# MatriXDeck.net
KiCad netlist of a schematic drawn in Altium Designer
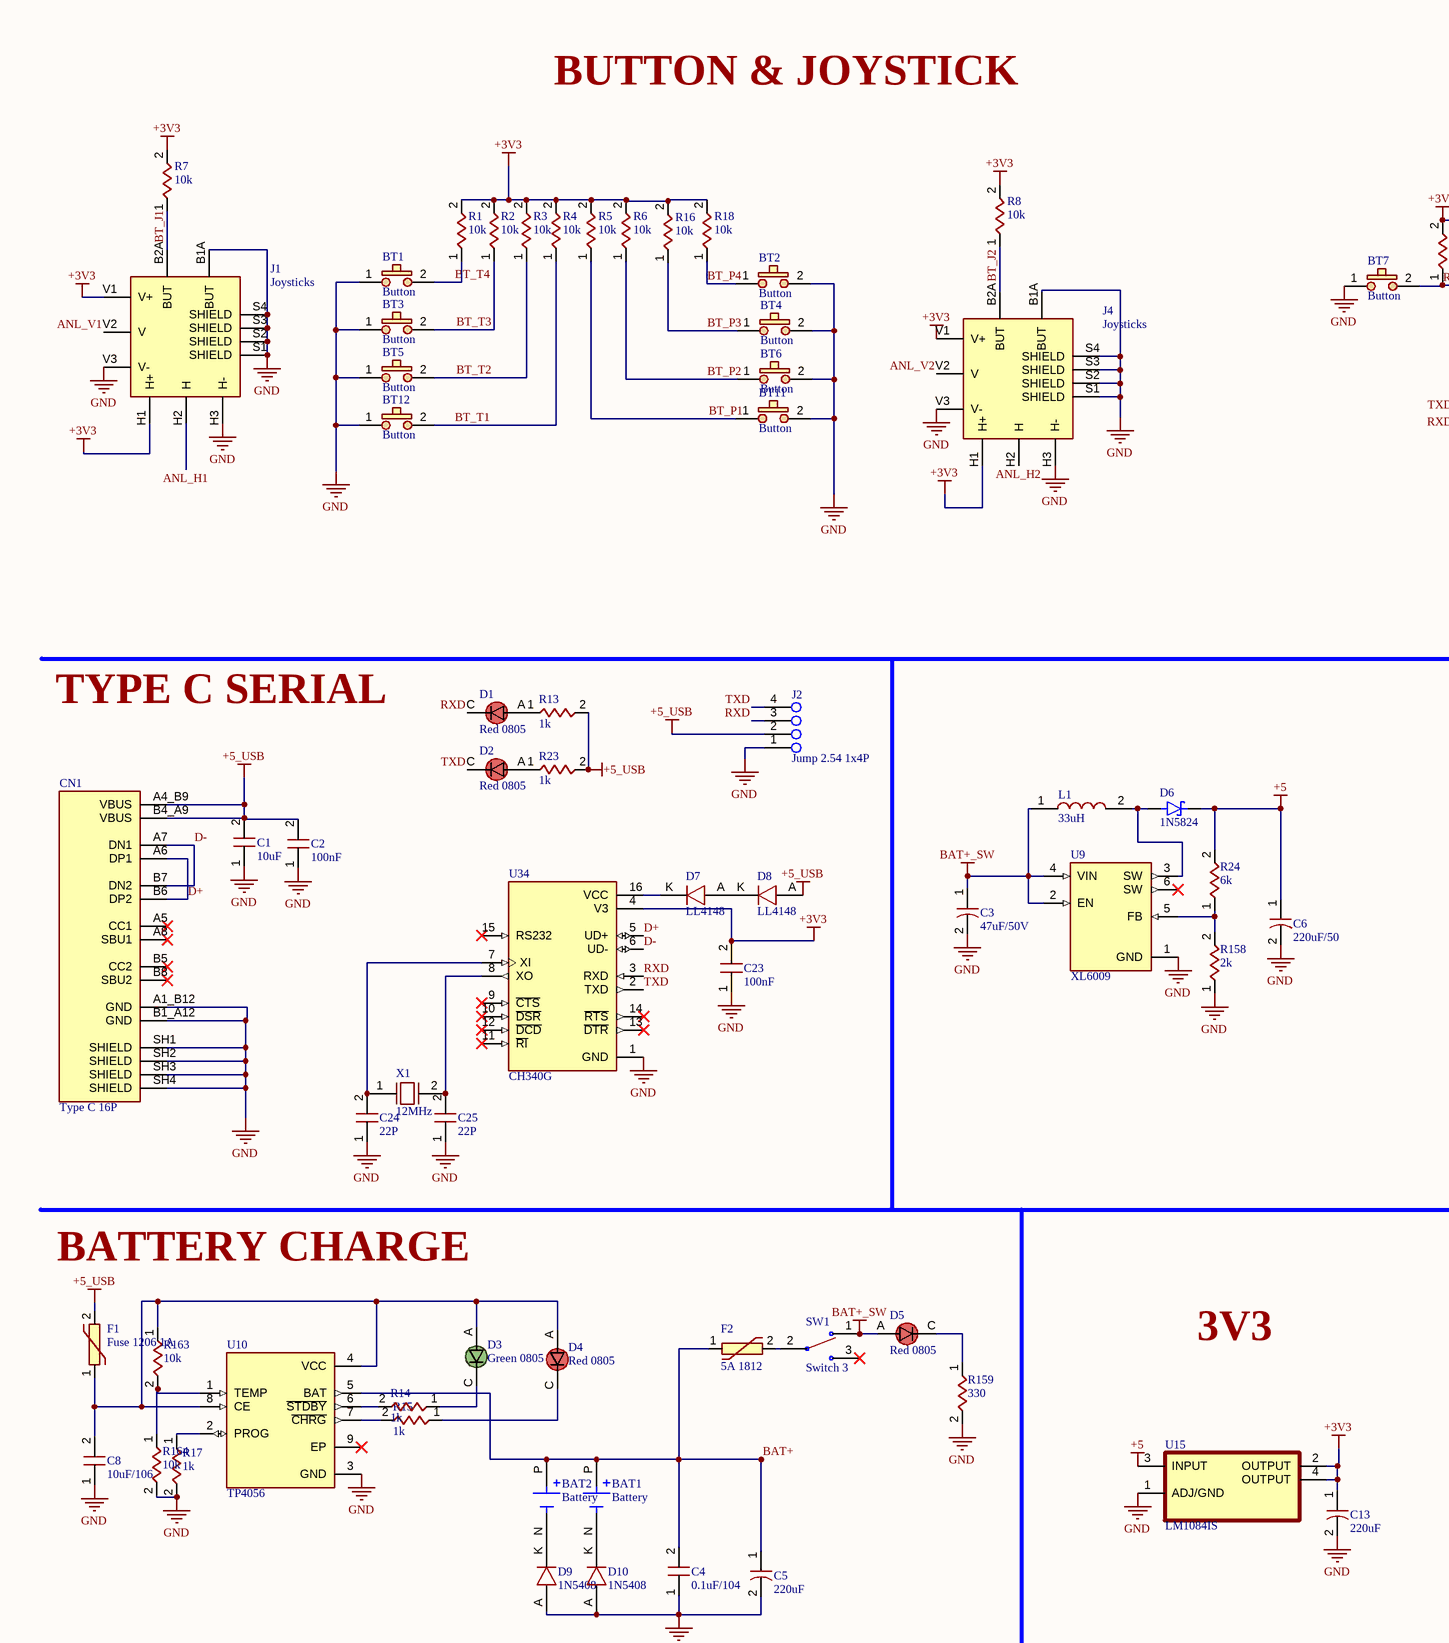
[diagram p0: MatriXDeck.SchDoc, top left]
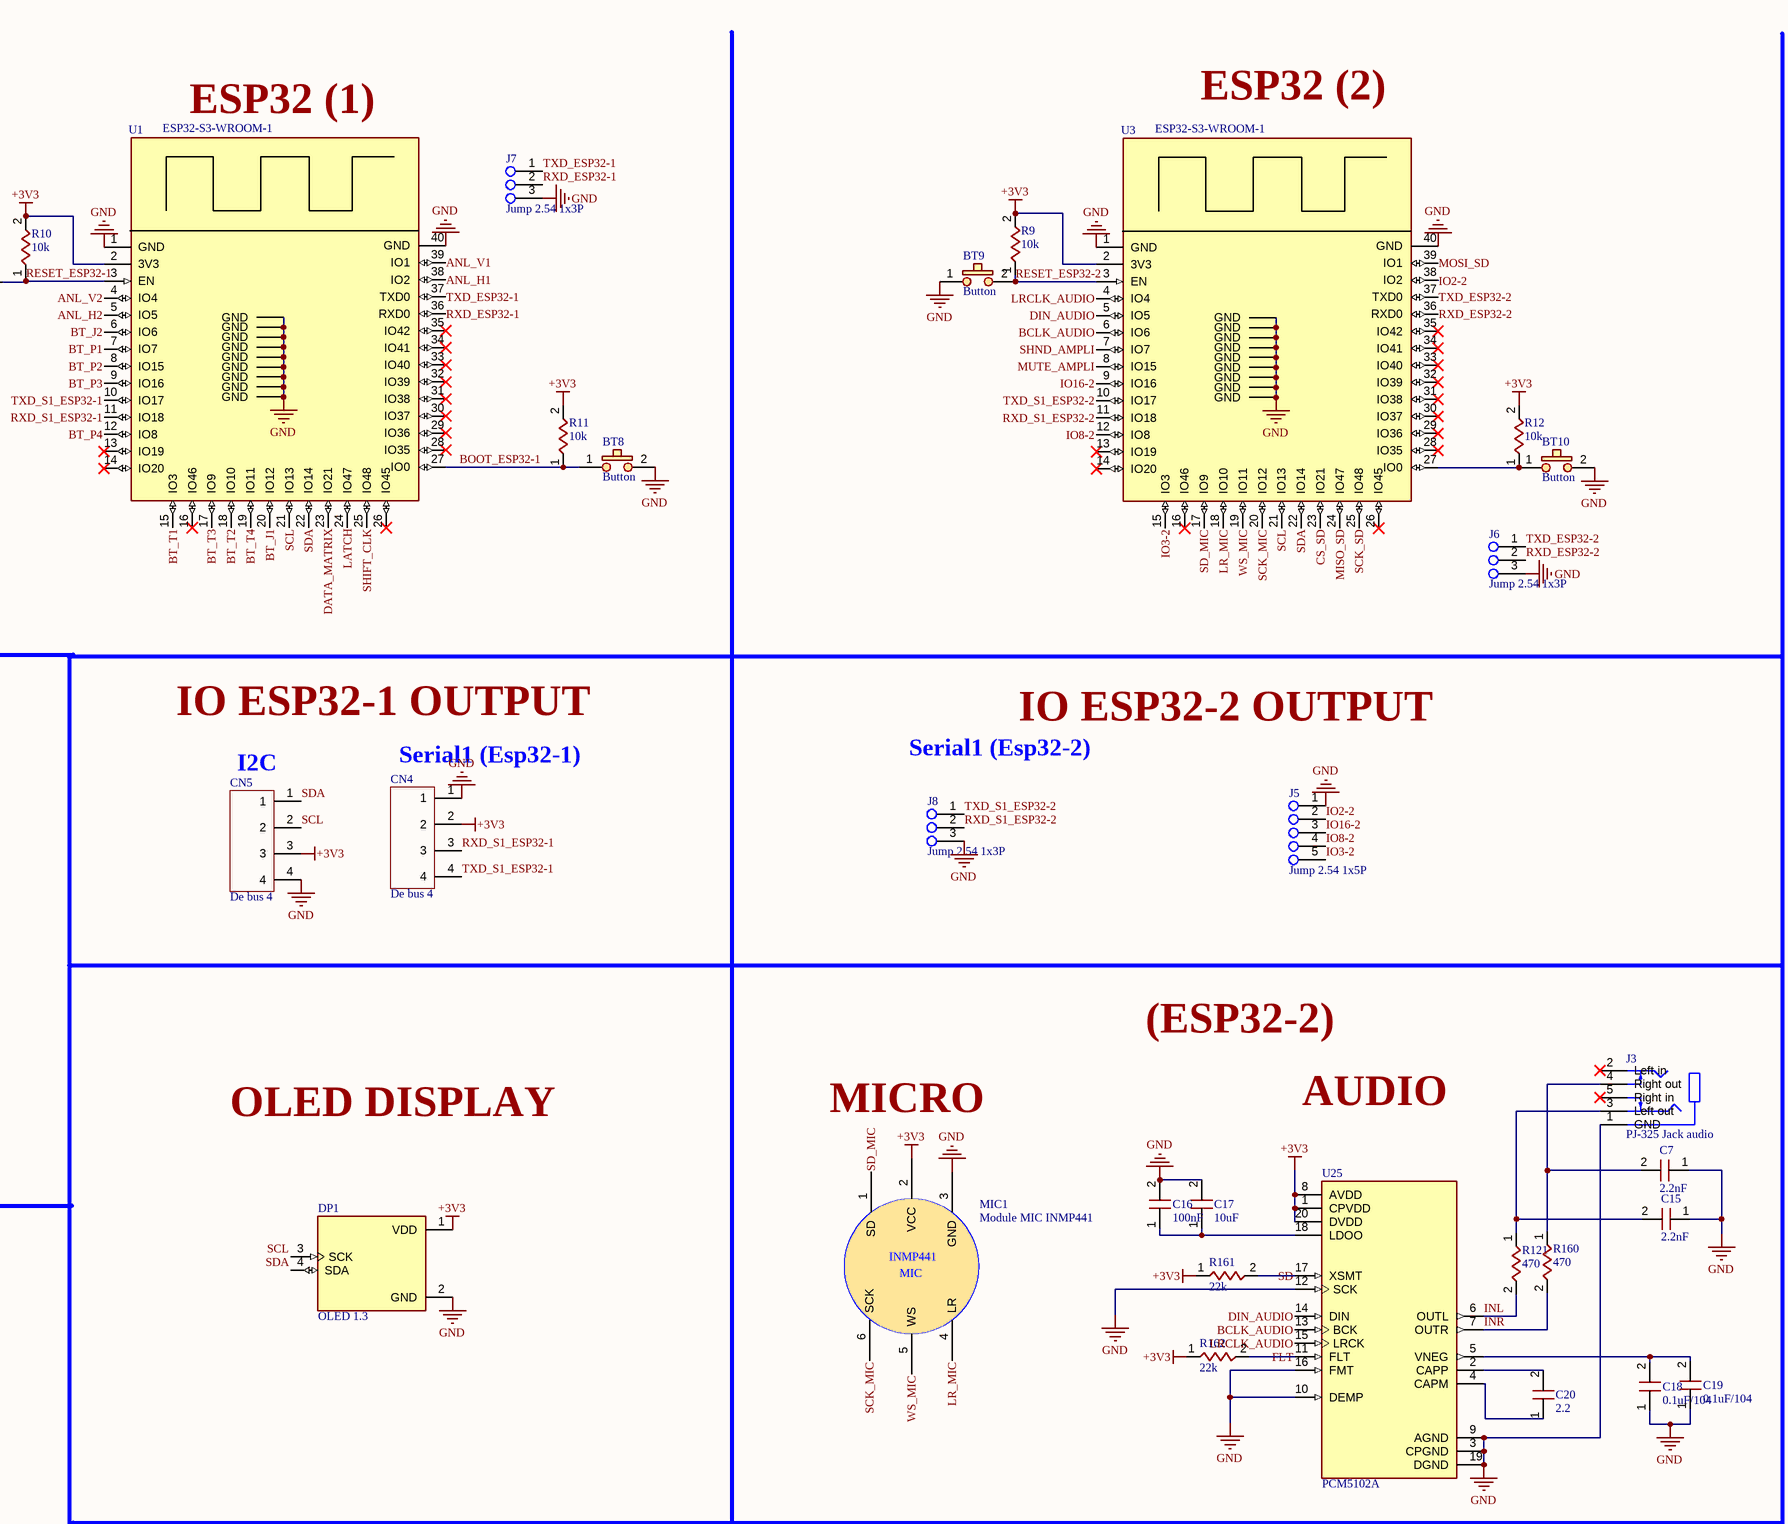
[diagram p1: MatriXDeck.SchDoc, top middle]
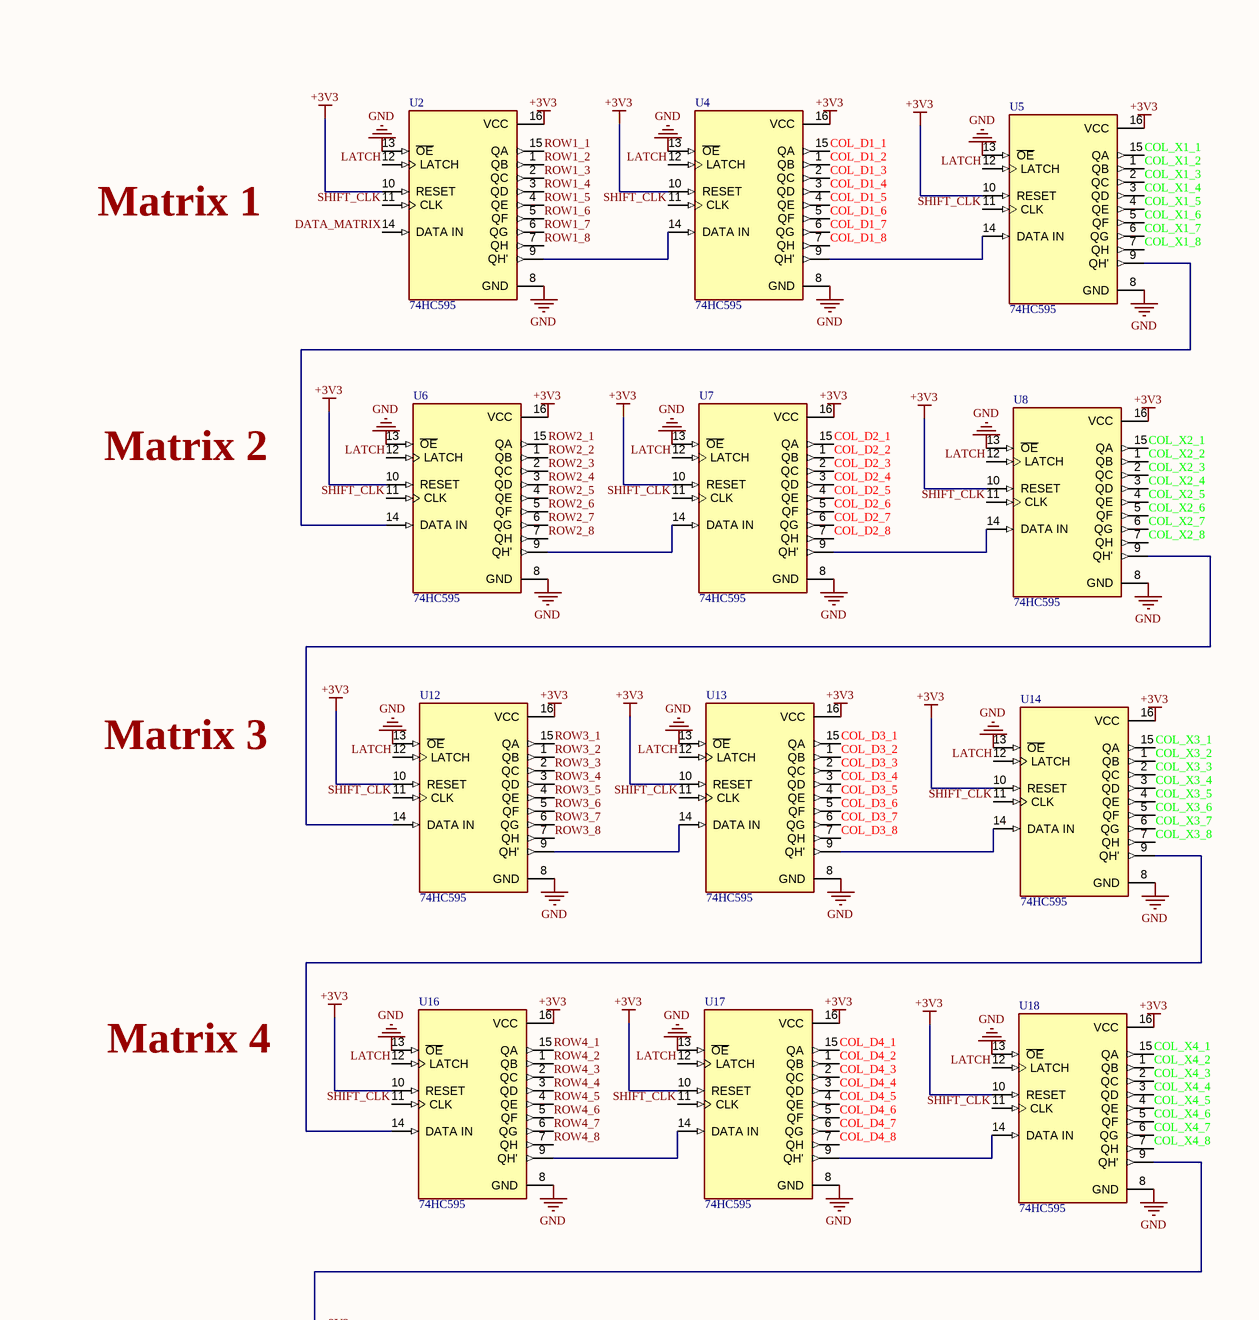
[diagram p2: MatriXDeck.SchDoc, top right]
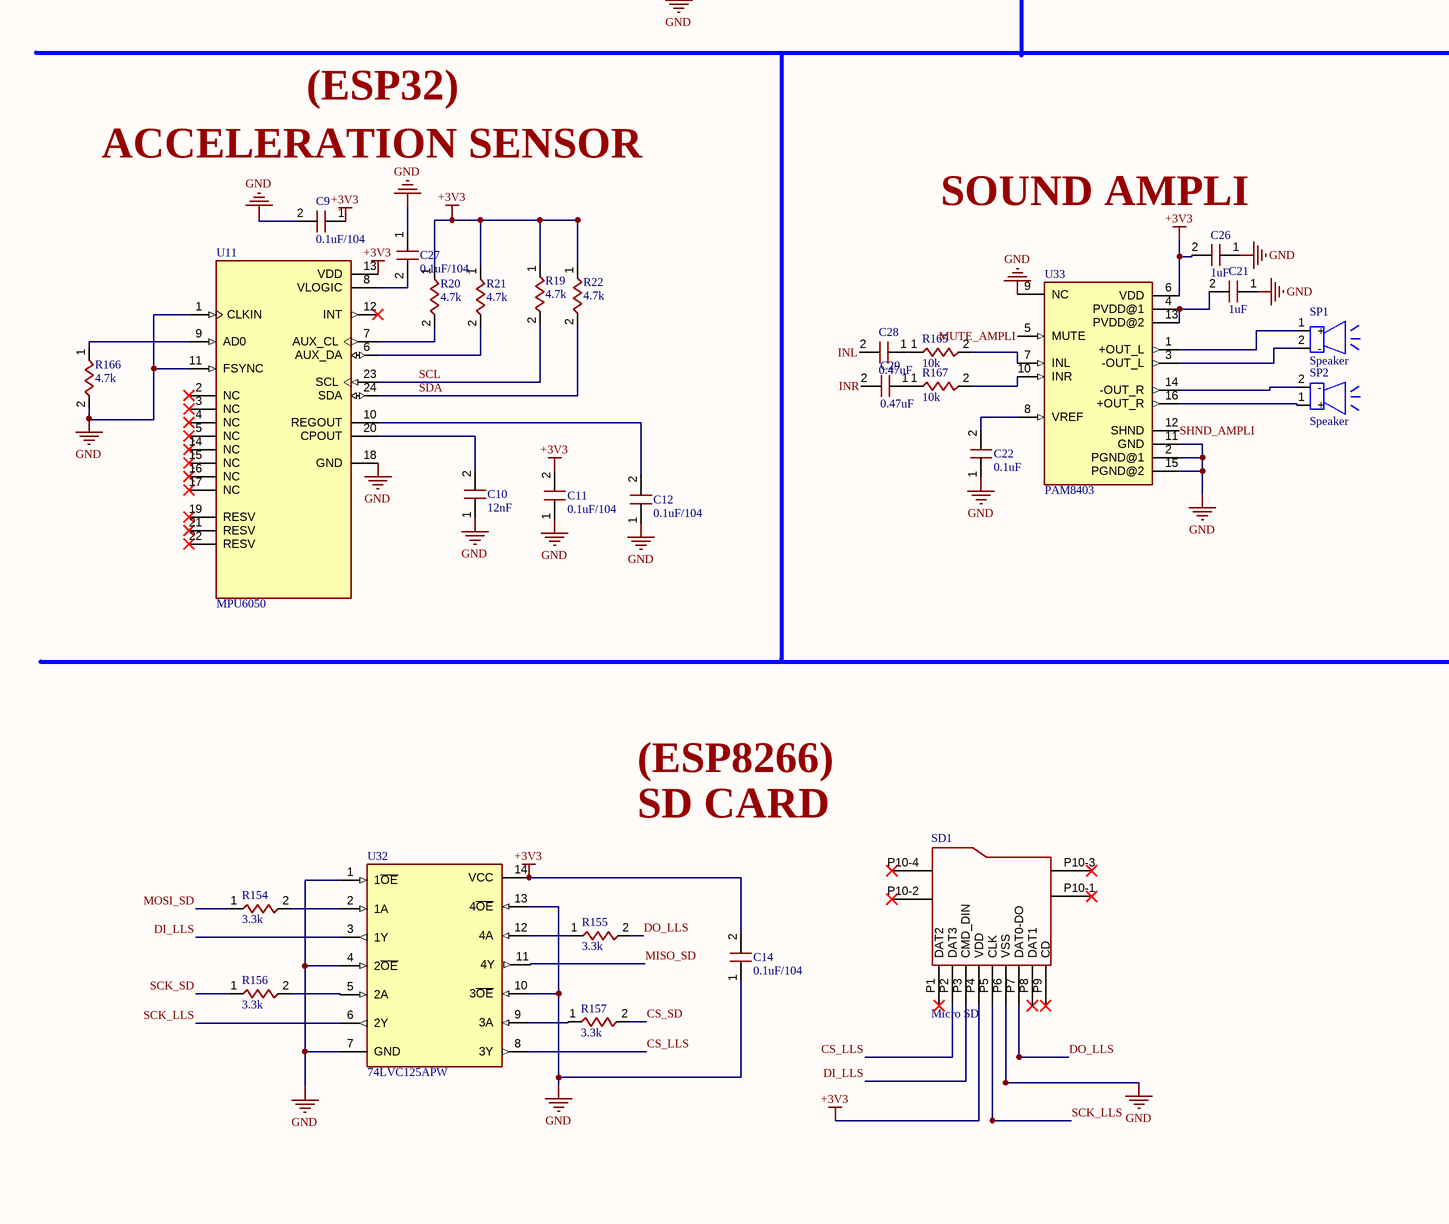
[diagram p3: MatriXDeck.SchDoc, bottom left]
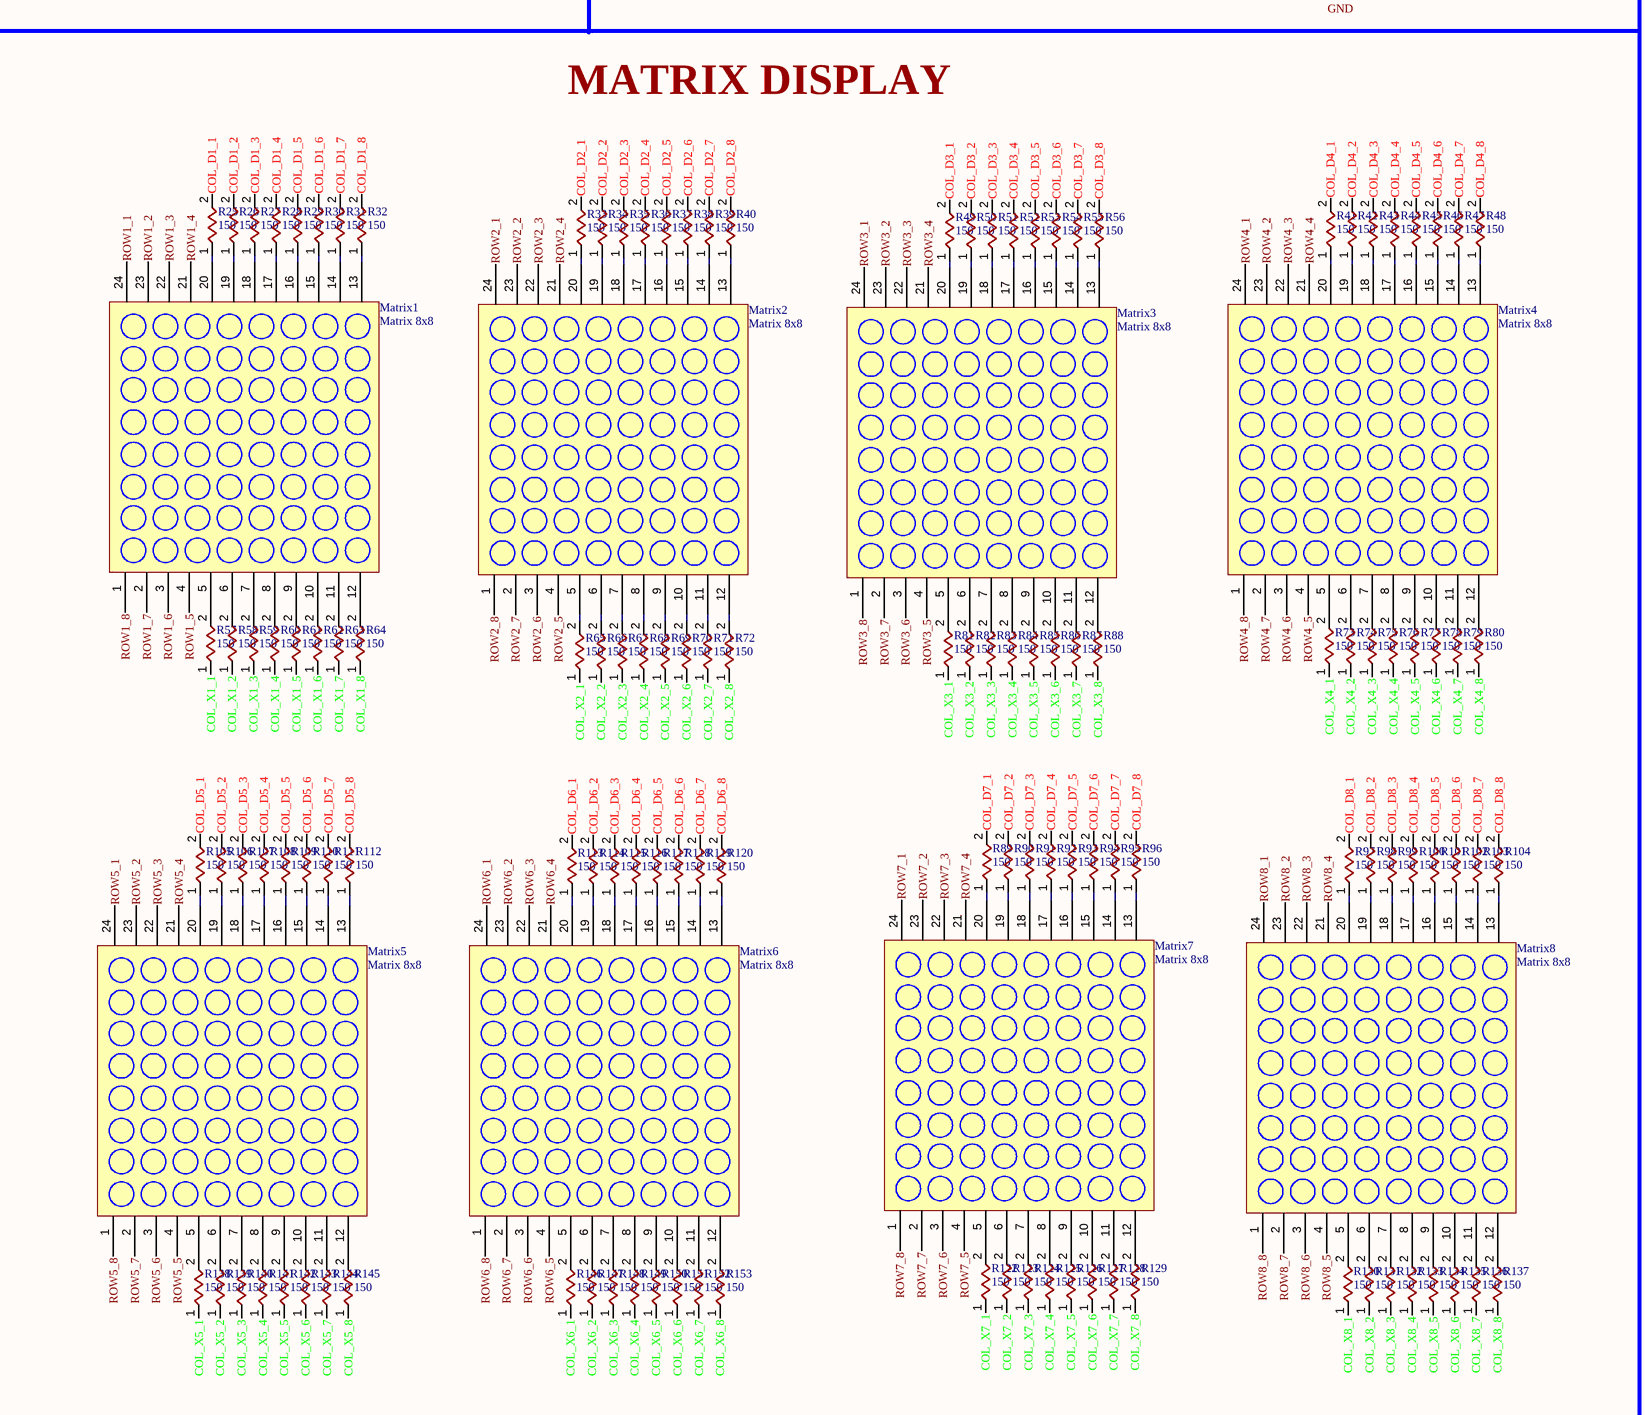
[diagram p4: MatriXDeck.SchDoc, bottom middle]
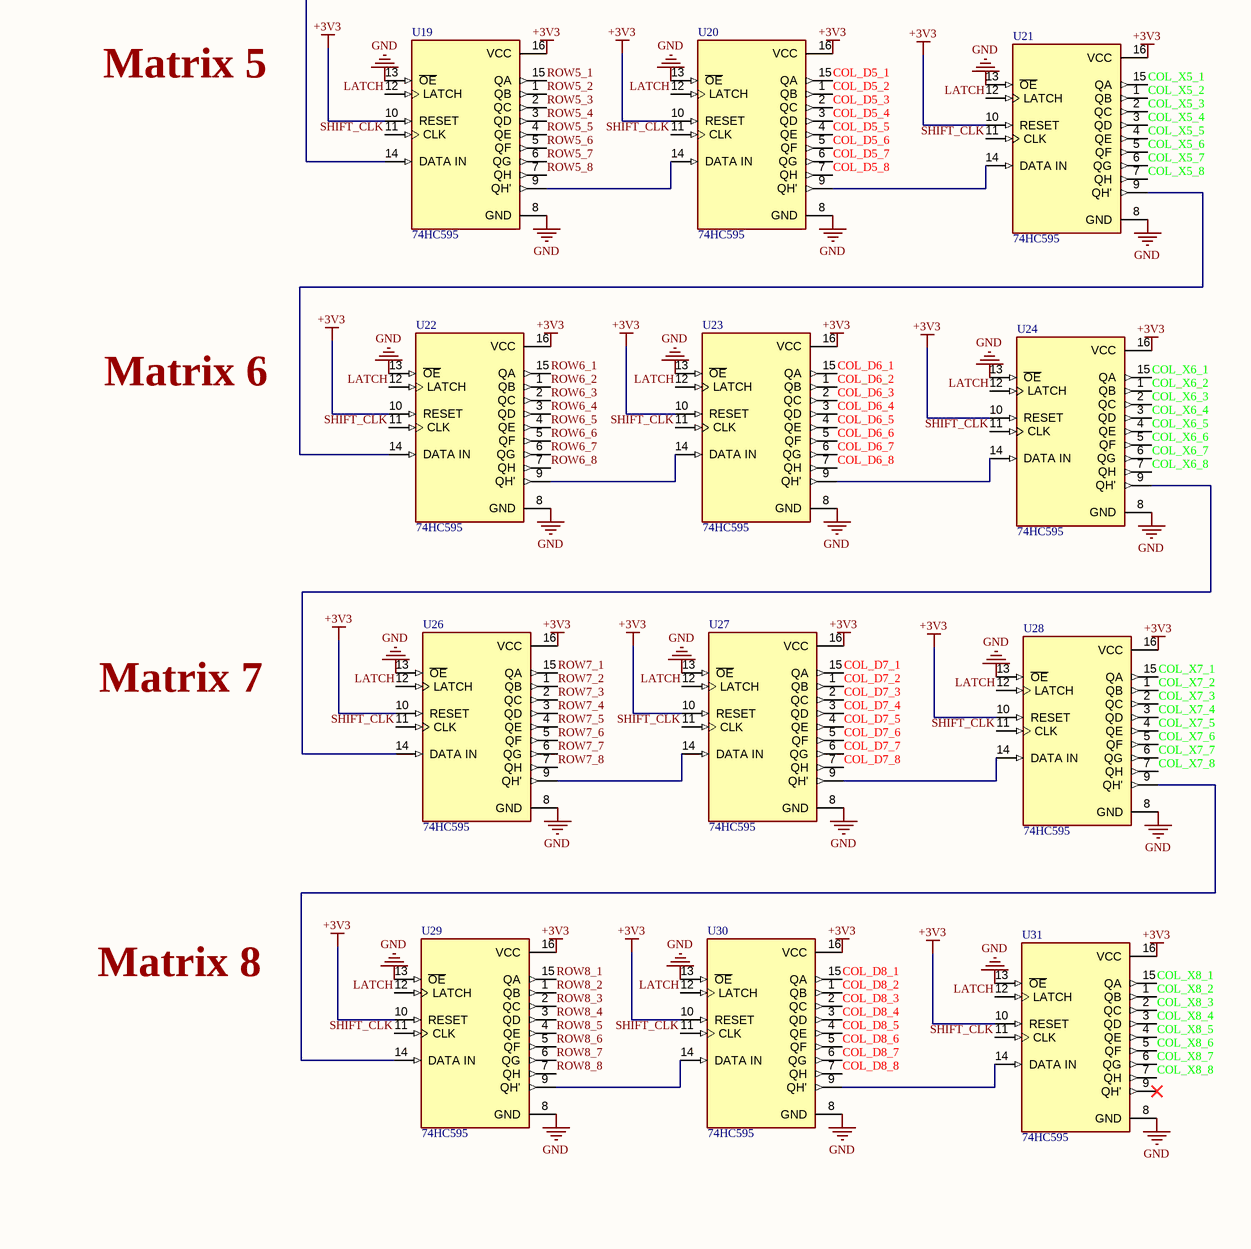
[diagram p5: MatriXDeck.SchDoc, bottom right]

(export (version "E")
  (design (tool "Eeschema 10.0.6"))
  (components
    (comp (ref "BAT1")
      (value "Battery")
      (footprint "16850 SMD")
      (libsource (lib "Libraries R&D by Sang Hoang") (part "Battery"))
    )
    (comp (ref "BAT2")
      (value "Battery")
      (footprint "16850 SMD")
      (libsource (lib "Libraries R&D by Sang Hoang") (part "Battery"))
    )
    (comp (ref "BT1")
      (value "Button")
      (footprint "BT 12x12 SMD")
      (libsource (lib "Libraries R&D by Sang Hoang") (part "Button"))
    )
    (comp (ref "BT2")
      (value "Button")
      (footprint "BT 12x12 SMD")
      (libsource (lib "Libraries R&D by Sang Hoang") (part "Button"))
    )
    (comp (ref "BT3")
      (value "Button")
      (footprint "BT 12x12 SMD")
      (libsource (lib "Libraries R&D by Sang Hoang") (part "Button"))
    )
    (comp (ref "BT4")
      (value "Button")
      (footprint "BT 12x12 SMD")
      (libsource (lib "Libraries R&D by Sang Hoang") (part "Button"))
    )
    (comp (ref "BT5")
      (value "Button")
      (footprint "BT 12x12 SMD")
      (libsource (lib "Libraries R&D by Sang Hoang") (part "Button"))
    )
    (comp (ref "BT6")
      (value "Button")
      (footprint "BT 12x12 SMD")
      (libsource (lib "Libraries R&D by Sang Hoang") (part "Button"))
    )
    (comp (ref "BT7")
      (value "Button")
      (footprint "BT 6x4mm")
      (libsource (lib "Libraries R&D by Sang Hoang") (part "Button"))
    )
    (comp (ref "BT8")
      (value "Button")
      (footprint "BT 6x4mm")
      (libsource (lib "Libraries R&D by Sang Hoang") (part "Button"))
    )
    (comp (ref "BT9")
      (value "Button")
      (footprint "BT 6x4mm")
      (libsource (lib "Libraries R&D by Sang Hoang") (part "Button"))
    )
    (comp (ref "BT10")
      (value "Button")
      (footprint "BT 6x4mm")
      (libsource (lib "Libraries R&D by Sang Hoang") (part "Button"))
    )
    (comp (ref "BT11")
      (value "Button")
      (footprint "BT 12x12 SMD")
      (libsource (lib "Libraries R&D by Sang Hoang") (part "Button"))
    )
    (comp (ref "BT12")
      (value "Button")
      (footprint "BT 12x12 SMD")
      (libsource (lib "Libraries R&D by Sang Hoang") (part "Button"))
    )
    (comp (ref "C1")
      (value "10uF")
      (footprint "CAP 0805")
      (libsource (lib "Libraries R&D by Sang Hoang") (part "Capacitor non-polar"))
    )
    (comp (ref "C2")
      (value "100nF")
      (footprint "CAP 0805")
      (libsource (lib "Libraries R&D by Sang Hoang") (part "Capacitor non-polar"))
    )
    (comp (ref "C3")
      (value "47uF/50V")
      (footprint "Cap Alu 6.3x7.7")
      (libsource (lib "Libraries R&D by Sang Hoang") (part "Capacitor polar"))
    )
    (comp (ref "C4")
      (value "0.1uF/104")
      (footprint "CAP 0805")
      (libsource (lib "Libraries R&D by Sang Hoang") (part "Capacitor non-polar"))
    )
    (comp (ref "C5")
      (value "220uF")
      (footprint "Cap Alu 6.3x7.7")
      (libsource (lib "Libraries R&D by Sang Hoang") (part "Capacitor polar"))
    )
    (comp (ref "C6")
      (value "220uF/50")
      (footprint "Cap Alu 6.3x7.7")
      (libsource (lib "Libraries R&D by Sang Hoang") (part "Capacitor polar"))
    )
    (comp (ref "C7")
      (value "2.2nF")
      (footprint "CAP 0805")
      (libsource (lib "Libraries R&D by Sang Hoang") (part "Capacitor non-polar"))
    )
    (comp (ref "C8")
      (value "10uF/106")
      (footprint "CAP 0805")
      (libsource (lib "Libraries R&D by Sang Hoang") (part "Capacitor non-polar"))
    )
    (comp (ref "C9")
      (value "0.1uF/104")
      (footprint "CAP 0805")
      (libsource (lib "Libraries R&D by Sang Hoang") (part "Capacitor non-polar"))
    )
    (comp (ref "C10")
      (value "12nF")
      (footprint "CAP 0805")
      (libsource (lib "Libraries R&D by Sang Hoang") (part "Capacitor non-polar"))
    )
    (comp (ref "C11")
      (value "0.1uF/104")
      (footprint "CAP 0805")
      (libsource (lib "Libraries R&D by Sang Hoang") (part "Capacitor non-polar"))
    )
    (comp (ref "C12")
      (value "0.1uF/104")
      (footprint "CAP 0805")
      (libsource (lib "Libraries R&D by Sang Hoang") (part "Capacitor non-polar"))
    )
    (comp (ref "C13")
      (value "220uF")
      (footprint "Cap Alu 6.3x7.7")
      (libsource (lib "Libraries R&D by Sang Hoang") (part "Capacitor polar"))
    )
    (comp (ref "C14")
      (value "0.1uF/104")
      (footprint "CAP 0805")
      (libsource (lib "Libraries R&D by Sang Hoang") (part "Capacitor non-polar"))
    )
    (comp (ref "C15")
      (value "2.2nF")
      (footprint "CAP 0805")
      (libsource (lib "Libraries R&D by Sang Hoang") (part "Capacitor non-polar"))
    )
    (comp (ref "C16")
      (value "100nF")
      (footprint "CAP 0805")
      (libsource (lib "Libraries R&D by Sang Hoang") (part "Capacitor non-polar"))
    )
    (comp (ref "C17")
      (value "10uF")
      (footprint "CAP 0805")
      (libsource (lib "Libraries R&D by Sang Hoang") (part "Capacitor non-polar"))
    )
    (comp (ref "C18")
      (value "0.1uF/104")
      (footprint "CAP 0805")
      (libsource (lib "Libraries R&D by Sang Hoang") (part "Capacitor non-polar"))
    )
    (comp (ref "C19")
      (value "0.1uF/104")
      (footprint "CAP 0805")
      (libsource (lib "Libraries R&D by Sang Hoang") (part "Capacitor non-polar"))
    )
    (comp (ref "C20")
      (value "2.2")
      (footprint "CAP 0805")
      (libsource (lib "Libraries R&D by Sang Hoang") (part "Capacitor non-polar"))
    )
    (comp (ref "C21")
      (value "1uF")
      (footprint "CAP 0805")
      (libsource (lib "Libraries R&D by Sang Hoang") (part "Capacitor non-polar"))
    )
    (comp (ref "C22")
      (value "0.1uF")
      (footprint "CAP 0805")
      (libsource (lib "Libraries R&D by Sang Hoang") (part "Capacitor non-polar"))
    )
    (comp (ref "C23")
      (value "100nF")
      (footprint "CAP 0805")
      (libsource (lib "Libraries R&D by Sang Hoang") (part "Capacitor non-polar"))
    )
    (comp (ref "C24")
      (value "22P")
      (footprint "CAP 0805")
      (libsource (lib "Libraries R&D by Sang Hoang") (part "Capacitor non-polar"))
    )
    (comp (ref "C25")
      (value "22P")
      (footprint "CAP 0805")
      (libsource (lib "Libraries R&D by Sang Hoang") (part "Capacitor non-polar"))
    )
    (comp (ref "C26")
      (value "1uF")
      (footprint "CAP 0805")
      (libsource (lib "Libraries R&D by Sang Hoang") (part "Capacitor non-polar"))
    )
    (comp (ref "C27")
      (value "0.1uF/104")
      (footprint "CAP 0805")
      (libsource (lib "Libraries R&D by Sang Hoang") (part "Capacitor non-polar"))
    )
    (comp (ref "C28")
      (value "0.47uF")
      (footprint "CAP 0805")
      (libsource (lib "Libraries R&D by Sang Hoang") (part "Capacitor non-polar"))
    )
    (comp (ref "C29")
      (value "0.47uF")
      (footprint "CAP 0805")
      (libsource (lib "Libraries R&D by Sang Hoang") (part "Capacitor non-polar"))
    )
    (comp (ref "CN1")
      (value "Type C 16P")
      (footprint "Type C 16P")
      (libsource (lib "Libraries R&D by Sang Hoang") (part "Type C 16P"))
    )
    (comp (ref "CN4")
      (value "De bus 4")
      (footprint "De bus 4")
      (libsource (lib "Libraries R&D by Sang Hoang") (part "De bus 4"))
    )
    (comp (ref "CN5") (value "De bus 4") (footprint "De bus 4") (libsource (lib "") (part "De bus 4_1")))
    (comp (ref "D1")
      (value "Red 0805")
      (footprint "LED RED 0805")
      (libsource (lib "Libraries R&D by Sang Hoang") (part "Led Red"))
    )
    (comp (ref "D2")
      (value "Red 0805")
      (footprint "LED RED 0805")
      (libsource (lib "Libraries R&D by Sang Hoang") (part "Led Red"))
    )
    (comp (ref "D3")
      (value "Green 0805")
      (footprint "LED GREEN 0805")
      (libsource (lib "Libraries R&D by Sang Hoang") (part "Led Green"))
    )
    (comp (ref "D4")
      (value "Red 0805")
      (footprint "LED RED 0805")
      (libsource (lib "Libraries R&D by Sang Hoang") (part "Led Red"))
    )
    (comp (ref "D5")
      (value "Red 0805")
      (footprint "LED RED 0805")
      (libsource (lib "Libraries R&D by Sang Hoang") (part "Led Red"))
    )
    (comp (ref "D6")
      (value "1N5824")
      (footprint "DO-214AC (SMA)")
      (libsource (lib "Libraries R&D by Sang Hoang") (part "Diode Schottky"))
    )
    (comp (ref "D7")
      (value "LL4148")
      (footprint "DIO_LL4148")
      (libsource (lib "Libraries R&D by Sang Hoang") (part "Diode"))
    )
    (comp (ref "D8")
      (value "LL4148")
      (footprint "DIO_LL4148")
      (libsource (lib "Libraries R&D by Sang Hoang") (part "Diode"))
    )
    (comp (ref "D9")
      (value "1N5408")
      (footprint "S3M")
      (libsource (lib "Libraries R&D by Sang Hoang") (part "Diode"))
    )
    (comp (ref "D10")
      (value "1N5408")
      (footprint "S3M")
      (libsource (lib "Libraries R&D by Sang Hoang") (part "Diode"))
    )
    (comp (ref "DP1")
      (value "OLED 1.3")
      (footprint "Display OLED 1.3")
      (libsource (lib "Libraries R&D by Sang Hoang") (part "OLED 1.3"))
    )
    (comp (ref "F1")
      (value "Fuse 1206 1A")
      (footprint "Fuse 1206")
      (libsource (lib "Libraries R&D by Sang Hoang") (part "Fuse"))
    )
    (comp (ref "F2") (value "5A 1812") (footprint "FUSE1812") (libsource (lib "") (part "Fuse_1")))
    (comp (ref "J1")
      (value "Joysticks")
      (footprint "Joysticks")
      (libsource (lib "Libraries R&D by Sang Hoang") (part "Joysticks"))
    )
    (comp (ref "J2")
      (value "Jump 2.54 1x4P")
      (footprint "Jump 2.54 1x4P duc thang")
      (libsource (lib "Libraries R&D by Sang Hoang") (part "Jump 2.54 1x4P"))
    )
    (comp (ref "J3")
      (value "PJ-325 Jack audio")
      (footprint "Jack audio PJ-325")
      (libsource (lib "Libraries R&D by Sang Hoang") (part "PJ-325 Jack audio"))
    )
    (comp (ref "J4")
      (value "Joysticks")
      (footprint "Joysticks")
      (libsource (lib "Libraries R&D by Sang Hoang") (part "Joysticks"))
    )
    (comp (ref "J5")
      (value "Jump 2.54 1x5P")
      (footprint "Jump 2.54 1x5P duc thang")
      (libsource (lib "Libraries R&D by Sang Hoang") (part "Jump 2.54 1x5P"))
    )
    (comp (ref "J6")
      (value "Jump 2.54 1x3P")
      (footprint "Jump 2.54 1x3P duc thang")
      (libsource (lib "Libraries R&D by Sang Hoang") (part "Jump 2.54 1x3P"))
    )
    (comp (ref "J7")
      (value "Jump 2.54 1x3P")
      (footprint "Jump 2.54 1x3P duc thang")
      (libsource (lib "Libraries R&D by Sang Hoang") (part "Jump 2.54 1x3P"))
    )
    (comp (ref "J8")
      (value "Jump 2.54 1x3P")
      (footprint "Jump 2.54 1x3P duc thang")
      (libsource (lib "Libraries R&D by Sang Hoang") (part "Jump 2.54 1x3P"))
    )
    (comp (ref "L1")
      (value "33uH")
      (footprint "Inductor 12x12 smd")
      (libsource (lib "Libraries R&D by Sang Hoang") (part "Inductor"))
    )
    (comp (ref "Matrix1")
      (value "Matrix 8x8")
      (footprint "Matrix 8x8 2 color")
      (libsource (lib "Libraries R&D by Sang Hoang") (part "Matrix 8x8"))
    )
    (comp (ref "Matrix2")
      (value "Matrix 8x8")
      (footprint "Matrix 8x8 2 color")
      (libsource (lib "") (part "Matrix 8x8_3"))
    )
    (comp (ref "Matrix3")
      (value "Matrix 8x8")
      (footprint "Matrix 8x8 2 color")
      (libsource (lib "") (part "Matrix 8x8_3"))
    )
    (comp (ref "Matrix4")
      (value "Matrix 8x8")
      (footprint "Matrix 8x8 2 color")
      (libsource (lib "") (part "Matrix 8x8_2"))
    )
    (comp (ref "Matrix5")
      (value "Matrix 8x8")
      (footprint "Matrix 8x8 2 color")
      (libsource (lib "") (part "Matrix 8x8_1"))
    )
    (comp (ref "Matrix6")
      (value "Matrix 8x8")
      (footprint "Matrix 8x8 2 color")
      (libsource (lib "") (part "Matrix 8x8_2"))
    )
    (comp (ref "Matrix7")
      (value "Matrix 8x8")
      (footprint "Matrix 8x8 2 color")
      (libsource (lib "") (part "Matrix 8x8_5"))
    )
    (comp (ref "Matrix8")
      (value "Matrix 8x8")
      (footprint "Matrix 8x8 2 color")
      (libsource (lib "") (part "Matrix 8x8_4"))
    )
    (comp (ref "MIC1")
      (value "Module MIC INMP441")
      (footprint "Module Mic INMP441")
      (libsource (lib "Libraries R&D by Sang Hoang") (part "Module MIC INMP441"))
    )
    (comp (ref "R1")
      (value "10k")
      (footprint "RES 0805")
      (libsource (lib "Libraries R&D by Sang Hoang") (part "Resistor"))
    )
    (comp (ref "R2")
      (value "10k")
      (footprint "RES 0805")
      (libsource (lib "Libraries R&D by Sang Hoang") (part "Resistor"))
    )
    (comp (ref "R3")
      (value "10k")
      (footprint "RES 0805")
      (libsource (lib "Libraries R&D by Sang Hoang") (part "Resistor"))
    )
    (comp (ref "R4")
      (value "10k")
      (footprint "RES 0805")
      (libsource (lib "Libraries R&D by Sang Hoang") (part "Resistor"))
    )
    (comp (ref "R5")
      (value "10k")
      (footprint "RES 0805")
      (libsource (lib "Libraries R&D by Sang Hoang") (part "Resistor"))
    )
    (comp (ref "R6")
      (value "10k")
      (footprint "RES 0805")
      (libsource (lib "Libraries R&D by Sang Hoang") (part "Resistor"))
    )
    (comp (ref "R7")
      (value "10k")
      (footprint "RES 0805")
      (libsource (lib "Libraries R&D by Sang Hoang") (part "Resistor"))
    )
    (comp (ref "R8")
      (value "10k")
      (footprint "RES 0805")
      (libsource (lib "Libraries R&D by Sang Hoang") (part "Resistor"))
    )
    (comp (ref "R9")
      (value "10k")
      (footprint "RES 0805")
      (libsource (lib "Libraries R&D by Sang Hoang") (part "Resistor"))
    )
    (comp (ref "R10")
      (value "10k")
      (footprint "RES 0805")
      (libsource (lib "Libraries R&D by Sang Hoang") (part "Resistor"))
    )
    (comp (ref "R11")
      (value "10k")
      (footprint "RES 0805")
      (libsource (lib "Libraries R&D by Sang Hoang") (part "Resistor"))
    )
    (comp (ref "R12")
      (value "10k")
      (footprint "RES 0805")
      (libsource (lib "Libraries R&D by Sang Hoang") (part "Resistor"))
    )
    (comp (ref "R13")
      (value "1k")
      (footprint "RES 0805")
      (libsource (lib "Libraries R&D by Sang Hoang") (part "Resistor"))
    )
    (comp (ref "R14")
      (value "1k")
      (footprint "RES 0805")
      (libsource (lib "Libraries R&D by Sang Hoang") (part "Resistor"))
    )
    (comp (ref "R15")
      (value "1k")
      (footprint "RES 0805")
      (libsource (lib "Libraries R&D by Sang Hoang") (part "Resistor"))
    )
    (comp (ref "R16")
      (value "10k")
      (footprint "RES 0805")
      (libsource (lib "Libraries R&D by Sang Hoang") (part "Resistor"))
    )
    (comp (ref "R17")
      (value "1k")
      (footprint "RES 0805")
      (libsource (lib "Libraries R&D by Sang Hoang") (part "Resistor"))
    )
    (comp (ref "R18")
      (value "10k")
      (footprint "RES 0805")
      (libsource (lib "Libraries R&D by Sang Hoang") (part "Resistor"))
    )
    (comp (ref "R19")
      (value "4.7k")
      (footprint "RES 0805")
      (libsource (lib "Libraries R&D by Sang Hoang") (part "Resistor"))
    )
    (comp (ref "R20")
      (value "4.7k")
      (footprint "RES 0805")
      (libsource (lib "Libraries R&D by Sang Hoang") (part "Resistor"))
    )
    (comp (ref "R21")
      (value "4.7k")
      (footprint "RES 0805")
      (libsource (lib "Libraries R&D by Sang Hoang") (part "Resistor"))
    )
    (comp (ref "R22")
      (value "4.7k")
      (footprint "RES 0805")
      (libsource (lib "Libraries R&D by Sang Hoang") (part "Resistor"))
    )
    (comp (ref "R23")
      (value "1k")
      (footprint "RES 0805")
      (libsource (lib "Libraries R&D by Sang Hoang") (part "Resistor"))
    )
    (comp (ref "R24")
      (value "6k")
      (footprint "RES 0805")
      (libsource (lib "Libraries R&D by Sang Hoang") (part "Resistor"))
    )
    (comp (ref "R25")
      (value "150")
      (footprint "RES 0805")
      (libsource (lib "Libraries R&D by Sang Hoang") (part "Resistor"))
    )
    (comp (ref "R26")
      (value "150")
      (footprint "RES 0805")
      (libsource (lib "Libraries R&D by Sang Hoang") (part "Resistor"))
    )
    (comp (ref "R27")
      (value "150")
      (footprint "RES 0805")
      (libsource (lib "Libraries R&D by Sang Hoang") (part "Resistor"))
    )
    (comp (ref "R28")
      (value "150")
      (footprint "RES 0805")
      (libsource (lib "Libraries R&D by Sang Hoang") (part "Resistor"))
    )
    (comp (ref "R29")
      (value "150")
      (footprint "RES 0805")
      (libsource (lib "Libraries R&D by Sang Hoang") (part "Resistor"))
    )
    (comp (ref "R30")
      (value "150")
      (footprint "RES 0805")
      (libsource (lib "Libraries R&D by Sang Hoang") (part "Resistor"))
    )
    (comp (ref "R31")
      (value "150")
      (footprint "RES 0805")
      (libsource (lib "Libraries R&D by Sang Hoang") (part "Resistor"))
    )
    (comp (ref "R32")
      (value "150")
      (footprint "RES 0805")
      (libsource (lib "Libraries R&D by Sang Hoang") (part "Resistor"))
    )
    (comp (ref "R33")
      (value "150")
      (footprint "RES 0805")
      (libsource (lib "Libraries R&D by Sang Hoang") (part "Resistor"))
    )
    (comp (ref "R34")
      (value "150")
      (footprint "RES 0805")
      (libsource (lib "Libraries R&D by Sang Hoang") (part "Resistor"))
    )
    (comp (ref "R35")
      (value "150")
      (footprint "RES 0805")
      (libsource (lib "Libraries R&D by Sang Hoang") (part "Resistor"))
    )
    (comp (ref "R36")
      (value "150")
      (footprint "RES 0805")
      (libsource (lib "Libraries R&D by Sang Hoang") (part "Resistor"))
    )
    (comp (ref "R37")
      (value "150")
      (footprint "RES 0805")
      (libsource (lib "Libraries R&D by Sang Hoang") (part "Resistor"))
    )
    (comp (ref "R38")
      (value "150")
      (footprint "RES 0805")
      (libsource (lib "Libraries R&D by Sang Hoang") (part "Resistor"))
    )
    (comp (ref "R39")
      (value "150")
      (footprint "RES 0805")
      (libsource (lib "Libraries R&D by Sang Hoang") (part "Resistor"))
    )
    (comp (ref "R40")
      (value "150")
      (footprint "RES 0805")
      (libsource (lib "Libraries R&D by Sang Hoang") (part "Resistor"))
    )
    (comp (ref "R41")
      (value "150")
      (footprint "RES 0805")
      (libsource (lib "Libraries R&D by Sang Hoang") (part "Resistor"))
    )
    (comp (ref "R42")
      (value "150")
      (footprint "RES 0805")
      (libsource (lib "Libraries R&D by Sang Hoang") (part "Resistor"))
    )
    (comp (ref "R43")
      (value "150")
      (footprint "RES 0805")
      (libsource (lib "Libraries R&D by Sang Hoang") (part "Resistor"))
    )
    (comp (ref "R44")
      (value "150")
      (footprint "RES 0805")
      (libsource (lib "Libraries R&D by Sang Hoang") (part "Resistor"))
    )
    (comp (ref "R45")
      (value "150")
      (footprint "RES 0805")
      (libsource (lib "Libraries R&D by Sang Hoang") (part "Resistor"))
    )
    (comp (ref "R46")
      (value "150")
      (footprint "RES 0805")
      (libsource (lib "Libraries R&D by Sang Hoang") (part "Resistor"))
    )
    (comp (ref "R47")
      (value "150")
      (footprint "RES 0805")
      (libsource (lib "Libraries R&D by Sang Hoang") (part "Resistor"))
    )
    (comp (ref "R48")
      (value "150")
      (footprint "RES 0805")
      (libsource (lib "Libraries R&D by Sang Hoang") (part "Resistor"))
    )
    (comp (ref "R49")
      (value "150")
      (footprint "RES 0805")
      (libsource (lib "Libraries R&D by Sang Hoang") (part "Resistor"))
    )
    (comp (ref "R50")
      (value "150")
      (footprint "RES 0805")
      (libsource (lib "Libraries R&D by Sang Hoang") (part "Resistor"))
    )
    (comp (ref "R51")
      (value "150")
      (footprint "RES 0805")
      (libsource (lib "Libraries R&D by Sang Hoang") (part "Resistor"))
    )
    (comp (ref "R52")
      (value "150")
      (footprint "RES 0805")
      (libsource (lib "Libraries R&D by Sang Hoang") (part "Resistor"))
    )
    (comp (ref "R53")
      (value "150")
      (footprint "RES 0805")
      (libsource (lib "Libraries R&D by Sang Hoang") (part "Resistor"))
    )
    (comp (ref "R54")
      (value "150")
      (footprint "RES 0805")
      (libsource (lib "Libraries R&D by Sang Hoang") (part "Resistor"))
    )
    (comp (ref "R55")
      (value "150")
      (footprint "RES 0805")
      (libsource (lib "Libraries R&D by Sang Hoang") (part "Resistor"))
    )
    (comp (ref "R56")
      (value "150")
      (footprint "RES 0805")
      (libsource (lib "Libraries R&D by Sang Hoang") (part "Resistor"))
    )
    (comp (ref "R57")
      (value "150")
      (footprint "RES 0805")
      (libsource (lib "Libraries R&D by Sang Hoang") (part "Resistor"))
    )
    (comp (ref "R58")
      (value "150")
      (footprint "RES 0805")
      (libsource (lib "Libraries R&D by Sang Hoang") (part "Resistor"))
    )
    (comp (ref "R59")
      (value "150")
      (footprint "RES 0805")
      (libsource (lib "Libraries R&D by Sang Hoang") (part "Resistor"))
    )
    (comp (ref "R60")
      (value "150")
      (footprint "RES 0805")
      (libsource (lib "Libraries R&D by Sang Hoang") (part "Resistor"))
    )
    (comp (ref "R61")
      (value "150")
      (footprint "RES 0805")
      (libsource (lib "Libraries R&D by Sang Hoang") (part "Resistor"))
    )
    (comp (ref "R62")
      (value "150")
      (footprint "RES 0805")
      (libsource (lib "Libraries R&D by Sang Hoang") (part "Resistor"))
    )
    (comp (ref "R63")
      (value "150")
      (footprint "RES 0805")
      (libsource (lib "Libraries R&D by Sang Hoang") (part "Resistor"))
    )
    (comp (ref "R64")
      (value "150")
      (footprint "RES 0805")
      (libsource (lib "Libraries R&D by Sang Hoang") (part "Resistor"))
    )
    (comp (ref "R65")
      (value "150")
      (footprint "RES 0805")
      (libsource (lib "Libraries R&D by Sang Hoang") (part "Resistor"))
    )
    (comp (ref "R66")
      (value "150")
      (footprint "RES 0805")
      (libsource (lib "Libraries R&D by Sang Hoang") (part "Resistor"))
    )
    (comp (ref "R67")
      (value "150")
      (footprint "RES 0805")
      (libsource (lib "Libraries R&D by Sang Hoang") (part "Resistor"))
    )
    (comp (ref "R68")
      (value "150")
      (footprint "RES 0805")
      (libsource (lib "Libraries R&D by Sang Hoang") (part "Resistor"))
    )
    (comp (ref "R69")
      (value "150")
      (footprint "RES 0805")
      (libsource (lib "Libraries R&D by Sang Hoang") (part "Resistor"))
    )
    (comp (ref "R70")
      (value "150")
      (footprint "RES 0805")
      (libsource (lib "Libraries R&D by Sang Hoang") (part "Resistor"))
    )
    (comp (ref "R71")
      (value "150")
      (footprint "RES 0805")
      (libsource (lib "Libraries R&D by Sang Hoang") (part "Resistor"))
    )
    (comp (ref "R72")
      (value "150")
      (footprint "RES 0805")
      (libsource (lib "Libraries R&D by Sang Hoang") (part "Resistor"))
    )
    (comp (ref "R73")
      (value "150")
      (footprint "RES 0805")
      (libsource (lib "Libraries R&D by Sang Hoang") (part "Resistor"))
    )
    (comp (ref "R74")
      (value "150")
      (footprint "RES 0805")
      (libsource (lib "Libraries R&D by Sang Hoang") (part "Resistor"))
    )
    (comp (ref "R75")
      (value "150")
      (footprint "RES 0805")
      (libsource (lib "Libraries R&D by Sang Hoang") (part "Resistor"))
    )
    (comp (ref "R76")
      (value "150")
      (footprint "RES 0805")
      (libsource (lib "Libraries R&D by Sang Hoang") (part "Resistor"))
    )
    (comp (ref "R77")
      (value "150")
      (footprint "RES 0805")
      (libsource (lib "Libraries R&D by Sang Hoang") (part "Resistor"))
    )
    (comp (ref "R78")
      (value "150")
      (footprint "RES 0805")
      (libsource (lib "Libraries R&D by Sang Hoang") (part "Resistor"))
    )
    (comp (ref "R79")
      (value "150")
      (footprint "RES 0805")
      (libsource (lib "Libraries R&D by Sang Hoang") (part "Resistor"))
    )
    (comp (ref "R80")
      (value "150")
      (footprint "RES 0805")
      (libsource (lib "Libraries R&D by Sang Hoang") (part "Resistor"))
    )
    (comp (ref "R81")
      (value "150")
      (footprint "RES 0805")
      (libsource (lib "Libraries R&D by Sang Hoang") (part "Resistor"))
    )
    (comp (ref "R82")
      (value "150")
      (footprint "RES 0805")
      (libsource (lib "Libraries R&D by Sang Hoang") (part "Resistor"))
    )
    (comp (ref "R83")
      (value "150")
      (footprint "RES 0805")
      (libsource (lib "Libraries R&D by Sang Hoang") (part "Resistor"))
    )
    (comp (ref "R84")
      (value "150")
      (footprint "RES 0805")
      (libsource (lib "Libraries R&D by Sang Hoang") (part "Resistor"))
    )
    (comp (ref "R85")
      (value "150")
      (footprint "RES 0805")
      (libsource (lib "Libraries R&D by Sang Hoang") (part "Resistor"))
    )
    (comp (ref "R86")
      (value "150")
      (footprint "RES 0805")
      (libsource (lib "Libraries R&D by Sang Hoang") (part "Resistor"))
    )
    (comp (ref "R87")
      (value "150")
      (footprint "RES 0805")
      (libsource (lib "Libraries R&D by Sang Hoang") (part "Resistor"))
    )
    (comp (ref "R88")
      (value "150")
      (footprint "RES 0805")
      (libsource (lib "Libraries R&D by Sang Hoang") (part "Resistor"))
    )
    (comp (ref "R89")
      (value "150")
      (footprint "RES 0805")
      (libsource (lib "Libraries R&D by Sang Hoang") (part "Resistor"))
    )
    (comp (ref "R90")
      (value "150")
      (footprint "RES 0805")
      (libsource (lib "Libraries R&D by Sang Hoang") (part "Resistor"))
    )
    (comp (ref "R91")
      (value "150")
      (footprint "RES 0805")
      (libsource (lib "Libraries R&D by Sang Hoang") (part "Resistor"))
    )
    (comp (ref "R92")
      (value "150")
      (footprint "RES 0805")
      (libsource (lib "Libraries R&D by Sang Hoang") (part "Resistor"))
    )
    (comp (ref "R93")
      (value "150")
      (footprint "RES 0805")
      (libsource (lib "Libraries R&D by Sang Hoang") (part "Resistor"))
    )
    (comp (ref "R94")
      (value "150")
      (footprint "RES 0805")
      (libsource (lib "Libraries R&D by Sang Hoang") (part "Resistor"))
    )
    (comp (ref "R95")
      (value "150")
      (footprint "RES 0805")
      (libsource (lib "Libraries R&D by Sang Hoang") (part "Resistor"))
    )
    (comp (ref "R96")
      (value "150")
      (footprint "RES 0805")
      (libsource (lib "Libraries R&D by Sang Hoang") (part "Resistor"))
    )
    (comp (ref "R97")
      (value "150")
      (footprint "RES 0805")
      (libsource (lib "Libraries R&D by Sang Hoang") (part "Resistor"))
    )
    (comp (ref "R98")
      (value "150")
      (footprint "RES 0805")
      (libsource (lib "Libraries R&D by Sang Hoang") (part "Resistor"))
    )
    (comp (ref "R99")
      (value "150")
      (footprint "RES 0805")
      (libsource (lib "Libraries R&D by Sang Hoang") (part "Resistor"))
    )
    (comp (ref "R100")
      (value "150")
      (footprint "RES 0805")
      (libsource (lib "Libraries R&D by Sang Hoang") (part "Resistor"))
    )
    (comp (ref "R101")
      (value "150")
      (footprint "RES 0805")
      (libsource (lib "Libraries R&D by Sang Hoang") (part "Resistor"))
    )
    (comp (ref "R102")
      (value "150")
      (footprint "RES 0805")
      (libsource (lib "Libraries R&D by Sang Hoang") (part "Resistor"))
    )
    (comp (ref "R103")
      (value "150")
      (footprint "RES 0805")
      (libsource (lib "Libraries R&D by Sang Hoang") (part "Resistor"))
    )
    (comp (ref "R104")
      (value "150")
      (footprint "RES 0805")
      (libsource (lib "Libraries R&D by Sang Hoang") (part "Resistor"))
    )
    (comp (ref "R105")
      (value "150")
      (footprint "RES 0805")
      (libsource (lib "Libraries R&D by Sang Hoang") (part "Resistor"))
    )
    (comp (ref "R106")
      (value "150")
      (footprint "RES 0805")
      (libsource (lib "Libraries R&D by Sang Hoang") (part "Resistor"))
    )
    (comp (ref "R107")
      (value "150")
      (footprint "RES 0805")
      (libsource (lib "Libraries R&D by Sang Hoang") (part "Resistor"))
    )
    (comp (ref "R108")
      (value "150")
      (footprint "RES 0805")
      (libsource (lib "Libraries R&D by Sang Hoang") (part "Resistor"))
    )
    (comp (ref "R109")
      (value "150")
      (footprint "RES 0805")
      (libsource (lib "Libraries R&D by Sang Hoang") (part "Resistor"))
    )
    (comp (ref "R110")
      (value "150")
      (footprint "RES 0805")
      (libsource (lib "Libraries R&D by Sang Hoang") (part "Resistor"))
    )
    (comp (ref "R111")
      (value "150")
      (footprint "RES 0805")
      (libsource (lib "Libraries R&D by Sang Hoang") (part "Resistor"))
    )
    (comp (ref "R112")
      (value "150")
      (footprint "RES 0805")
      (libsource (lib "Libraries R&D by Sang Hoang") (part "Resistor"))
    )
    (comp (ref "R113")
      (value "150")
      (footprint "RES 0805")
      (libsource (lib "Libraries R&D by Sang Hoang") (part "Resistor"))
    )
    (comp (ref "R114")
      (value "150")
      (footprint "RES 0805")
      (libsource (lib "Libraries R&D by Sang Hoang") (part "Resistor"))
    )
    (comp (ref "R115")
      (value "150")
      (footprint "RES 0805")
      (libsource (lib "Libraries R&D by Sang Hoang") (part "Resistor"))
    )
    (comp (ref "R116")
      (value "150")
      (footprint "RES 0805")
      (libsource (lib "Libraries R&D by Sang Hoang") (part "Resistor"))
    )
    (comp (ref "R117")
      (value "150")
      (footprint "RES 0805")
      (libsource (lib "Libraries R&D by Sang Hoang") (part "Resistor"))
    )
    (comp (ref "R118")
      (value "150")
      (footprint "RES 0805")
      (libsource (lib "Libraries R&D by Sang Hoang") (part "Resistor"))
    )
    (comp (ref "R119")
      (value "150")
      (footprint "RES 0805")
      (libsource (lib "Libraries R&D by Sang Hoang") (part "Resistor"))
    )
    (comp (ref "R120")
      (value "150")
      (footprint "RES 0805")
      (libsource (lib "Libraries R&D by Sang Hoang") (part "Resistor"))
    )
    (comp (ref "R121")
      (value "470")
      (footprint "RES 0805")
      (libsource (lib "Libraries R&D by Sang Hoang") (part "Resistor"))
    )
    (comp (ref "R122")
      (value "150")
      (footprint "RES 0805")
      (libsource (lib "Libraries R&D by Sang Hoang") (part "Resistor"))
    )
    (comp (ref "R123")
      (value "150")
      (footprint "RES 0805")
      (libsource (lib "Libraries R&D by Sang Hoang") (part "Resistor"))
    )
    (comp (ref "R124")
      (value "150")
      (footprint "RES 0805")
      (libsource (lib "Libraries R&D by Sang Hoang") (part "Resistor"))
    )
    (comp (ref "R125")
      (value "150")
      (footprint "RES 0805")
      (libsource (lib "Libraries R&D by Sang Hoang") (part "Resistor"))
    )
    (comp (ref "R126")
      (value "150")
      (footprint "RES 0805")
      (libsource (lib "Libraries R&D by Sang Hoang") (part "Resistor"))
    )
    (comp (ref "R127")
      (value "150")
      (footprint "RES 0805")
      (libsource (lib "Libraries R&D by Sang Hoang") (part "Resistor"))
    )
    (comp (ref "R128")
      (value "150")
      (footprint "RES 0805")
      (libsource (lib "Libraries R&D by Sang Hoang") (part "Resistor"))
    )
    (comp (ref "R129")
      (value "150")
      (footprint "RES 0805")
      (libsource (lib "Libraries R&D by Sang Hoang") (part "Resistor"))
    )
    (comp (ref "R130")
      (value "150")
      (footprint "RES 0805")
      (libsource (lib "Libraries R&D by Sang Hoang") (part "Resistor"))
    )
    (comp (ref "R131")
      (value "150")
      (footprint "RES 0805")
      (libsource (lib "Libraries R&D by Sang Hoang") (part "Resistor"))
    )
    (comp (ref "R132")
      (value "150")
      (footprint "RES 0805")
      (libsource (lib "Libraries R&D by Sang Hoang") (part "Resistor"))
    )
    (comp (ref "R133")
      (value "150")
      (footprint "RES 0805")
      (libsource (lib "Libraries R&D by Sang Hoang") (part "Resistor"))
    )
    (comp (ref "R134")
      (value "150")
      (footprint "RES 0805")
      (libsource (lib "Libraries R&D by Sang Hoang") (part "Resistor"))
    )
    (comp (ref "R135")
      (value "150")
      (footprint "RES 0805")
      (libsource (lib "Libraries R&D by Sang Hoang") (part "Resistor"))
    )
    (comp (ref "R136")
      (value "150")
      (footprint "RES 0805")
      (libsource (lib "Libraries R&D by Sang Hoang") (part "Resistor"))
    )
    (comp (ref "R137")
      (value "150")
      (footprint "RES 0805")
      (libsource (lib "Libraries R&D by Sang Hoang") (part "Resistor"))
    )
    (comp (ref "R138")
      (value "150")
      (footprint "RES 0805")
      (libsource (lib "Libraries R&D by Sang Hoang") (part "Resistor"))
    )
    (comp (ref "R139")
      (value "150")
      (footprint "RES 0805")
      (libsource (lib "Libraries R&D by Sang Hoang") (part "Resistor"))
    )
    (comp (ref "R140")
      (value "150")
      (footprint "RES 0805")
      (libsource (lib "Libraries R&D by Sang Hoang") (part "Resistor"))
    )
    (comp (ref "R141")
      (value "150")
      (footprint "RES 0805")
      (libsource (lib "Libraries R&D by Sang Hoang") (part "Resistor"))
    )
    (comp (ref "R142")
      (value "150")
      (footprint "RES 0805")
      (libsource (lib "Libraries R&D by Sang Hoang") (part "Resistor"))
    )
    (comp (ref "R143")
      (value "150")
      (footprint "RES 0805")
      (libsource (lib "Libraries R&D by Sang Hoang") (part "Resistor"))
    )
    (comp (ref "R144")
      (value "150")
      (footprint "RES 0805")
      (libsource (lib "Libraries R&D by Sang Hoang") (part "Resistor"))
    )
    (comp (ref "R145")
      (value "150")
      (footprint "RES 0805")
      (libsource (lib "Libraries R&D by Sang Hoang") (part "Resistor"))
    )
    (comp (ref "R146")
      (value "150")
      (footprint "RES 0805")
      (libsource (lib "Libraries R&D by Sang Hoang") (part "Resistor"))
    )
    (comp (ref "R147")
      (value "150")
      (footprint "RES 0805")
      (libsource (lib "Libraries R&D by Sang Hoang") (part "Resistor"))
    )
    (comp (ref "R148")
      (value "150")
      (footprint "RES 0805")
      (libsource (lib "Libraries R&D by Sang Hoang") (part "Resistor"))
    )
    (comp (ref "R149")
      (value "150")
      (footprint "RES 0805")
      (libsource (lib "Libraries R&D by Sang Hoang") (part "Resistor"))
    )
    (comp (ref "R150")
      (value "150")
      (footprint "RES 0805")
      (libsource (lib "Libraries R&D by Sang Hoang") (part "Resistor"))
    )
    (comp (ref "R151")
      (value "150")
      (footprint "RES 0805")
      (libsource (lib "Libraries R&D by Sang Hoang") (part "Resistor"))
    )
    (comp (ref "R152")
      (value "150")
      (footprint "RES 0805")
      (libsource (lib "Libraries R&D by Sang Hoang") (part "Resistor"))
    )
    (comp (ref "R153")
      (value "150")
      (footprint "RES 0805")
      (libsource (lib "Libraries R&D by Sang Hoang") (part "Resistor"))
    )
    (comp (ref "R154")
      (value "3.3k")
      (footprint "RES 0805")
      (libsource (lib "Libraries R&D by Sang Hoang") (part "Resistor"))
    )
    (comp (ref "R155")
      (value "3.3k")
      (footprint "RES 0805")
      (libsource (lib "Libraries R&D by Sang Hoang") (part "Resistor"))
    )
    (comp (ref "R156")
      (value "3.3k")
      (footprint "RES 0805")
      (libsource (lib "Libraries R&D by Sang Hoang") (part "Resistor"))
    )
    (comp (ref "R157")
      (value "3.3k")
      (footprint "RES 0805")
      (libsource (lib "Libraries R&D by Sang Hoang") (part "Resistor"))
    )
    (comp (ref "R158")
      (value "2k")
      (footprint "RES 0805")
      (libsource (lib "Libraries R&D by Sang Hoang") (part "Resistor"))
    )
    (comp (ref "R159")
      (value "330")
      (footprint "RES 0805")
      (libsource (lib "Libraries R&D by Sang Hoang") (part "Resistor"))
    )
    (comp (ref "R160")
      (value "470")
      (footprint "RES 0805")
      (libsource (lib "Libraries R&D by Sang Hoang") (part "Resistor"))
    )
    (comp (ref "R161")
      (value "22k")
      (footprint "RES 0805")
      (libsource (lib "Libraries R&D by Sang Hoang") (part "Resistor"))
    )
    (comp (ref "R162")
      (value "22k")
      (footprint "RES 0805")
      (libsource (lib "Libraries R&D by Sang Hoang") (part "Resistor"))
    )
    (comp (ref "R163")
      (value "10k")
      (footprint "RES 0805")
      (libsource (lib "Libraries R&D by Sang Hoang") (part "Resistor"))
    )
    (comp (ref "R164")
      (value "10k")
      (footprint "RES 0805")
      (libsource (lib "Libraries R&D by Sang Hoang") (part "Resistor"))
    )
    (comp (ref "R165")
      (value "10k")
      (footprint "RES 0805")
      (libsource (lib "Libraries R&D by Sang Hoang") (part "Resistor"))
    )
    (comp (ref "R166")
      (value "4.7k")
      (footprint "RES 0805")
      (libsource (lib "Libraries R&D by Sang Hoang") (part "Resistor"))
    )
    (comp (ref "R167")
      (value "10k")
      (footprint "RES 0805")
      (libsource (lib "Libraries R&D by Sang Hoang") (part "Resistor"))
    )
    (comp (ref "SD1")
      (value "Micro SD")
      (footprint "TF Micro SD")
      (libsource (lib "Libraries R&D by Sang Hoang") (part "Micro SD"))
    )
    (comp (ref "SP1")
      (value "Speaker")
      (footprint "Speaker 2W 35x25")
      (libsource (lib "Libraries R&D by Sang Hoang") (part "Speaker"))
    )
    (comp (ref "SP2")
      (value "Speaker")
      (footprint "Speaker 2W 35x25")
      (libsource (lib "Libraries R&D by Sang Hoang") (part "Speaker"))
    )
    (comp (ref "SW1")
      (value "Switch 3")
      (footprint "Switch 3P SK12D07VG4")
      (libsource (lib "Libraries R&D by Sang Hoang") (part "Switch 3"))
    )
    (comp (ref "U1")
      (value "ESP32-S3-WROOM-1")
      (footprint "ESP32-S3")
      (libsource (lib "") (part "ESP32-S3-WROOM-1_1"))
    )
    (comp (ref "U2")
      (value "74HC595")
      (footprint "SOIC-16")
      (libsource (lib "Libraries R&D by Sang Hoang") (part "74HC595"))
    )
    (comp (ref "U3")
      (value "ESP32-S3-WROOM-1")
      (footprint "ESP32-S3")
      (libsource (lib "Libraries R&D by Sang Hoang") (part "ESP32-S3-WROOM-1"))
    )
    (comp (ref "U4")
      (value "74HC595")
      (footprint "SOIC-16")
      (libsource (lib "Libraries R&D by Sang Hoang") (part "74HC595"))
    )
    (comp (ref "U5")
      (value "74HC595")
      (footprint "SOIC-16")
      (libsource (lib "Libraries R&D by Sang Hoang") (part "74HC595"))
    )
    (comp (ref "U6")
      (value "74HC595")
      (footprint "SOIC-16")
      (libsource (lib "Libraries R&D by Sang Hoang") (part "74HC595"))
    )
    (comp (ref "U7")
      (value "74HC595")
      (footprint "SOIC-16")
      (libsource (lib "Libraries R&D by Sang Hoang") (part "74HC595"))
    )
    (comp (ref "U8")
      (value "74HC595")
      (footprint "SOIC-16")
      (libsource (lib "Libraries R&D by Sang Hoang") (part "74HC595"))
    )
    (comp (ref "U9")
      (value "XL6009")
      (footprint "TO-263-5L")
      (libsource (lib "Libraries R&D by Sang Hoang") (part "XL6009"))
    )
    (comp (ref "U10")
      (value "TP4056")
      (footprint "ESOP8")
      (libsource (lib "Libraries R&D by Sang Hoang") (part "TP4056"))
    )
    (comp (ref "U11")
      (value "MPU6050")
      (footprint "QFN-24")
      (libsource (lib "Libraries R&D by Sang Hoang") (part "MPU6050"))
    )
    (comp (ref "U12")
      (value "74HC595")
      (footprint "SOIC-16")
      (libsource (lib "Libraries R&D by Sang Hoang") (part "74HC595"))
    )
    (comp (ref "U13")
      (value "74HC595")
      (footprint "SOIC-16")
      (libsource (lib "Libraries R&D by Sang Hoang") (part "74HC595"))
    )
    (comp (ref "U14")
      (value "74HC595")
      (footprint "SOIC-16")
      (libsource (lib "Libraries R&D by Sang Hoang") (part "74HC595"))
    )
    (comp (ref "U15")
      (value "LM1084IS")
      (footprint "TO-263")
      (libsource (lib "Libraries R&D by Sang Hoang") (part "LM1084IS"))
    )
    (comp (ref "U16")
      (value "74HC595")
      (footprint "SOIC-16")
      (libsource (lib "Libraries R&D by Sang Hoang") (part "74HC595"))
    )
    (comp (ref "U17")
      (value "74HC595")
      (footprint "SOIC-16")
      (libsource (lib "Libraries R&D by Sang Hoang") (part "74HC595"))
    )
    (comp (ref "U18")
      (value "74HC595")
      (footprint "SOIC-16")
      (libsource (lib "Libraries R&D by Sang Hoang") (part "74HC595"))
    )
    (comp (ref "U19")
      (value "74HC595")
      (footprint "SOIC-16")
      (libsource (lib "Libraries R&D by Sang Hoang") (part "74HC595"))
    )
    (comp (ref "U20")
      (value "74HC595")
      (footprint "SOIC-16")
      (libsource (lib "Libraries R&D by Sang Hoang") (part "74HC595"))
    )
    (comp (ref "U21")
      (value "74HC595")
      (footprint "SOIC-16")
      (libsource (lib "Libraries R&D by Sang Hoang") (part "74HC595"))
    )
    (comp (ref "U22")
      (value "74HC595")
      (footprint "SOIC-16")
      (libsource (lib "Libraries R&D by Sang Hoang") (part "74HC595"))
    )
    (comp (ref "U23")
      (value "74HC595")
      (footprint "SOIC-16")
      (libsource (lib "Libraries R&D by Sang Hoang") (part "74HC595"))
    )
    (comp (ref "U24")
      (value "74HC595")
      (footprint "SOIC-16")
      (libsource (lib "Libraries R&D by Sang Hoang") (part "74HC595"))
    )
    (comp (ref "U25")
      (value "PCM5102A")
      (footprint "TSSOP-20")
      (libsource (lib "Libraries R&D by Sang Hoang") (part "PCM5102A"))
    )
    (comp (ref "U26")
      (value "74HC595")
      (footprint "SOIC-16")
      (libsource (lib "Libraries R&D by Sang Hoang") (part "74HC595"))
    )
    (comp (ref "U27")
      (value "74HC595")
      (footprint "SOIC-16")
      (libsource (lib "Libraries R&D by Sang Hoang") (part "74HC595"))
    )
    (comp (ref "U28")
      (value "74HC595")
      (footprint "SOIC-16")
      (libsource (lib "Libraries R&D by Sang Hoang") (part "74HC595"))
    )
    (comp (ref "U29")
      (value "74HC595")
      (footprint "SOIC-16")
      (libsource (lib "Libraries R&D by Sang Hoang") (part "74HC595"))
    )
    (comp (ref "U30")
      (value "74HC595")
      (footprint "SOIC-16")
      (libsource (lib "Libraries R&D by Sang Hoang") (part "74HC595"))
    )
    (comp (ref "U31")
      (value "74HC595")
      (footprint "SOIC-16")
      (libsource (lib "Libraries R&D by Sang Hoang") (part "74HC595"))
    )
    (comp (ref "U32")
      (value "74LVC125APW")
      (footprint "TSSOP-14")
      (libsource (lib "Libraries R&D by Sang Hoang") (part "74LVC125APW"))
    )
    (comp (ref "U33")
      (value "PAM8403")
      (footprint "SOP-16")
      (libsource (lib "Libraries R&D by Sang Hoang") (part "PAM8403"))
    )
    (comp (ref "U34")
      (value "CH340G")
      (footprint "CH340G")
      (libsource (lib "Libraries R&D by Sang Hoang") (part "CH340G"))
    )
    (comp (ref "X1")
      (value "12MHz")
      (footprint "Crytal SMD")
      (libsource (lib "Libraries R&D by Sang Hoang") (part "Crytal"))
    )
  )
  (nets
    (net (code "1") (name "+3V3") (class "Default")
      (node (ref "C11") (pin "2") (pinfunction "2_2") (pintype "passive"))
      (node (ref "C13") (pin "1") (pinfunction "1_1") (pintype "passive"))
      (node (ref "C14") (pin "2") (pinfunction "2_2") (pintype "passive"))
      (node (ref "C23") (pin "2") (pinfunction "2_2") (pintype "passive"))
      (node (ref "C26") (pin "2") (pinfunction "2_2") (pintype "passive"))
      (node (ref "C9") (pin "1") (pinfunction "1_1") (pintype "passive"))
      (node (ref "CN4") (pin "2") (pinfunction "2_2") (pintype "passive"))
      (node (ref "CN5") (pin "3") (pinfunction "3_3") (pintype "passive"))
      (node (ref "DP1") (pin "1") (pinfunction "VDD_1") (pintype "power_in"))
      (node (ref "J1") (pin "H1") (pinfunction "H+_H1") (pintype "passive"))
      (node (ref "J1") (pin "V1") (pinfunction "V+_V1") (pintype "passive"))
      (node (ref "J4") (pin "H1") (pinfunction "H+_H1") (pintype "passive"))
      (node (ref "J4") (pin "V1") (pinfunction "V+_V1") (pintype "passive"))
      (node (ref "MIC1") (pin "2") (pinfunction "VCC_2") (pintype "passive"))
      (node (ref "R1") (pin "2") (pinfunction "2_2") (pintype "passive"))
      (node (ref "R10") (pin "2") (pinfunction "2_2") (pintype "passive"))
      (node (ref "R11") (pin "2") (pinfunction "2_2") (pintype "passive"))
      (node (ref "R12") (pin "2") (pinfunction "2_2") (pintype "passive"))
      (node (ref "R16") (pin "2") (pinfunction "2_2") (pintype "passive"))
      (node (ref "R161") (pin "1") (pinfunction "1_1") (pintype "passive"))
      (node (ref "R162") (pin "1") (pinfunction "1_1") (pintype "passive"))
      (node (ref "R18") (pin "2") (pinfunction "2_2") (pintype "passive"))
      (node (ref "R19") (pin "1") (pinfunction "1_1") (pintype "passive"))
      (node (ref "R2") (pin "2") (pinfunction "2_2") (pintype "passive"))
      (node (ref "R20") (pin "1") (pinfunction "1_1") (pintype "passive"))
      (node (ref "R21") (pin "1") (pinfunction "1_1") (pintype "passive"))
      (node (ref "R22") (pin "1") (pinfunction "1_1") (pintype "passive"))
      (node (ref "R3") (pin "2") (pinfunction "2_2") (pintype "passive"))
      (node (ref "R4") (pin "2") (pinfunction "2_2") (pintype "passive"))
      (node (ref "R5") (pin "2") (pinfunction "2_2") (pintype "passive"))
      (node (ref "R6") (pin "2") (pinfunction "2_2") (pintype "passive"))
      (node (ref "R7") (pin "2") (pinfunction "2_2") (pintype "passive"))
      (node (ref "R8") (pin "2") (pinfunction "2_2") (pintype "passive"))
      (node (ref "R9") (pin "2") (pinfunction "2_2") (pintype "passive"))
      (node (ref "SD1") (pin "P4") (pinfunction "VDD_P4") (pintype "passive"))
      (node (ref "U1") (pin "2") (pinfunction "3V3_2") (pintype "power_in"))
      (node (ref "U11") (pin "13") (pinfunction "VDD_13") (pintype "power_in"))
      (node (ref "U12") (pin "10") (pinfunction "RESET_10") (pintype "input"))
      (node (ref "U12") (pin "16") (pinfunction "VCC_16") (pintype "power_in"))
      (node (ref "U13") (pin "10") (pinfunction "RESET_10") (pintype "input"))
      (node (ref "U13") (pin "16") (pinfunction "VCC_16") (pintype "power_in"))
      (node (ref "U14") (pin "10") (pinfunction "RESET_10") (pintype "input"))
      (node (ref "U14") (pin "16") (pinfunction "VCC_16") (pintype "power_in"))
      (node (ref "U15") (pin "2") (pinfunction "OUTPUT_2") (pintype "power_in"))
      (node (ref "U15") (pin "4") (pinfunction "OUTPUT_4") (pintype "power_in"))
      (node (ref "U16") (pin "10") (pinfunction "RESET_10") (pintype "input"))
      (node (ref "U16") (pin "16") (pinfunction "VCC_16") (pintype "power_in"))
      (node (ref "U17") (pin "10") (pinfunction "RESET_10") (pintype "input"))
      (node (ref "U17") (pin "16") (pinfunction "VCC_16") (pintype "power_in"))
      (node (ref "U18") (pin "10") (pinfunction "RESET_10") (pintype "input"))
      (node (ref "U18") (pin "16") (pinfunction "VCC_16") (pintype "power_in"))
      (node (ref "U19") (pin "10") (pinfunction "RESET_10") (pintype "input"))
      (node (ref "U19") (pin "16") (pinfunction "VCC_16") (pintype "power_in"))
      (node (ref "U2") (pin "10") (pinfunction "RESET_10") (pintype "input"))
      (node (ref "U2") (pin "16") (pinfunction "VCC_16") (pintype "power_in"))
      (node (ref "U20") (pin "10") (pinfunction "RESET_10") (pintype "input"))
      (node (ref "U20") (pin "16") (pinfunction "VCC_16") (pintype "power_in"))
      (node (ref "U21") (pin "10") (pinfunction "RESET_10") (pintype "input"))
      (node (ref "U21") (pin "16") (pinfunction "VCC_16") (pintype "power_in"))
      (node (ref "U22") (pin "10") (pinfunction "RESET_10") (pintype "input"))
      (node (ref "U22") (pin "16") (pinfunction "VCC_16") (pintype "power_in"))
      (node (ref "U23") (pin "10") (pinfunction "RESET_10") (pintype "input"))
      (node (ref "U23") (pin "16") (pinfunction "VCC_16") (pintype "power_in"))
      (node (ref "U24") (pin "10") (pinfunction "RESET_10") (pintype "input"))
      (node (ref "U24") (pin "16") (pinfunction "VCC_16") (pintype "power_in"))
      (node (ref "U25") (pin "1") (pinfunction "CPVDD_1") (pintype "power_in"))
      (node (ref "U25") (pin "20") (pinfunction "DVDD_20") (pintype "power_in"))
      (node (ref "U25") (pin "8") (pinfunction "AVDD_8") (pintype "power_in"))
      (node (ref "U26") (pin "10") (pinfunction "RESET_10") (pintype "input"))
      (node (ref "U26") (pin "16") (pinfunction "VCC_16") (pintype "power_in"))
      (node (ref "U27") (pin "10") (pinfunction "RESET_10") (pintype "input"))
      (node (ref "U27") (pin "16") (pinfunction "VCC_16") (pintype "power_in"))
      (node (ref "U28") (pin "10") (pinfunction "RESET_10") (pintype "input"))
      (node (ref "U28") (pin "16") (pinfunction "VCC_16") (pintype "power_in"))
      (node (ref "U29") (pin "10") (pinfunction "RESET_10") (pintype "input"))
      (node (ref "U29") (pin "16") (pinfunction "VCC_16") (pintype "power_in"))
      (node (ref "U3") (pin "2") (pinfunction "3V3_2") (pintype "power_in"))
      (node (ref "U30") (pin "10") (pinfunction "RESET_10") (pintype "input"))
      (node (ref "U30") (pin "16") (pinfunction "VCC_16") (pintype "power_in"))
      (node (ref "U31") (pin "10") (pinfunction "RESET_10") (pintype "input"))
      (node (ref "U31") (pin "16") (pinfunction "VCC_16") (pintype "power_in"))
      (node (ref "U32") (pin "14") (pinfunction "VCC_14") (pintype "power_in"))
      (node (ref "U33") (pin "6") (pinfunction "VDD_6") (pintype "power_in"))
      (node (ref "U34") (pin "4") (pinfunction "V3_4") (pintype "power_in"))
      (node (ref "U4") (pin "10") (pinfunction "RESET_10") (pintype "input"))
      (node (ref "U4") (pin "16") (pinfunction "VCC_16") (pintype "power_in"))
      (node (ref "U5") (pin "10") (pinfunction "RESET_10") (pintype "input"))
      (node (ref "U5") (pin "16") (pinfunction "VCC_16") (pintype "power_in"))
      (node (ref "U6") (pin "10") (pinfunction "RESET_10") (pintype "input"))
      (node (ref "U6") (pin "16") (pinfunction "VCC_16") (pintype "power_in"))
      (node (ref "U7") (pin "10") (pinfunction "RESET_10") (pintype "input"))
      (node (ref "U7") (pin "16") (pinfunction "VCC_16") (pintype "power_in"))
      (node (ref "U8") (pin "10") (pinfunction "RESET_10") (pintype "input"))
      (node (ref "U8") (pin "16") (pinfunction "VCC_16") (pintype "power_in"))
    )
    (net (code "2") (name "+5") (class "Default")
      (node (ref "C6") (pin "1") (pinfunction "1_1") (pintype "passive"))
      (node (ref "D6") (pin "K") (pinfunction "K_K") (pintype "passive"))
      (node (ref "R24") (pin "2") (pinfunction "2_2") (pintype "passive"))
      (node (ref "U15") (pin "3") (pinfunction "INPUT_3") (pintype "passive"))
    )
    (net (code "3") (name "+5_USB") (class "Default")
      (node (ref "C1") (pin "2") (pinfunction "2_2") (pintype "passive"))
      (node (ref "C2") (pin "2") (pinfunction "2_2") (pintype "passive"))
      (node (ref "CN1") (pin "A4_B9") (pinfunction "VBUS_A4_B9") (pintype "power_in"))
      (node (ref "CN1") (pin "B4_A9") (pinfunction "VBUS_B4_A9") (pintype "power_in"))
      (node (ref "D8") (pin "A") (pinfunction "A_A") (pintype "passive"))
      (node (ref "F1") (pin "2") (pinfunction "2_2") (pintype "passive"))
      (node (ref "J2") (pin "2") (pinfunction "2_2") (pintype "passive"))
      (node (ref "R13") (pin "2") (pinfunction "2_2") (pintype "passive"))
      (node (ref "R23") (pin "2") (pinfunction "2_2") (pintype "passive"))
    )
    (net (code "4") (name "/ANL_H1") (class "Default")
      (node (ref "J1") (pin "H2") (pinfunction "H_H2") (pintype "passive"))
      (node (ref "U1") (pin "38") (pinfunction "IO2_38") (pintype "bidirectional"))
    )
    (net (code "5") (name "/ANL_H2") (class "Default")
      (node (ref "J4") (pin "H2") (pinfunction "H_H2") (pintype "passive"))
      (node (ref "U1") (pin "5") (pinfunction "IO5_5") (pintype "bidirectional"))
    )
    (net (code "6") (name "/ANL_V1") (class "Default")
      (node (ref "J1") (pin "V2") (pinfunction "V_V2") (pintype "passive"))
      (node (ref "U1") (pin "39") (pinfunction "IO1_39") (pintype "bidirectional"))
    )
    (net (code "7") (name "/ANL_V2") (class "Default")
      (node (ref "J4") (pin "V2") (pinfunction "V_V2") (pintype "passive"))
      (node (ref "U1") (pin "4") (pinfunction "IO4_4") (pintype "bidirectional"))
    )
    (net (code "8") (name "/BAT+") (class "Default")
      (node (ref "BAT1") (pin "P") (pinfunction "POS_P") (pintype "passive"))
      (node (ref "BAT2") (pin "P") (pinfunction "POS_P") (pintype "passive"))
      (node (ref "C4") (pin "2") (pinfunction "2_2") (pintype "passive"))
      (node (ref "C5") (pin "1") (pinfunction "1_1") (pintype "passive"))
      (node (ref "F2") (pin "1") (pinfunction "1_1") (pintype "passive"))
      (node (ref "U10") (pin "5") (pinfunction "BAT_5") (pintype "output"))
    )
    (net (code "9") (name "/BCLK_AUDIO") (class "Default")
      (node (ref "U25") (pin "13") (pinfunction "BCK_13") (pintype "input"))
      (node (ref "U3") (pin "6") (pinfunction "IO6_6") (pintype "bidirectional"))
    )
    (net (code "10") (name "/BOOT_ESP32-1") (class "Default")
      (node (ref "BT8") (pin "1") (pintype "passive"))
      (node (ref "R11") (pin "1") (pinfunction "1_1") (pintype "passive"))
      (node (ref "U1") (pin "27") (pinfunction "IO0_27") (pintype "bidirectional"))
    )
    (net (code "11") (name "/BT_J1") (class "Default")
      (node (ref "J1") (pin "B2A") (pinfunction "BUT_B2A") (pintype "passive"))
      (node (ref "R7") (pin "1") (pinfunction "1_1") (pintype "passive"))
      (node (ref "U1") (pin "20") (pinfunction "IO12_20") (pintype "bidirectional"))
    )
    (net (code "12") (name "/BT_J2") (class "Default")
      (node (ref "J4") (pin "B2A") (pinfunction "BUT_B2A") (pintype "passive"))
      (node (ref "R8") (pin "1") (pinfunction "1_1") (pintype "passive"))
      (node (ref "U1") (pin "6") (pinfunction "IO6_6") (pintype "bidirectional"))
    )
    (net (code "13") (name "/BT_P1") (class "Default")
      (node (ref "BT11") (pin "1") (pintype "passive"))
      (node (ref "R5") (pin "1") (pinfunction "1_1") (pintype "passive"))
      (node (ref "U1") (pin "7") (pinfunction "IO7_7") (pintype "bidirectional"))
    )
    (net (code "14") (name "/BT_P2") (class "Default")
      (node (ref "BT6") (pin "1") (pintype "passive"))
      (node (ref "R6") (pin "1") (pinfunction "1_1") (pintype "passive"))
      (node (ref "U1") (pin "8") (pinfunction "IO15_8") (pintype "bidirectional"))
    )
    (net (code "15") (name "/BT_P3") (class "Default")
      (node (ref "BT4") (pin "1") (pintype "passive"))
      (node (ref "R16") (pin "1") (pinfunction "1_1") (pintype "passive"))
      (node (ref "U1") (pin "9") (pinfunction "IO16_9") (pintype "bidirectional"))
    )
    (net (code "16") (name "/BT_P4") (class "Default")
      (node (ref "BT2") (pin "1") (pintype "passive"))
      (node (ref "R18") (pin "1") (pinfunction "1_1") (pintype "passive"))
      (node (ref "U1") (pin "12") (pinfunction "IO8_12") (pintype "bidirectional"))
    )
    (net (code "17") (name "/BT_T1") (class "Default")
      (node (ref "BT12") (pin "2") (pintype "passive"))
      (node (ref "R4") (pin "1") (pinfunction "1_1") (pintype "passive"))
      (node (ref "U1") (pin "15") (pinfunction "IO3_15") (pintype "bidirectional"))
    )
    (net (code "18") (name "/BT_T2") (class "Default")
      (node (ref "BT5") (pin "2") (pintype "passive"))
      (node (ref "R3") (pin "1") (pinfunction "1_1") (pintype "passive"))
      (node (ref "U1") (pin "18") (pinfunction "IO10_18") (pintype "bidirectional"))
    )
    (net (code "19") (name "/BT_T3") (class "Default")
      (node (ref "BT3") (pin "2") (pintype "passive"))
      (node (ref "R2") (pin "1") (pinfunction "1_1") (pintype "passive"))
      (node (ref "U1") (pin "17") (pinfunction "IO9_17") (pintype "bidirectional"))
    )
    (net (code "20") (name "/BT_T4") (class "Default")
      (node (ref "BT1") (pin "2") (pintype "passive"))
      (node (ref "R1") (pin "1") (pinfunction "1_1") (pintype "passive"))
      (node (ref "U1") (pin "19") (pinfunction "IO11_19") (pintype "bidirectional"))
    )
    (net (code "21") (name "/COL_D1_1") (class "Default")
      (node (ref "R25") (pin "2") (pinfunction "2_2") (pintype "passive"))
      (node (ref "U4") (pin "15") (pinfunction "QA_15") (pintype "output"))
    )
    (net (code "22") (name "/COL_D1_2") (class "Default")
      (node (ref "R26") (pin "2") (pinfunction "2_2") (pintype "passive"))
      (node (ref "U4") (pin "1") (pinfunction "QB_1") (pintype "output"))
    )
    (net (code "23") (name "/COL_D1_3") (class "Default")
      (node (ref "R27") (pin "2") (pinfunction "2_2") (pintype "passive"))
      (node (ref "U4") (pin "2") (pinfunction "QC_2") (pintype "output"))
    )
    (net (code "24") (name "/COL_D1_4") (class "Default")
      (node (ref "R28") (pin "2") (pinfunction "2_2") (pintype "passive"))
      (node (ref "U4") (pin "3") (pinfunction "QD_3") (pintype "output"))
    )
    (net (code "25") (name "/COL_D1_5") (class "Default")
      (node (ref "R29") (pin "2") (pinfunction "2_2") (pintype "passive"))
      (node (ref "U4") (pin "4") (pinfunction "QE_4") (pintype "output"))
    )
    (net (code "26") (name "/COL_D1_6") (class "Default")
      (node (ref "R30") (pin "2") (pinfunction "2_2") (pintype "passive"))
      (node (ref "U4") (pin "5") (pinfunction "QF_5") (pintype "output"))
    )
    (net (code "27") (name "/COL_D1_7") (class "Default")
      (node (ref "R31") (pin "2") (pinfunction "2_2") (pintype "passive"))
      (node (ref "U4") (pin "6") (pinfunction "QG_6") (pintype "output"))
    )
    (net (code "28") (name "/COL_D1_8") (class "Default")
      (node (ref "R32") (pin "2") (pinfunction "2_2") (pintype "passive"))
      (node (ref "U4") (pin "7") (pinfunction "QH_7") (pintype "output"))
    )
    (net (code "29") (name "/COL_D2_1") (class "Default")
      (node (ref "R33") (pin "2") (pinfunction "2_2") (pintype "passive"))
      (node (ref "U7") (pin "15") (pinfunction "QA_15") (pintype "output"))
    )
    (net (code "30") (name "/COL_D2_2") (class "Default")
      (node (ref "R34") (pin "2") (pinfunction "2_2") (pintype "passive"))
      (node (ref "U7") (pin "1") (pinfunction "QB_1") (pintype "output"))
    )
    (net (code "31") (name "/COL_D2_3") (class "Default")
      (node (ref "R35") (pin "2") (pinfunction "2_2") (pintype "passive"))
      (node (ref "U7") (pin "2") (pinfunction "QC_2") (pintype "output"))
    )
    (net (code "32") (name "/COL_D2_4") (class "Default")
      (node (ref "R36") (pin "2") (pinfunction "2_2") (pintype "passive"))
      (node (ref "U7") (pin "3") (pinfunction "QD_3") (pintype "output"))
    )
    (net (code "33") (name "/COL_D2_5") (class "Default")
      (node (ref "R37") (pin "2") (pinfunction "2_2") (pintype "passive"))
      (node (ref "U7") (pin "4") (pinfunction "QE_4") (pintype "output"))
    )
    (net (code "34") (name "/COL_D2_6") (class "Default")
      (node (ref "R38") (pin "2") (pinfunction "2_2") (pintype "passive"))
      (node (ref "U7") (pin "5") (pinfunction "QF_5") (pintype "output"))
    )
    (net (code "35") (name "/COL_D2_7") (class "Default")
      (node (ref "R39") (pin "2") (pinfunction "2_2") (pintype "passive"))
      (node (ref "U7") (pin "6") (pinfunction "QG_6") (pintype "output"))
    )
    (net (code "36") (name "/COL_D2_8") (class "Default")
      (node (ref "R40") (pin "2") (pinfunction "2_2") (pintype "passive"))
      (node (ref "U7") (pin "7") (pinfunction "QH_7") (pintype "output"))
    )
    (net (code "37") (name "/COL_D3_1") (class "Default")
      (node (ref "R49") (pin "2") (pinfunction "2_2") (pintype "passive"))
      (node (ref "U13") (pin "15") (pinfunction "QA_15") (pintype "output"))
    )
    (net (code "38") (name "/COL_D3_2") (class "Default")
      (node (ref "R50") (pin "2") (pinfunction "2_2") (pintype "passive"))
      (node (ref "U13") (pin "1") (pinfunction "QB_1") (pintype "output"))
    )
    (net (code "39") (name "/COL_D3_3") (class "Default")
      (node (ref "R51") (pin "2") (pinfunction "2_2") (pintype "passive"))
      (node (ref "U13") (pin "2") (pinfunction "QC_2") (pintype "output"))
    )
    (net (code "40") (name "/COL_D3_4") (class "Default")
      (node (ref "R52") (pin "2") (pinfunction "2_2") (pintype "passive"))
      (node (ref "U13") (pin "3") (pinfunction "QD_3") (pintype "output"))
    )
    (net (code "41") (name "/COL_D3_5") (class "Default")
      (node (ref "R53") (pin "2") (pinfunction "2_2") (pintype "passive"))
      (node (ref "U13") (pin "4") (pinfunction "QE_4") (pintype "output"))
    )
    (net (code "42") (name "/COL_D3_6") (class "Default")
      (node (ref "R54") (pin "2") (pinfunction "2_2") (pintype "passive"))
      (node (ref "U13") (pin "5") (pinfunction "QF_5") (pintype "output"))
    )
    (net (code "43") (name "/COL_D3_7") (class "Default")
      (node (ref "R55") (pin "2") (pinfunction "2_2") (pintype "passive"))
      (node (ref "U13") (pin "6") (pinfunction "QG_6") (pintype "output"))
    )
    (net (code "44") (name "/COL_D3_8") (class "Default")
      (node (ref "R56") (pin "2") (pinfunction "2_2") (pintype "passive"))
      (node (ref "U13") (pin "7") (pinfunction "QH_7") (pintype "output"))
    )
    (net (code "45") (name "/COL_D4_1") (class "Default")
      (node (ref "R41") (pin "2") (pinfunction "2_2") (pintype "passive"))
      (node (ref "U17") (pin "15") (pinfunction "QA_15") (pintype "output"))
    )
    (net (code "46") (name "/COL_D4_2") (class "Default")
      (node (ref "R42") (pin "2") (pinfunction "2_2") (pintype "passive"))
      (node (ref "U17") (pin "1") (pinfunction "QB_1") (pintype "output"))
    )
    (net (code "47") (name "/COL_D4_3") (class "Default")
      (node (ref "R43") (pin "2") (pinfunction "2_2") (pintype "passive"))
      (node (ref "U17") (pin "2") (pinfunction "QC_2") (pintype "output"))
    )
    (net (code "48") (name "/COL_D4_4") (class "Default")
      (node (ref "R44") (pin "2") (pinfunction "2_2") (pintype "passive"))
      (node (ref "U17") (pin "3") (pinfunction "QD_3") (pintype "output"))
    )
    (net (code "49") (name "/COL_D4_5") (class "Default")
      (node (ref "R45") (pin "2") (pinfunction "2_2") (pintype "passive"))
      (node (ref "U17") (pin "4") (pinfunction "QE_4") (pintype "output"))
    )
    (net (code "50") (name "/COL_D4_6") (class "Default")
      (node (ref "R46") (pin "2") (pinfunction "2_2") (pintype "passive"))
      (node (ref "U17") (pin "5") (pinfunction "QF_5") (pintype "output"))
    )
    (net (code "51") (name "/COL_D4_7") (class "Default")
      (node (ref "R47") (pin "2") (pinfunction "2_2") (pintype "passive"))
      (node (ref "U17") (pin "6") (pinfunction "QG_6") (pintype "output"))
    )
    (net (code "52") (name "/COL_D4_8") (class "Default")
      (node (ref "R48") (pin "2") (pinfunction "2_2") (pintype "passive"))
      (node (ref "U17") (pin "7") (pinfunction "QH_7") (pintype "output"))
    )
    (net (code "53") (name "/COL_D5_1") (class "Default")
      (node (ref "R105") (pin "2") (pinfunction "2_2") (pintype "passive"))
      (node (ref "U20") (pin "15") (pinfunction "QA_15") (pintype "output"))
    )
    (net (code "54") (name "/COL_D5_2") (class "Default")
      (node (ref "R106") (pin "2") (pinfunction "2_2") (pintype "passive"))
      (node (ref "U20") (pin "1") (pinfunction "QB_1") (pintype "output"))
    )
    (net (code "55") (name "/COL_D5_3") (class "Default")
      (node (ref "R107") (pin "2") (pinfunction "2_2") (pintype "passive"))
      (node (ref "U20") (pin "2") (pinfunction "QC_2") (pintype "output"))
    )
    (net (code "56") (name "/COL_D5_4") (class "Default")
      (node (ref "R108") (pin "2") (pinfunction "2_2") (pintype "passive"))
      (node (ref "U20") (pin "3") (pinfunction "QD_3") (pintype "output"))
    )
    (net (code "57") (name "/COL_D5_5") (class "Default")
      (node (ref "R109") (pin "2") (pinfunction "2_2") (pintype "passive"))
      (node (ref "U20") (pin "4") (pinfunction "QE_4") (pintype "output"))
    )
    (net (code "58") (name "/COL_D5_6") (class "Default")
      (node (ref "R110") (pin "2") (pinfunction "2_2") (pintype "passive"))
      (node (ref "U20") (pin "5") (pinfunction "QF_5") (pintype "output"))
    )
    (net (code "59") (name "/COL_D5_7") (class "Default")
      (node (ref "R111") (pin "2") (pinfunction "2_2") (pintype "passive"))
      (node (ref "U20") (pin "6") (pinfunction "QG_6") (pintype "output"))
    )
    (net (code "60") (name "/COL_D5_8") (class "Default")
      (node (ref "R112") (pin "2") (pinfunction "2_2") (pintype "passive"))
      (node (ref "U20") (pin "7") (pinfunction "QH_7") (pintype "output"))
    )
    (net (code "61") (name "/COL_D6_1") (class "Default")
      (node (ref "R113") (pin "2") (pinfunction "2_2") (pintype "passive"))
      (node (ref "U23") (pin "15") (pinfunction "QA_15") (pintype "output"))
    )
    (net (code "62") (name "/COL_D6_2") (class "Default")
      (node (ref "R114") (pin "2") (pinfunction "2_2") (pintype "passive"))
      (node (ref "U23") (pin "1") (pinfunction "QB_1") (pintype "output"))
    )
    (net (code "63") (name "/COL_D6_3") (class "Default")
      (node (ref "R115") (pin "2") (pinfunction "2_2") (pintype "passive"))
      (node (ref "U23") (pin "2") (pinfunction "QC_2") (pintype "output"))
    )
    (net (code "64") (name "/COL_D6_4") (class "Default")
      (node (ref "R116") (pin "2") (pinfunction "2_2") (pintype "passive"))
      (node (ref "U23") (pin "3") (pinfunction "QD_3") (pintype "output"))
    )
    (net (code "65") (name "/COL_D6_5") (class "Default")
      (node (ref "R117") (pin "2") (pinfunction "2_2") (pintype "passive"))
      (node (ref "U23") (pin "4") (pinfunction "QE_4") (pintype "output"))
    )
    (net (code "66") (name "/COL_D6_6") (class "Default")
      (node (ref "R118") (pin "2") (pinfunction "2_2") (pintype "passive"))
      (node (ref "U23") (pin "5") (pinfunction "QF_5") (pintype "output"))
    )
    (net (code "67") (name "/COL_D6_7") (class "Default")
      (node (ref "R119") (pin "2") (pinfunction "2_2") (pintype "passive"))
      (node (ref "U23") (pin "6") (pinfunction "QG_6") (pintype "output"))
    )
    (net (code "68") (name "/COL_D6_8") (class "Default")
      (node (ref "R120") (pin "2") (pinfunction "2_2") (pintype "passive"))
      (node (ref "U23") (pin "7") (pinfunction "QH_7") (pintype "output"))
    )
    (net (code "69") (name "/COL_D7_1") (class "Default")
      (node (ref "R89") (pin "2") (pinfunction "2_2") (pintype "passive"))
      (node (ref "U27") (pin "15") (pinfunction "QA_15") (pintype "output"))
    )
    (net (code "70") (name "/COL_D7_2") (class "Default")
      (node (ref "R90") (pin "2") (pinfunction "2_2") (pintype "passive"))
      (node (ref "U27") (pin "1") (pinfunction "QB_1") (pintype "output"))
    )
    (net (code "71") (name "/COL_D7_3") (class "Default")
      (node (ref "R91") (pin "2") (pinfunction "2_2") (pintype "passive"))
      (node (ref "U27") (pin "2") (pinfunction "QC_2") (pintype "output"))
    )
    (net (code "72") (name "/COL_D7_4") (class "Default")
      (node (ref "R92") (pin "2") (pinfunction "2_2") (pintype "passive"))
      (node (ref "U27") (pin "3") (pinfunction "QD_3") (pintype "output"))
    )
    (net (code "73") (name "/COL_D7_5") (class "Default")
      (node (ref "R93") (pin "2") (pinfunction "2_2") (pintype "passive"))
      (node (ref "U27") (pin "4") (pinfunction "QE_4") (pintype "output"))
    )
    (net (code "74") (name "/COL_D7_6") (class "Default")
      (node (ref "R94") (pin "2") (pinfunction "2_2") (pintype "passive"))
      (node (ref "U27") (pin "5") (pinfunction "QF_5") (pintype "output"))
    )
    (net (code "75") (name "/COL_D7_7") (class "Default")
      (node (ref "R95") (pin "2") (pinfunction "2_2") (pintype "passive"))
      (node (ref "U27") (pin "6") (pinfunction "QG_6") (pintype "output"))
    )
    (net (code "76") (name "/COL_D7_8") (class "Default")
      (node (ref "R96") (pin "2") (pinfunction "2_2") (pintype "passive"))
      (node (ref "U27") (pin "7") (pinfunction "QH_7") (pintype "output"))
    )
    (net (code "77") (name "/COL_D8_1") (class "Default")
      (node (ref "R97") (pin "2") (pinfunction "2_2") (pintype "passive"))
      (node (ref "U30") (pin "15") (pinfunction "QA_15") (pintype "output"))
    )
    (net (code "78") (name "/COL_D8_2") (class "Default")
      (node (ref "R98") (pin "2") (pinfunction "2_2") (pintype "passive"))
      (node (ref "U30") (pin "1") (pinfunction "QB_1") (pintype "output"))
    )
    (net (code "79") (name "/COL_D8_3") (class "Default")
      (node (ref "R99") (pin "2") (pinfunction "2_2") (pintype "passive"))
      (node (ref "U30") (pin "2") (pinfunction "QC_2") (pintype "output"))
    )
    (net (code "80") (name "/COL_D8_4") (class "Default")
      (node (ref "R100") (pin "2") (pinfunction "2_2") (pintype "passive"))
      (node (ref "U30") (pin "3") (pinfunction "QD_3") (pintype "output"))
    )
    (net (code "81") (name "/COL_D8_5") (class "Default")
      (node (ref "R101") (pin "2") (pinfunction "2_2") (pintype "passive"))
      (node (ref "U30") (pin "4") (pinfunction "QE_4") (pintype "output"))
    )
    (net (code "82") (name "/COL_D8_6") (class "Default")
      (node (ref "R102") (pin "2") (pinfunction "2_2") (pintype "passive"))
      (node (ref "U30") (pin "5") (pinfunction "QF_5") (pintype "output"))
    )
    (net (code "83") (name "/COL_D8_7") (class "Default")
      (node (ref "R103") (pin "2") (pinfunction "2_2") (pintype "passive"))
      (node (ref "U30") (pin "6") (pinfunction "QG_6") (pintype "output"))
    )
    (net (code "84") (name "/COL_D8_8") (class "Default")
      (node (ref "R104") (pin "2") (pinfunction "2_2") (pintype "passive"))
      (node (ref "U30") (pin "7") (pinfunction "QH_7") (pintype "output"))
    )
    (net (code "85") (name "/COL_X1_1") (class "Default")
      (node (ref "R57") (pin "1") (pinfunction "1_1") (pintype "passive"))
      (node (ref "U5") (pin "15") (pinfunction "QA_15") (pintype "output"))
    )
    (net (code "86") (name "/COL_X1_2") (class "Default")
      (node (ref "R58") (pin "1") (pinfunction "1_1") (pintype "passive"))
      (node (ref "U5") (pin "1") (pinfunction "QB_1") (pintype "output"))
    )
    (net (code "87") (name "/COL_X1_3") (class "Default")
      (node (ref "R59") (pin "1") (pinfunction "1_1") (pintype "passive"))
      (node (ref "U5") (pin "2") (pinfunction "QC_2") (pintype "output"))
    )
    (net (code "88") (name "/COL_X1_4") (class "Default")
      (node (ref "R60") (pin "1") (pinfunction "1_1") (pintype "passive"))
      (node (ref "U5") (pin "3") (pinfunction "QD_3") (pintype "output"))
    )
    (net (code "89") (name "/COL_X1_5") (class "Default")
      (node (ref "R61") (pin "1") (pinfunction "1_1") (pintype "passive"))
      (node (ref "U5") (pin "4") (pinfunction "QE_4") (pintype "output"))
    )
    (net (code "90") (name "/COL_X1_6") (class "Default")
      (node (ref "R62") (pin "1") (pinfunction "1_1") (pintype "passive"))
      (node (ref "U5") (pin "5") (pinfunction "QF_5") (pintype "output"))
    )
    (net (code "91") (name "/COL_X1_7") (class "Default")
      (node (ref "R63") (pin "1") (pinfunction "1_1") (pintype "passive"))
      (node (ref "U5") (pin "6") (pinfunction "QG_6") (pintype "output"))
    )
    (net (code "92") (name "/COL_X1_8") (class "Default")
      (node (ref "R64") (pin "1") (pinfunction "1_1") (pintype "passive"))
      (node (ref "U5") (pin "7") (pinfunction "QH_7") (pintype "output"))
    )
    (net (code "93") (name "/COL_X2_1") (class "Default")
      (node (ref "R65") (pin "1") (pinfunction "1_1") (pintype "passive"))
      (node (ref "U8") (pin "15") (pinfunction "QA_15") (pintype "output"))
    )
    (net (code "94") (name "/COL_X2_2") (class "Default")
      (node (ref "R66") (pin "1") (pinfunction "1_1") (pintype "passive"))
      (node (ref "U8") (pin "1") (pinfunction "QB_1") (pintype "output"))
    )
    (net (code "95") (name "/COL_X2_3") (class "Default")
      (node (ref "R67") (pin "1") (pinfunction "1_1") (pintype "passive"))
      (node (ref "U8") (pin "2") (pinfunction "QC_2") (pintype "output"))
    )
    (net (code "96") (name "/COL_X2_4") (class "Default")
      (node (ref "R68") (pin "1") (pinfunction "1_1") (pintype "passive"))
      (node (ref "U8") (pin "3") (pinfunction "QD_3") (pintype "output"))
    )
    (net (code "97") (name "/COL_X2_5") (class "Default")
      (node (ref "R69") (pin "1") (pinfunction "1_1") (pintype "passive"))
      (node (ref "U8") (pin "4") (pinfunction "QE_4") (pintype "output"))
    )
    (net (code "98") (name "/COL_X2_6") (class "Default")
      (node (ref "R70") (pin "1") (pinfunction "1_1") (pintype "passive"))
      (node (ref "U8") (pin "5") (pinfunction "QF_5") (pintype "output"))
    )
    (net (code "99") (name "/COL_X2_7") (class "Default")
      (node (ref "R71") (pin "1") (pinfunction "1_1") (pintype "passive"))
      (node (ref "U8") (pin "6") (pinfunction "QG_6") (pintype "output"))
    )
    (net (code "100") (name "/COL_X2_8") (class "Default")
      (node (ref "R72") (pin "1") (pinfunction "1_1") (pintype "passive"))
      (node (ref "U8") (pin "7") (pinfunction "QH_7") (pintype "output"))
    )
    (net (code "101") (name "/COL_X3_1") (class "Default")
      (node (ref "R81") (pin "1") (pinfunction "1_1") (pintype "passive"))
      (node (ref "U14") (pin "15") (pinfunction "QA_15") (pintype "output"))
    )
    (net (code "102") (name "/COL_X3_2") (class "Default")
      (node (ref "R82") (pin "1") (pinfunction "1_1") (pintype "passive"))
      (node (ref "U14") (pin "1") (pinfunction "QB_1") (pintype "output"))
    )
    (net (code "103") (name "/COL_X3_3") (class "Default")
      (node (ref "R83") (pin "1") (pinfunction "1_1") (pintype "passive"))
      (node (ref "U14") (pin "2") (pinfunction "QC_2") (pintype "output"))
    )
    (net (code "104") (name "/COL_X3_4") (class "Default")
      (node (ref "R84") (pin "1") (pinfunction "1_1") (pintype "passive"))
      (node (ref "U14") (pin "3") (pinfunction "QD_3") (pintype "output"))
    )
    (net (code "105") (name "/COL_X3_5") (class "Default")
      (node (ref "R85") (pin "1") (pinfunction "1_1") (pintype "passive"))
      (node (ref "U14") (pin "4") (pinfunction "QE_4") (pintype "output"))
    )
    (net (code "106") (name "/COL_X3_6") (class "Default")
      (node (ref "R86") (pin "1") (pinfunction "1_1") (pintype "passive"))
      (node (ref "U14") (pin "5") (pinfunction "QF_5") (pintype "output"))
    )
    (net (code "107") (name "/COL_X3_7") (class "Default")
      (node (ref "R87") (pin "1") (pinfunction "1_1") (pintype "passive"))
      (node (ref "U14") (pin "6") (pinfunction "QG_6") (pintype "output"))
    )
    (net (code "108") (name "/COL_X3_8") (class "Default")
      (node (ref "R88") (pin "1") (pinfunction "1_1") (pintype "passive"))
      (node (ref "U14") (pin "7") (pinfunction "QH_7") (pintype "output"))
    )
    (net (code "109") (name "/COL_X4_1") (class "Default")
      (node (ref "R73") (pin "1") (pinfunction "1_1") (pintype "passive"))
      (node (ref "U18") (pin "15") (pinfunction "QA_15") (pintype "output"))
    )
    (net (code "110") (name "/COL_X4_2") (class "Default")
      (node (ref "R74") (pin "1") (pinfunction "1_1") (pintype "passive"))
      (node (ref "U18") (pin "1") (pinfunction "QB_1") (pintype "output"))
    )
    (net (code "111") (name "/COL_X4_3") (class "Default")
      (node (ref "R75") (pin "1") (pinfunction "1_1") (pintype "passive"))
      (node (ref "U18") (pin "2") (pinfunction "QC_2") (pintype "output"))
    )
    (net (code "112") (name "/COL_X4_4") (class "Default")
      (node (ref "R76") (pin "1") (pinfunction "1_1") (pintype "passive"))
      (node (ref "U18") (pin "3") (pinfunction "QD_3") (pintype "output"))
    )
    (net (code "113") (name "/COL_X4_5") (class "Default")
      (node (ref "R77") (pin "1") (pinfunction "1_1") (pintype "passive"))
      (node (ref "U18") (pin "4") (pinfunction "QE_4") (pintype "output"))
    )
    (net (code "114") (name "/COL_X4_6") (class "Default")
      (node (ref "R78") (pin "1") (pinfunction "1_1") (pintype "passive"))
      (node (ref "U18") (pin "5") (pinfunction "QF_5") (pintype "output"))
    )
    (net (code "115") (name "/COL_X4_7") (class "Default")
      (node (ref "R79") (pin "1") (pinfunction "1_1") (pintype "passive"))
      (node (ref "U18") (pin "6") (pinfunction "QG_6") (pintype "output"))
    )
    (net (code "116") (name "/COL_X4_8") (class "Default")
      (node (ref "R80") (pin "1") (pinfunction "1_1") (pintype "passive"))
      (node (ref "U18") (pin "7") (pinfunction "QH_7") (pintype "output"))
    )
    (net (code "117") (name "/COL_X5_1") (class "Default")
      (node (ref "R138") (pin "1") (pinfunction "1_1") (pintype "passive"))
      (node (ref "U21") (pin "15") (pinfunction "QA_15") (pintype "output"))
    )
    (net (code "118") (name "/COL_X5_2") (class "Default")
      (node (ref "R139") (pin "1") (pinfunction "1_1") (pintype "passive"))
      (node (ref "U21") (pin "1") (pinfunction "QB_1") (pintype "output"))
    )
    (net (code "119") (name "/COL_X5_3") (class "Default")
      (node (ref "R140") (pin "1") (pinfunction "1_1") (pintype "passive"))
      (node (ref "U21") (pin "2") (pinfunction "QC_2") (pintype "output"))
    )
    (net (code "120") (name "/COL_X5_4") (class "Default")
      (node (ref "R141") (pin "1") (pinfunction "1_1") (pintype "passive"))
      (node (ref "U21") (pin "3") (pinfunction "QD_3") (pintype "output"))
    )
    (net (code "121") (name "/COL_X5_5") (class "Default")
      (node (ref "R142") (pin "1") (pinfunction "1_1") (pintype "passive"))
      (node (ref "U21") (pin "4") (pinfunction "QE_4") (pintype "output"))
    )
    (net (code "122") (name "/COL_X5_6") (class "Default")
      (node (ref "R143") (pin "1") (pinfunction "1_1") (pintype "passive"))
      (node (ref "U21") (pin "5") (pinfunction "QF_5") (pintype "output"))
    )
    (net (code "123") (name "/COL_X5_7") (class "Default")
      (node (ref "R144") (pin "1") (pinfunction "1_1") (pintype "passive"))
      (node (ref "U21") (pin "6") (pinfunction "QG_6") (pintype "output"))
    )
    (net (code "124") (name "/COL_X5_8") (class "Default")
      (node (ref "R145") (pin "1") (pinfunction "1_1") (pintype "passive"))
      (node (ref "U21") (pin "7") (pinfunction "QH_7") (pintype "output"))
    )
    (net (code "125") (name "/COL_X6_1") (class "Default")
      (node (ref "R146") (pin "1") (pinfunction "1_1") (pintype "passive"))
      (node (ref "U24") (pin "15") (pinfunction "QA_15") (pintype "output"))
    )
    (net (code "126") (name "/COL_X6_2") (class "Default")
      (node (ref "R147") (pin "1") (pinfunction "1_1") (pintype "passive"))
      (node (ref "U24") (pin "1") (pinfunction "QB_1") (pintype "output"))
    )
    (net (code "127") (name "/COL_X6_3") (class "Default")
      (node (ref "R148") (pin "1") (pinfunction "1_1") (pintype "passive"))
      (node (ref "U24") (pin "2") (pinfunction "QC_2") (pintype "output"))
    )
    (net (code "128") (name "/COL_X6_4") (class "Default")
      (node (ref "R149") (pin "1") (pinfunction "1_1") (pintype "passive"))
      (node (ref "U24") (pin "3") (pinfunction "QD_3") (pintype "output"))
    )
    (net (code "129") (name "/COL_X6_5") (class "Default")
      (node (ref "R150") (pin "1") (pinfunction "1_1") (pintype "passive"))
      (node (ref "U24") (pin "4") (pinfunction "QE_4") (pintype "output"))
    )
    (net (code "130") (name "/COL_X6_6") (class "Default")
      (node (ref "R151") (pin "1") (pinfunction "1_1") (pintype "passive"))
      (node (ref "U24") (pin "5") (pinfunction "QF_5") (pintype "output"))
    )
    (net (code "131") (name "/COL_X6_7") (class "Default")
      (node (ref "R152") (pin "1") (pinfunction "1_1") (pintype "passive"))
      (node (ref "U24") (pin "6") (pinfunction "QG_6") (pintype "output"))
    )
    (net (code "132") (name "/COL_X6_8") (class "Default")
      (node (ref "R153") (pin "1") (pinfunction "1_1") (pintype "passive"))
      (node (ref "U24") (pin "7") (pinfunction "QH_7") (pintype "output"))
    )
    (net (code "133") (name "/COL_X7_1") (class "Default")
      (node (ref "R122") (pin "1") (pinfunction "1_1") (pintype "passive"))
      (node (ref "U28") (pin "15") (pinfunction "QA_15") (pintype "output"))
    )
    (net (code "134") (name "/COL_X7_2") (class "Default")
      (node (ref "R123") (pin "1") (pinfunction "1_1") (pintype "passive"))
      (node (ref "U28") (pin "1") (pinfunction "QB_1") (pintype "output"))
    )
    (net (code "135") (name "/COL_X7_3") (class "Default")
      (node (ref "R124") (pin "1") (pinfunction "1_1") (pintype "passive"))
      (node (ref "U28") (pin "2") (pinfunction "QC_2") (pintype "output"))
    )
    (net (code "136") (name "/COL_X7_4") (class "Default")
      (node (ref "R125") (pin "1") (pinfunction "1_1") (pintype "passive"))
      (node (ref "U28") (pin "3") (pinfunction "QD_3") (pintype "output"))
    )
    (net (code "137") (name "/COL_X7_5") (class "Default")
      (node (ref "R126") (pin "1") (pinfunction "1_1") (pintype "passive"))
      (node (ref "U28") (pin "4") (pinfunction "QE_4") (pintype "output"))
    )
    (net (code "138") (name "/COL_X7_6") (class "Default")
      (node (ref "R127") (pin "1") (pinfunction "1_1") (pintype "passive"))
      (node (ref "U28") (pin "5") (pinfunction "QF_5") (pintype "output"))
    )
    (net (code "139") (name "/COL_X7_7") (class "Default")
      (node (ref "R128") (pin "1") (pinfunction "1_1") (pintype "passive"))
      (node (ref "U28") (pin "6") (pinfunction "QG_6") (pintype "output"))
    )
    (net (code "140") (name "/COL_X7_8") (class "Default")
      (node (ref "R129") (pin "1") (pinfunction "1_1") (pintype "passive"))
      (node (ref "U28") (pin "7") (pinfunction "QH_7") (pintype "output"))
    )
    (net (code "141") (name "/COL_X8_1") (class "Default")
      (node (ref "R130") (pin "1") (pinfunction "1_1") (pintype "passive"))
      (node (ref "U31") (pin "15") (pinfunction "QA_15") (pintype "output"))
    )
    (net (code "142") (name "/COL_X8_2") (class "Default")
      (node (ref "R131") (pin "1") (pinfunction "1_1") (pintype "passive"))
      (node (ref "U31") (pin "1") (pinfunction "QB_1") (pintype "output"))
    )
    (net (code "143") (name "/COL_X8_3") (class "Default")
      (node (ref "R132") (pin "1") (pinfunction "1_1") (pintype "passive"))
      (node (ref "U31") (pin "2") (pinfunction "QC_2") (pintype "output"))
    )
    (net (code "144") (name "/COL_X8_4") (class "Default")
      (node (ref "R133") (pin "1") (pinfunction "1_1") (pintype "passive"))
      (node (ref "U31") (pin "3") (pinfunction "QD_3") (pintype "output"))
    )
    (net (code "145") (name "/COL_X8_5") (class "Default")
      (node (ref "R134") (pin "1") (pinfunction "1_1") (pintype "passive"))
      (node (ref "U31") (pin "4") (pinfunction "QE_4") (pintype "output"))
    )
    (net (code "146") (name "/COL_X8_6") (class "Default")
      (node (ref "R135") (pin "1") (pinfunction "1_1") (pintype "passive"))
      (node (ref "U31") (pin "5") (pinfunction "QF_5") (pintype "output"))
    )
    (net (code "147") (name "/COL_X8_7") (class "Default")
      (node (ref "R136") (pin "1") (pinfunction "1_1") (pintype "passive"))
      (node (ref "U31") (pin "6") (pinfunction "QG_6") (pintype "output"))
    )
    (net (code "148") (name "/COL_X8_8") (class "Default")
      (node (ref "R137") (pin "1") (pinfunction "1_1") (pintype "passive"))
      (node (ref "U31") (pin "7") (pinfunction "QH_7") (pintype "output"))
    )
    (net (code "149") (name "/CS_LLS") (class "Default")
      (node (ref "SD1") (pin "P2") (pinfunction "DAT3_P2") (pintype "passive"))
      (node (ref "U32") (pin "8") (pinfunction "3Y_8") (pintype "output"))
    )
    (net (code "150") (name "/CS_SD") (class "Default")
      (node (ref "R157") (pin "2") (pinfunction "2_2") (pintype "passive"))
      (node (ref "U3") (pin "23") (pinfunction "IO21_23") (pintype "bidirectional"))
    )
    (net (code "151") (name "/D+") (class "Default")
      (node (ref "CN1") (pin "A6") (pinfunction "DP1_A6") (pintype "passive"))
      (node (ref "CN1") (pin "B6") (pinfunction "DP2_B6") (pintype "passive"))
      (node (ref "U34") (pin "5") (pinfunction "UD+_5") (pintype "bidirectional"))
    )
    (net (code "152") (name "/D-") (class "Default")
      (node (ref "CN1") (pin "A7") (pinfunction "DN1_A7") (pintype "passive"))
      (node (ref "CN1") (pin "B7") (pinfunction "DN2_B7") (pintype "passive"))
      (node (ref "U34") (pin "6") (pinfunction "UD-_6") (pintype "bidirectional"))
    )
    (net (code "153") (name "/DATA_MATRIX") (class "Default")
      (node (ref "U1") (pin "23") (pinfunction "IO21_23") (pintype "bidirectional"))
      (node (ref "U2") (pin "14") (pinfunction "DATA_IN_14") (pintype "input"))
    )
    (net (code "154") (name "/DIN_AUDIO") (class "Default")
      (node (ref "U25") (pin "14") (pinfunction "DIN_14") (pintype "input"))
      (node (ref "U3") (pin "5") (pinfunction "IO5_5") (pintype "bidirectional"))
    )
    (net (code "155") (name "/DI_LLS") (class "Default")
      (node (ref "SD1") (pin "P3") (pinfunction "CMD_DIN_P3") (pintype "passive"))
      (node (ref "U32") (pin "3") (pinfunction "1Y_3") (pintype "output"))
    )
    (net (code "156") (name "/DO_LLS") (class "Default")
      (node (ref "R155") (pin "2") (pinfunction "2_2") (pintype "passive"))
      (node (ref "SD1") (pin "P7") (pinfunction "DAT0-DO_P7") (pintype "passive"))
    )
    (net (code "157") (name "/FLT") (class "Default")
      (node (ref "R162") (pin "2") (pinfunction "2_2") (pintype "passive"))
      (node (ref "U25") (pin "11") (pinfunction "FLT_11") (pintype "input"))
    )
    (net (code "158") (name "/INL") (class "Default")
      (node (ref "C28") (pin "2") (pinfunction "2_2") (pintype "passive"))
      (node (ref "R121") (pin "2") (pinfunction "2_2") (pintype "passive"))
      (node (ref "U25") (pin "6") (pinfunction "OUTL_6") (pintype "output"))
    )
    (net (code "159") (name "/INR") (class "Default")
      (node (ref "C29") (pin "2") (pinfunction "2_2") (pintype "passive"))
      (node (ref "R160") (pin "2") (pinfunction "2_2") (pintype "passive"))
      (node (ref "U25") (pin "7") (pinfunction "OUTR_7") (pintype "output"))
    )
    (net (code "160") (name "/IO2-2") (class "Default")
      (node (ref "J5") (pin "2") (pinfunction "2_2") (pintype "passive"))
      (node (ref "U3") (pin "38") (pinfunction "IO2_38") (pintype "bidirectional"))
    )
    (net (code "161") (name "/IO3-2") (class "Default")
      (node (ref "J5") (pin "5") (pinfunction "5_5") (pintype "passive"))
      (node (ref "U3") (pin "15") (pinfunction "IO3_15") (pintype "bidirectional"))
    )
    (net (code "162") (name "/IO8-2") (class "Default")
      (node (ref "J5") (pin "4") (pinfunction "4_4") (pintype "passive"))
      (node (ref "U3") (pin "12") (pinfunction "IO8_12") (pintype "bidirectional"))
    )
    (net (code "163") (name "/IO16-2") (class "Default")
      (node (ref "J5") (pin "3") (pinfunction "3_3") (pintype "passive"))
      (node (ref "U3") (pin "9") (pinfunction "IO16_9") (pintype "bidirectional"))
    )
    (net (code "164") (name "/LATCH") (class "Default")
      (node (ref "U1") (pin "24") (pinfunction "IO47_24") (pintype "bidirectional"))
      (node (ref "U12") (pin "12") (pinfunction "LATCH_12") (pintype "input"))
      (node (ref "U13") (pin "12") (pinfunction "LATCH_12") (pintype "input"))
      (node (ref "U14") (pin "12") (pinfunction "LATCH_12") (pintype "input"))
      (node (ref "U16") (pin "12") (pinfunction "LATCH_12") (pintype "input"))
      (node (ref "U17") (pin "12") (pinfunction "LATCH_12") (pintype "input"))
      (node (ref "U18") (pin "12") (pinfunction "LATCH_12") (pintype "input"))
      (node (ref "U19") (pin "12") (pinfunction "LATCH_12") (pintype "input"))
      (node (ref "U2") (pin "12") (pinfunction "LATCH_12") (pintype "input"))
      (node (ref "U20") (pin "12") (pinfunction "LATCH_12") (pintype "input"))
      (node (ref "U21") (pin "12") (pinfunction "LATCH_12") (pintype "input"))
      (node (ref "U22") (pin "12") (pinfunction "LATCH_12") (pintype "input"))
      (node (ref "U23") (pin "12") (pinfunction "LATCH_12") (pintype "input"))
      (node (ref "U24") (pin "12") (pinfunction "LATCH_12") (pintype "input"))
      (node (ref "U26") (pin "12") (pinfunction "LATCH_12") (pintype "input"))
      (node (ref "U27") (pin "12") (pinfunction "LATCH_12") (pintype "input"))
      (node (ref "U28") (pin "12") (pinfunction "LATCH_12") (pintype "input"))
      (node (ref "U29") (pin "12") (pinfunction "LATCH_12") (pintype "input"))
      (node (ref "U30") (pin "12") (pinfunction "LATCH_12") (pintype "input"))
      (node (ref "U31") (pin "12") (pinfunction "LATCH_12") (pintype "input"))
      (node (ref "U4") (pin "12") (pinfunction "LATCH_12") (pintype "input"))
      (node (ref "U5") (pin "12") (pinfunction "LATCH_12") (pintype "input"))
      (node (ref "U6") (pin "12") (pinfunction "LATCH_12") (pintype "input"))
      (node (ref "U7") (pin "12") (pinfunction "LATCH_12") (pintype "input"))
      (node (ref "U8") (pin "12") (pinfunction "LATCH_12") (pintype "input"))
    )
    (net (code "165") (name "/LRCLK_AUDIO") (class "Default")
      (node (ref "U25") (pin "15") (pinfunction "LRCK_15") (pintype "input"))
      (node (ref "U3") (pin "4") (pinfunction "IO4_4") (pintype "bidirectional"))
    )
    (net (code "166") (name "/LR_MIC") (class "Default")
      (node (ref "MIC1") (pin "4") (pinfunction "LR_4") (pintype "passive"))
      (node (ref "U3") (pin "18") (pinfunction "IO10_18") (pintype "bidirectional"))
    )
    (net (code "167") (name "/MISO_SD") (class "Default")
      (node (ref "U3") (pin "24") (pinfunction "IO47_24") (pintype "bidirectional"))
      (node (ref "U32") (pin "11") (pinfunction "4Y_11") (pintype "output"))
    )
    (net (code "168") (name "/MOSI_SD") (class "Default")
      (node (ref "R154") (pin "1") (pinfunction "1_1") (pintype "passive"))
      (node (ref "U3") (pin "39") (pinfunction "IO1_39") (pintype "bidirectional"))
    )
    (net (code "169") (name "/MUTE_AMPLI") (class "Default")
      (node (ref "U3") (pin "8") (pinfunction "IO15_8") (pintype "bidirectional"))
      (node (ref "U33") (pin "5") (pinfunction "MUTE_5") (pintype "input"))
    )
    (net (code "170") (name "/RESET_ESP32-1") (class "Default")
      (node (ref "BT7") (pin "2") (pintype "passive"))
      (node (ref "R10") (pin "1") (pinfunction "1_1") (pintype "passive"))
      (node (ref "U1") (pin "3") (pinfunction "EN_3") (pintype "input"))
    )
    (net (code "171") (name "/RESET_ESP32-2") (class "Default")
      (node (ref "BT9") (pin "2") (pintype "passive"))
      (node (ref "R9") (pin "1") (pinfunction "1_1") (pintype "passive"))
      (node (ref "U3") (pin "3") (pinfunction "EN_3") (pintype "input"))
    )
    (net (code "172") (name "/ROW1_1") (class "Default")
      (node (ref "Matrix1") (pin "24") (pinfunction "28_24") (pintype "passive"))
      (node (ref "U2") (pin "15") (pinfunction "QA_15") (pintype "output"))
    )
    (net (code "173") (name "/ROW1_2") (class "Default")
      (node (ref "Matrix1") (pin "23") (pinfunction "27_23") (pintype "passive"))
      (node (ref "U2") (pin "1") (pinfunction "QB_1") (pintype "output"))
    )
    (net (code "174") (name "/ROW1_3") (class "Default")
      (node (ref "Matrix1") (pin "22") (pinfunction "26_22") (pintype "passive"))
      (node (ref "U2") (pin "2") (pinfunction "QC_2") (pintype "output"))
    )
    (net (code "175") (name "/ROW1_4") (class "Default")
      (node (ref "Matrix1") (pin "21") (pinfunction "25_21") (pintype "passive"))
      (node (ref "U2") (pin "3") (pinfunction "QD_3") (pintype "output"))
    )
    (net (code "176") (name "/ROW1_5") (class "Default")
      (node (ref "Matrix1") (pin "4") (pinfunction "4_4") (pintype "passive"))
      (node (ref "U2") (pin "4") (pinfunction "QE_4") (pintype "output"))
    )
    (net (code "177") (name "/ROW1_6") (class "Default")
      (node (ref "Matrix1") (pin "3") (pinfunction "3_3") (pintype "passive"))
      (node (ref "U2") (pin "5") (pinfunction "QF_5") (pintype "output"))
    )
    (net (code "178") (name "/ROW1_7") (class "Default")
      (node (ref "Matrix1") (pin "2") (pinfunction "2_2") (pintype "passive"))
      (node (ref "U2") (pin "6") (pinfunction "QG_6") (pintype "output"))
    )
    (net (code "179") (name "/ROW1_8") (class "Default")
      (node (ref "Matrix1") (pin "1") (pinfunction "1_1") (pintype "passive"))
      (node (ref "U2") (pin "7") (pinfunction "QH_7") (pintype "output"))
    )
    (net (code "180") (name "/ROW2_1") (class "Default")
      (node (ref "Matrix2") (pin "24") (pinfunction "28_24") (pintype "passive"))
      (node (ref "U6") (pin "15") (pinfunction "QA_15") (pintype "output"))
    )
    (net (code "181") (name "/ROW2_2") (class "Default")
      (node (ref "Matrix2") (pin "23") (pinfunction "27_23") (pintype "passive"))
      (node (ref "U6") (pin "1") (pinfunction "QB_1") (pintype "output"))
    )
    (net (code "182") (name "/ROW2_3") (class "Default")
      (node (ref "Matrix2") (pin "22") (pinfunction "26_22") (pintype "passive"))
      (node (ref "U6") (pin "2") (pinfunction "QC_2") (pintype "output"))
    )
    (net (code "183") (name "/ROW2_4") (class "Default")
      (node (ref "Matrix2") (pin "21") (pinfunction "25_21") (pintype "passive"))
      (node (ref "U6") (pin "3") (pinfunction "QD_3") (pintype "output"))
    )
    (net (code "184") (name "/ROW2_5") (class "Default")
      (node (ref "Matrix2") (pin "4") (pinfunction "4_4") (pintype "passive"))
      (node (ref "U6") (pin "4") (pinfunction "QE_4") (pintype "output"))
    )
    (net (code "185") (name "/ROW2_6") (class "Default")
      (node (ref "Matrix2") (pin "3") (pinfunction "3_3") (pintype "passive"))
      (node (ref "U6") (pin "5") (pinfunction "QF_5") (pintype "output"))
    )
    (net (code "186") (name "/ROW2_7") (class "Default")
      (node (ref "Matrix2") (pin "2") (pinfunction "2_2") (pintype "passive"))
      (node (ref "U6") (pin "6") (pinfunction "QG_6") (pintype "output"))
    )
    (net (code "187") (name "/ROW2_8") (class "Default")
      (node (ref "Matrix2") (pin "1") (pinfunction "1_1") (pintype "passive"))
      (node (ref "U6") (pin "7") (pinfunction "QH_7") (pintype "output"))
    )
    (net (code "188") (name "/ROW3_1") (class "Default")
      (node (ref "Matrix3") (pin "24") (pinfunction "28_24") (pintype "passive"))
      (node (ref "U12") (pin "15") (pinfunction "QA_15") (pintype "output"))
    )
    (net (code "189") (name "/ROW3_2") (class "Default")
      (node (ref "Matrix3") (pin "23") (pinfunction "27_23") (pintype "passive"))
      (node (ref "U12") (pin "1") (pinfunction "QB_1") (pintype "output"))
    )
    (net (code "190") (name "/ROW3_3") (class "Default")
      (node (ref "Matrix3") (pin "22") (pinfunction "26_22") (pintype "passive"))
      (node (ref "U12") (pin "2") (pinfunction "QC_2") (pintype "output"))
    )
    (net (code "191") (name "/ROW3_4") (class "Default")
      (node (ref "Matrix3") (pin "21") (pinfunction "25_21") (pintype "passive"))
      (node (ref "U12") (pin "3") (pinfunction "QD_3") (pintype "output"))
    )
    (net (code "192") (name "/ROW3_5") (class "Default")
      (node (ref "Matrix3") (pin "4") (pinfunction "4_4") (pintype "passive"))
      (node (ref "U12") (pin "4") (pinfunction "QE_4") (pintype "output"))
    )
    (net (code "193") (name "/ROW3_6") (class "Default")
      (node (ref "Matrix3") (pin "3") (pinfunction "3_3") (pintype "passive"))
      (node (ref "U12") (pin "5") (pinfunction "QF_5") (pintype "output"))
    )
    (net (code "194") (name "/ROW3_7") (class "Default")
      (node (ref "Matrix3") (pin "2") (pinfunction "2_2") (pintype "passive"))
      (node (ref "U12") (pin "6") (pinfunction "QG_6") (pintype "output"))
    )
    (net (code "195") (name "/ROW3_8") (class "Default")
      (node (ref "Matrix3") (pin "1") (pinfunction "1_1") (pintype "passive"))
      (node (ref "U12") (pin "7") (pinfunction "QH_7") (pintype "output"))
    )
    (net (code "196") (name "/ROW4_1") (class "Default")
      (node (ref "Matrix4") (pin "24") (pinfunction "28_24") (pintype "passive"))
      (node (ref "U16") (pin "15") (pinfunction "QA_15") (pintype "output"))
    )
    (net (code "197") (name "/ROW4_2") (class "Default")
      (node (ref "Matrix4") (pin "23") (pinfunction "27_23") (pintype "passive"))
      (node (ref "U16") (pin "1") (pinfunction "QB_1") (pintype "output"))
    )
    (net (code "198") (name "/ROW4_3") (class "Default")
      (node (ref "Matrix4") (pin "22") (pinfunction "26_22") (pintype "passive"))
      (node (ref "U16") (pin "2") (pinfunction "QC_2") (pintype "output"))
    )
    (net (code "199") (name "/ROW4_4") (class "Default")
      (node (ref "Matrix4") (pin "21") (pinfunction "25_21") (pintype "passive"))
      (node (ref "U16") (pin "3") (pinfunction "QD_3") (pintype "output"))
    )
    (net (code "200") (name "/ROW4_5") (class "Default")
      (node (ref "Matrix4") (pin "4") (pinfunction "4_4") (pintype "passive"))
      (node (ref "U16") (pin "4") (pinfunction "QE_4") (pintype "output"))
    )
    (net (code "201") (name "/ROW4_6") (class "Default")
      (node (ref "Matrix4") (pin "3") (pinfunction "3_3") (pintype "passive"))
      (node (ref "U16") (pin "5") (pinfunction "QF_5") (pintype "output"))
    )
    (net (code "202") (name "/ROW4_7") (class "Default")
      (node (ref "Matrix4") (pin "2") (pinfunction "2_2") (pintype "passive"))
      (node (ref "U16") (pin "6") (pinfunction "QG_6") (pintype "output"))
    )
    (net (code "203") (name "/ROW4_8") (class "Default")
      (node (ref "Matrix4") (pin "1") (pinfunction "1_1") (pintype "passive"))
      (node (ref "U16") (pin "7") (pinfunction "QH_7") (pintype "output"))
    )
    (net (code "204") (name "/ROW5_1") (class "Default")
      (node (ref "Matrix5") (pin "24") (pinfunction "28_24") (pintype "passive"))
      (node (ref "U19") (pin "15") (pinfunction "QA_15") (pintype "output"))
    )
    (net (code "205") (name "/ROW5_2") (class "Default")
      (node (ref "Matrix5") (pin "23") (pinfunction "27_23") (pintype "passive"))
      (node (ref "U19") (pin "1") (pinfunction "QB_1") (pintype "output"))
    )
    (net (code "206") (name "/ROW5_3") (class "Default")
      (node (ref "Matrix5") (pin "22") (pinfunction "26_22") (pintype "passive"))
      (node (ref "U19") (pin "2") (pinfunction "QC_2") (pintype "output"))
    )
    (net (code "207") (name "/ROW5_4") (class "Default")
      (node (ref "Matrix5") (pin "21") (pinfunction "25_21") (pintype "passive"))
      (node (ref "U19") (pin "3") (pinfunction "QD_3") (pintype "output"))
    )
    (net (code "208") (name "/ROW5_5") (class "Default")
      (node (ref "Matrix5") (pin "4") (pinfunction "4_4") (pintype "passive"))
      (node (ref "U19") (pin "4") (pinfunction "QE_4") (pintype "output"))
    )
    (net (code "209") (name "/ROW5_6") (class "Default")
      (node (ref "Matrix5") (pin "3") (pinfunction "3_3") (pintype "passive"))
      (node (ref "U19") (pin "5") (pinfunction "QF_5") (pintype "output"))
    )
    (net (code "210") (name "/ROW5_7") (class "Default")
      (node (ref "Matrix5") (pin "2") (pinfunction "2_2") (pintype "passive"))
      (node (ref "U19") (pin "6") (pinfunction "QG_6") (pintype "output"))
    )
    (net (code "211") (name "/ROW5_8") (class "Default")
      (node (ref "Matrix5") (pin "1") (pinfunction "1_1") (pintype "passive"))
      (node (ref "U19") (pin "7") (pinfunction "QH_7") (pintype "output"))
    )
    (net (code "212") (name "/ROW6_1") (class "Default")
      (node (ref "Matrix6") (pin "24") (pinfunction "28_24") (pintype "passive"))
      (node (ref "U22") (pin "15") (pinfunction "QA_15") (pintype "output"))
    )
    (net (code "213") (name "/ROW6_2") (class "Default")
      (node (ref "Matrix6") (pin "23") (pinfunction "27_23") (pintype "passive"))
      (node (ref "U22") (pin "1") (pinfunction "QB_1") (pintype "output"))
    )
    (net (code "214") (name "/ROW6_3") (class "Default")
      (node (ref "Matrix6") (pin "22") (pinfunction "26_22") (pintype "passive"))
      (node (ref "U22") (pin "2") (pinfunction "QC_2") (pintype "output"))
    )
    (net (code "215") (name "/ROW6_4") (class "Default")
      (node (ref "Matrix6") (pin "21") (pinfunction "25_21") (pintype "passive"))
      (node (ref "U22") (pin "3") (pinfunction "QD_3") (pintype "output"))
    )
    (net (code "216") (name "/ROW6_5") (class "Default")
      (node (ref "Matrix6") (pin "4") (pinfunction "4_4") (pintype "passive"))
      (node (ref "U22") (pin "4") (pinfunction "QE_4") (pintype "output"))
    )
    (net (code "217") (name "/ROW6_6") (class "Default")
      (node (ref "Matrix6") (pin "3") (pinfunction "3_3") (pintype "passive"))
      (node (ref "U22") (pin "5") (pinfunction "QF_5") (pintype "output"))
    )
    (net (code "218") (name "/ROW6_7") (class "Default")
      (node (ref "Matrix6") (pin "2") (pinfunction "2_2") (pintype "passive"))
      (node (ref "U22") (pin "6") (pinfunction "QG_6") (pintype "output"))
    )
    (net (code "219") (name "/ROW6_8") (class "Default")
      (node (ref "Matrix6") (pin "1") (pinfunction "1_1") (pintype "passive"))
      (node (ref "U22") (pin "7") (pinfunction "QH_7") (pintype "output"))
    )
    (net (code "220") (name "/ROW7_1") (class "Default")
      (node (ref "Matrix7") (pin "24") (pinfunction "28_24") (pintype "passive"))
      (node (ref "U26") (pin "15") (pinfunction "QA_15") (pintype "output"))
    )
    (net (code "221") (name "/ROW7_2") (class "Default")
      (node (ref "Matrix7") (pin "23") (pinfunction "27_23") (pintype "passive"))
      (node (ref "U26") (pin "1") (pinfunction "QB_1") (pintype "output"))
    )
    (net (code "222") (name "/ROW7_3") (class "Default")
      (node (ref "Matrix7") (pin "22") (pinfunction "26_22") (pintype "passive"))
      (node (ref "U26") (pin "2") (pinfunction "QC_2") (pintype "output"))
    )
    (net (code "223") (name "/ROW7_4") (class "Default")
      (node (ref "Matrix7") (pin "21") (pinfunction "25_21") (pintype "passive"))
      (node (ref "U26") (pin "3") (pinfunction "QD_3") (pintype "output"))
    )
    (net (code "224") (name "/ROW7_5") (class "Default")
      (node (ref "Matrix7") (pin "4") (pinfunction "4_4") (pintype "passive"))
      (node (ref "U26") (pin "4") (pinfunction "QE_4") (pintype "output"))
    )
    (net (code "225") (name "/ROW7_6") (class "Default")
      (node (ref "Matrix7") (pin "3") (pinfunction "3_3") (pintype "passive"))
      (node (ref "U26") (pin "5") (pinfunction "QF_5") (pintype "output"))
    )
    (net (code "226") (name "/ROW7_7") (class "Default")
      (node (ref "Matrix7") (pin "2") (pinfunction "2_2") (pintype "passive"))
      (node (ref "U26") (pin "6") (pinfunction "QG_6") (pintype "output"))
    )
    (net (code "227") (name "/ROW7_8") (class "Default")
      (node (ref "Matrix7") (pin "1") (pinfunction "1_1") (pintype "passive"))
      (node (ref "U26") (pin "7") (pinfunction "QH_7") (pintype "output"))
    )
    (net (code "228") (name "/ROW8_1") (class "Default")
      (node (ref "Matrix8") (pin "24") (pinfunction "28_24") (pintype "passive"))
      (node (ref "U29") (pin "15") (pinfunction "QA_15") (pintype "output"))
    )
    (net (code "229") (name "/ROW8_2") (class "Default")
      (node (ref "Matrix8") (pin "23") (pinfunction "27_23") (pintype "passive"))
      (node (ref "U29") (pin "1") (pinfunction "QB_1") (pintype "output"))
    )
    (net (code "230") (name "/ROW8_3") (class "Default")
      (node (ref "Matrix8") (pin "22") (pinfunction "26_22") (pintype "passive"))
      (node (ref "U29") (pin "2") (pinfunction "QC_2") (pintype "output"))
    )
    (net (code "231") (name "/ROW8_4") (class "Default")
      (node (ref "Matrix8") (pin "21") (pinfunction "25_21") (pintype "passive"))
      (node (ref "U29") (pin "3") (pinfunction "QD_3") (pintype "output"))
    )
    (net (code "232") (name "/ROW8_5") (class "Default")
      (node (ref "Matrix8") (pin "4") (pinfunction "4_4") (pintype "passive"))
      (node (ref "U29") (pin "4") (pinfunction "QE_4") (pintype "output"))
    )
    (net (code "233") (name "/ROW8_6") (class "Default")
      (node (ref "Matrix8") (pin "3") (pinfunction "3_3") (pintype "passive"))
      (node (ref "U29") (pin "5") (pinfunction "QF_5") (pintype "output"))
    )
    (net (code "234") (name "/ROW8_7") (class "Default")
      (node (ref "Matrix8") (pin "2") (pinfunction "2_2") (pintype "passive"))
      (node (ref "U29") (pin "6") (pinfunction "QG_6") (pintype "output"))
    )
    (net (code "235") (name "/ROW8_8") (class "Default")
      (node (ref "Matrix8") (pin "1") (pinfunction "1_1") (pintype "passive"))
      (node (ref "U29") (pin "7") (pinfunction "QH_7") (pintype "output"))
    )
    (net (code "236") (name "/RXD") (class "Default")
      (node (ref "D1") (pin "C") (pinfunction "C_C") (pintype "passive"))
      (node (ref "J2") (pin "3") (pinfunction "3_3") (pintype "passive"))
      (node (ref "U34") (pin "3") (pinfunction "RXD_3") (pintype "input"))
    )
    (net (code "237") (name "/RXD_ESP32-1") (class "Default")
      (node (ref "J7") (pin "2") (pinfunction "2_2") (pintype "passive"))
      (node (ref "U1") (pin "36") (pinfunction "RXD0_36") (pintype "bidirectional"))
    )
    (net (code "238") (name "/RXD_ESP32-2") (class "Default")
      (node (ref "J6") (pin "2") (pinfunction "2_2") (pintype "passive"))
      (node (ref "U3") (pin "36") (pinfunction "RXD0_36") (pintype "bidirectional"))
    )
    (net (code "239") (name "/RXD_S1_ESP32-1") (class "Default")
      (node (ref "CN4") (pin "3") (pinfunction "3_3") (pintype "passive"))
      (node (ref "U1") (pin "11") (pinfunction "IO18_11") (pintype "bidirectional"))
    )
    (net (code "240") (name "/RXD_S1_ESP32-2") (class "Default")
      (node (ref "J8") (pin "2") (pinfunction "2_2") (pintype "passive"))
      (node (ref "U3") (pin "11") (pinfunction "IO18_11") (pintype "bidirectional"))
    )
    (net (code "241") (name "/SCK_LLS") (class "Default")
      (node (ref "SD1") (pin "P5") (pinfunction "CLK_P5") (pintype "passive"))
      (node (ref "U32") (pin "6") (pinfunction "2Y_6") (pintype "output"))
    )
    (net (code "242") (name "/SCK_MIC") (class "Default")
      (node (ref "MIC1") (pin "6") (pinfunction "SCK_6") (pintype "passive"))
      (node (ref "U3") (pin "20") (pinfunction "IO12_20") (pintype "bidirectional"))
    )
    (net (code "243") (name "/SCK_SD") (class "Default")
      (node (ref "R156") (pin "1") (pinfunction "1_1") (pintype "passive"))
      (node (ref "U3") (pin "25") (pinfunction "IO48_25") (pintype "bidirectional"))
    )
    (net (code "244") (name "/SCL") (class "Default")
      (node (ref "CN5") (pin "2") (pinfunction "2_2") (pintype "passive"))
      (node (ref "DP1") (pin "3") (pinfunction "SCK_3") (pintype "input"))
      (node (ref "R19") (pin "2") (pinfunction "2_2") (pintype "passive"))
      (node (ref "U1") (pin "21") (pinfunction "IO13_21") (pintype "bidirectional"))
      (node (ref "U11") (pin "23") (pinfunction "SCL_23") (pintype "input"))
      (node (ref "U3") (pin "21") (pinfunction "IO13_21") (pintype "bidirectional"))
    )
    (net (code "245") (name "/SD") (class "Default")
      (node (ref "R161") (pin "2") (pinfunction "2_2") (pintype "passive"))
      (node (ref "U25") (pin "17") (pinfunction "XSMT_17") (pintype "input"))
    )
    (net (code "246") (name "/SDA") (class "Default")
      (node (ref "CN5") (pin "1") (pinfunction "1_1") (pintype "passive"))
      (node (ref "DP1") (pin "4") (pinfunction "SDA_4") (pintype "bidirectional"))
      (node (ref "R22") (pin "2") (pinfunction "2_2") (pintype "passive"))
      (node (ref "U1") (pin "22") (pinfunction "IO14_22") (pintype "bidirectional"))
      (node (ref "U11") (pin "24") (pinfunction "SDA_24") (pintype "bidirectional"))
      (node (ref "U3") (pin "22") (pinfunction "IO14_22") (pintype "bidirectional"))
    )
    (net (code "247") (name "/SD_MIC") (class "Default")
      (node (ref "MIC1") (pin "1") (pinfunction "SD_1") (pintype "passive"))
      (node (ref "U3") (pin "17") (pinfunction "IO9_17") (pintype "bidirectional"))
    )
    (net (code "248") (name "/SHIFT_CLK") (class "Default")
      (node (ref "U1") (pin "25") (pinfunction "IO48_25") (pintype "bidirectional"))
      (node (ref "U12") (pin "11") (pinfunction "CLK_11") (pintype "input"))
      (node (ref "U13") (pin "11") (pinfunction "CLK_11") (pintype "input"))
      (node (ref "U14") (pin "11") (pinfunction "CLK_11") (pintype "input"))
      (node (ref "U16") (pin "11") (pinfunction "CLK_11") (pintype "input"))
      (node (ref "U17") (pin "11") (pinfunction "CLK_11") (pintype "input"))
      (node (ref "U18") (pin "11") (pinfunction "CLK_11") (pintype "input"))
      (node (ref "U19") (pin "11") (pinfunction "CLK_11") (pintype "input"))
      (node (ref "U2") (pin "11") (pinfunction "CLK_11") (pintype "input"))
      (node (ref "U20") (pin "11") (pinfunction "CLK_11") (pintype "input"))
      (node (ref "U21") (pin "11") (pinfunction "CLK_11") (pintype "input"))
      (node (ref "U22") (pin "11") (pinfunction "CLK_11") (pintype "input"))
      (node (ref "U23") (pin "11") (pinfunction "CLK_11") (pintype "input"))
      (node (ref "U24") (pin "11") (pinfunction "CLK_11") (pintype "input"))
      (node (ref "U26") (pin "11") (pinfunction "CLK_11") (pintype "input"))
      (node (ref "U27") (pin "11") (pinfunction "CLK_11") (pintype "input"))
      (node (ref "U28") (pin "11") (pinfunction "CLK_11") (pintype "input"))
      (node (ref "U29") (pin "11") (pinfunction "CLK_11") (pintype "input"))
      (node (ref "U30") (pin "11") (pinfunction "CLK_11") (pintype "input"))
      (node (ref "U31") (pin "11") (pinfunction "CLK_11") (pintype "input"))
      (node (ref "U4") (pin "11") (pinfunction "CLK_11") (pintype "input"))
      (node (ref "U5") (pin "11") (pinfunction "CLK_11") (pintype "input"))
      (node (ref "U6") (pin "11") (pinfunction "CLK_11") (pintype "input"))
      (node (ref "U7") (pin "11") (pinfunction "CLK_11") (pintype "input"))
      (node (ref "U8") (pin "11") (pinfunction "CLK_11") (pintype "input"))
    )
    (net (code "249") (name "/SHND_AMPLI") (class "Default")
      (node (ref "U3") (pin "7") (pinfunction "IO7_7") (pintype "bidirectional"))
      (node (ref "U33") (pin "12") (pinfunction "SHND_12") (pintype "power_in"))
    )
    (net (code "250") (name "/TXD") (class "Default")
      (node (ref "D2") (pin "C") (pinfunction "C_C") (pintype "passive"))
      (node (ref "J2") (pin "4") (pinfunction "4_4") (pintype "passive"))
      (node (ref "U34") (pin "2") (pinfunction "TXD_2") (pintype "output"))
    )
    (net (code "251") (name "/TXD_ESP32-1") (class "Default")
      (node (ref "J7") (pin "1") (pinfunction "1_1") (pintype "passive"))
      (node (ref "U1") (pin "37") (pinfunction "TXD0_37") (pintype "bidirectional"))
    )
    (net (code "252") (name "/TXD_ESP32-2") (class "Default")
      (node (ref "J6") (pin "1") (pinfunction "1_1") (pintype "passive"))
      (node (ref "U3") (pin "37") (pinfunction "TXD0_37") (pintype "bidirectional"))
    )
    (net (code "253") (name "/TXD_S1_ESP32-1") (class "Default")
      (node (ref "CN4") (pin "4") (pinfunction "4_4") (pintype "passive"))
      (node (ref "U1") (pin "10") (pinfunction "IO17_10") (pintype "bidirectional"))
    )
    (net (code "254") (name "/TXD_S1_ESP32-2") (class "Default")
      (node (ref "J8") (pin "1") (pinfunction "1_1") (pintype "passive"))
      (node (ref "U3") (pin "10") (pinfunction "IO17_10") (pintype "bidirectional"))
    )
    (net (code "255") (name "/WS_MIC") (class "Default")
      (node (ref "MIC1") (pin "5") (pinfunction "WS_5") (pintype "passive"))
      (node (ref "U3") (pin "19") (pinfunction "IO11_19") (pintype "bidirectional"))
    )
    (net (code "256") (name "BAT+_SW") (class "Default")
      (node (ref "C3") (pin "1") (pinfunction "1_1") (pintype "passive"))
      (node (ref "D5") (pin "A") (pinfunction "A_A") (pintype "passive"))
      (node (ref "L1") (pin "1") (pinfunction "1_1") (pintype "passive"))
      (node (ref "SW1") (pin "1") (pinfunction "1_1") (pintype "passive"))
      (node (ref "U9") (pin "2") (pinfunction "EN_2") (pintype "input"))
      (node (ref "U9") (pin "4") (pinfunction "VIN_4") (pintype "input"))
    )
    (net (code "257") (name "GND") (class "Default")
      (node (ref "BT1") (pin "1") (pintype "passive"))
      (node (ref "BT10") (pin "2") (pintype "passive"))
      (node (ref "BT11") (pin "2") (pintype "passive"))
      (node (ref "BT12") (pin "1") (pintype "passive"))
      (node (ref "BT2") (pin "2") (pintype "passive"))
      (node (ref "BT3") (pin "1") (pintype "passive"))
      (node (ref "BT4") (pin "2") (pintype "passive"))
      (node (ref "BT5") (pin "1") (pintype "passive"))
      (node (ref "BT6") (pin "2") (pintype "passive"))
      (node (ref "BT7") (pin "1") (pintype "passive"))
      (node (ref "BT8") (pin "2") (pintype "passive"))
      (node (ref "BT9") (pin "1") (pintype "passive"))
      (node (ref "C1") (pin "1") (pinfunction "1_1") (pintype "passive"))
      (node (ref "C10") (pin "1") (pinfunction "1_1") (pintype "passive"))
      (node (ref "C11") (pin "1") (pinfunction "1_1") (pintype "passive"))
      (node (ref "C12") (pin "1") (pinfunction "1_1") (pintype "passive"))
      (node (ref "C13") (pin "2") (pinfunction "2_2") (pintype "passive"))
      (node (ref "C14") (pin "1") (pinfunction "1_1") (pintype "passive"))
      (node (ref "C15") (pin "1") (pinfunction "1_1") (pintype "passive"))
      (node (ref "C16") (pin "2") (pinfunction "2_2") (pintype "passive"))
      (node (ref "C17") (pin "2") (pinfunction "2_2") (pintype "passive"))
      (node (ref "C18") (pin "1") (pinfunction "1_1") (pintype "passive"))
      (node (ref "C19") (pin "1") (pinfunction "1_1") (pintype "passive"))
      (node (ref "C2") (pin "1") (pinfunction "1_1") (pintype "passive"))
      (node (ref "C21") (pin "1") (pinfunction "1_1") (pintype "passive"))
      (node (ref "C22") (pin "1") (pinfunction "1_1") (pintype "passive"))
      (node (ref "C23") (pin "1") (pinfunction "1_1") (pintype "passive"))
      (node (ref "C24") (pin "1") (pinfunction "1_1") (pintype "passive"))
      (node (ref "C25") (pin "1") (pinfunction "1_1") (pintype "passive"))
      (node (ref "C26") (pin "1") (pinfunction "1_1") (pintype "passive"))
      (node (ref "C27") (pin "1") (pinfunction "1_1") (pintype "passive"))
      (node (ref "C3") (pin "2") (pinfunction "2_2") (pintype "passive"))
      (node (ref "C4") (pin "1") (pinfunction "1_1") (pintype "passive"))
      (node (ref "C5") (pin "2") (pinfunction "2_2") (pintype "passive"))
      (node (ref "C6") (pin "2") (pinfunction "2_2") (pintype "passive"))
      (node (ref "C7") (pin "1") (pinfunction "1_1") (pintype "passive"))
      (node (ref "C8") (pin "1") (pinfunction "1_1") (pintype "passive"))
      (node (ref "C9") (pin "2") (pinfunction "2_2") (pintype "passive"))
      (node (ref "CN1") (pin "A1_B12") (pinfunction "GND_A1_B12") (pintype "power_in"))
      (node (ref "CN1") (pin "B1_A12") (pinfunction "GND_B1_A12") (pintype "power_in"))
      (node (ref "CN1") (pin "SH1") (pinfunction "SHIELD_SH1") (pintype "passive"))
      (node (ref "CN1") (pin "SH2") (pinfunction "SHIELD_SH2") (pintype "passive"))
      (node (ref "CN1") (pin "SH3") (pinfunction "SHIELD_SH3") (pintype "passive"))
      (node (ref "CN1") (pin "SH4") (pinfunction "SHIELD_SH4") (pintype "passive"))
      (node (ref "CN4") (pin "1") (pinfunction "1_1") (pintype "passive"))
      (node (ref "CN5") (pin "4") (pinfunction "4_4") (pintype "passive"))
      (node (ref "D10") (pin "A") (pinfunction "A_A") (pintype "passive"))
      (node (ref "D9") (pin "A") (pinfunction "A_A") (pintype "passive"))
      (node (ref "DP1") (pin "2") (pinfunction "GND_2") (pintype "power_in"))
      (node (ref "J1") (pin "B1A") (pinfunction "BUT_B1A") (pintype "passive"))
      (node (ref "J1") (pin "H3") (pinfunction "H-_H3") (pintype "passive"))
      (node (ref "J1") (pin "S1") (pinfunction "SHIELD_S1") (pintype "passive"))
      (node (ref "J1") (pin "S2") (pinfunction "SHIELD_S2") (pintype "passive"))
      (node (ref "J1") (pin "S3") (pinfunction "SHIELD_S3") (pintype "passive"))
      (node (ref "J1") (pin "S4") (pinfunction "SHIELD_S4") (pintype "passive"))
      (node (ref "J1") (pin "V3") (pinfunction "V-_V3") (pintype "passive"))
      (node (ref "J2") (pin "1") (pinfunction "1_1") (pintype "passive"))
      (node (ref "J3") (pin "1") (pinfunction "GND_1") (pintype "passive"))
      (node (ref "J4") (pin "B1A") (pinfunction "BUT_B1A") (pintype "passive"))
      (node (ref "J4") (pin "H3") (pinfunction "H-_H3") (pintype "passive"))
      (node (ref "J4") (pin "S1") (pinfunction "SHIELD_S1") (pintype "passive"))
      (node (ref "J4") (pin "S2") (pinfunction "SHIELD_S2") (pintype "passive"))
      (node (ref "J4") (pin "S3") (pinfunction "SHIELD_S3") (pintype "passive"))
      (node (ref "J4") (pin "S4") (pinfunction "SHIELD_S4") (pintype "passive"))
      (node (ref "J4") (pin "V3") (pinfunction "V-_V3") (pintype "passive"))
      (node (ref "J5") (pin "1") (pinfunction "1_1") (pintype "passive"))
      (node (ref "J6") (pin "3") (pinfunction "3_3") (pintype "passive"))
      (node (ref "J7") (pin "3") (pinfunction "3_3") (pintype "passive"))
      (node (ref "J8") (pin "3") (pinfunction "3_3") (pintype "passive"))
      (node (ref "MIC1") (pin "3") (pinfunction "GND_3") (pintype "passive"))
      (node (ref "R158") (pin "1") (pinfunction "1_1") (pintype "passive"))
      (node (ref "R159") (pin "2") (pinfunction "2_2") (pintype "passive"))
      (node (ref "R164") (pin "2") (pinfunction "2_2") (pintype "passive"))
      (node (ref "R166") (pin "2") (pinfunction "2_2") (pintype "passive"))
      (node (ref "R17") (pin "2") (pinfunction "2_2") (pintype "passive"))
      (node (ref "SD1") (pin "P6") (pinfunction "VSS_P6") (pintype "passive"))
      (node (ref "U1") (pin "1") (pinfunction "GND_1") (pintype "power_in"))
      (node (ref "U1") (pin "40") (pinfunction "GND_40") (pintype "power_in"))
      (node (ref "U1") (pin "41_1") (pinfunction "GND_41_1") (pintype "power_in"))
      (node (ref "U1") (pin "41_2") (pinfunction "GND_41_2") (pintype "power_in"))
      (node (ref "U1") (pin "41_3") (pinfunction "GND_41_3") (pintype "power_in"))
      (node (ref "U1") (pin "41_4") (pinfunction "GND_41_4") (pintype "power_in"))
      (node (ref "U1") (pin "41_5") (pinfunction "GND_41_5") (pintype "power_in"))
      (node (ref "U1") (pin "41_6") (pinfunction "GND_41_6") (pintype "power_in"))
      (node (ref "U1") (pin "41_7") (pinfunction "GND_41_7") (pintype "power_in"))
      (node (ref "U1") (pin "41_8") (pinfunction "GND_41_8") (pintype "power_in"))
      (node (ref "U1") (pin "41_9") (pinfunction "GND_41_9") (pintype "power_in"))
      (node (ref "U10") (pin "3") (pinfunction "GND_3") (pintype "power_in"))
      (node (ref "U11") (pin "1") (pinfunction "CLKIN_1") (pintype "input"))
      (node (ref "U11") (pin "11") (pinfunction "FSYNC_11") (pintype "input"))
      (node (ref "U11") (pin "18") (pinfunction "GND_18") (pintype "power_in"))
      (node (ref "U12") (pin "13") (pinfunction "~{OE}_13") (pintype "input"))
      (node (ref "U12") (pin "8") (pinfunction "GND_8") (pintype "power_in"))
      (node (ref "U13") (pin "13") (pinfunction "~{OE}_13") (pintype "input"))
      (node (ref "U13") (pin "8") (pinfunction "GND_8") (pintype "power_in"))
      (node (ref "U14") (pin "13") (pinfunction "~{OE}_13") (pintype "input"))
      (node (ref "U14") (pin "8") (pinfunction "GND_8") (pintype "power_in"))
      (node (ref "U15") (pin "1") (pinfunction "ADJ/GND_1") (pintype "passive"))
      (node (ref "U16") (pin "13") (pinfunction "~{OE}_13") (pintype "input"))
      (node (ref "U16") (pin "8") (pinfunction "GND_8") (pintype "power_in"))
      (node (ref "U17") (pin "13") (pinfunction "~{OE}_13") (pintype "input"))
      (node (ref "U17") (pin "8") (pinfunction "GND_8") (pintype "power_in"))
      (node (ref "U18") (pin "13") (pinfunction "~{OE}_13") (pintype "input"))
      (node (ref "U18") (pin "8") (pinfunction "GND_8") (pintype "power_in"))
      (node (ref "U19") (pin "13") (pinfunction "~{OE}_13") (pintype "input"))
      (node (ref "U19") (pin "8") (pinfunction "GND_8") (pintype "power_in"))
      (node (ref "U2") (pin "13") (pinfunction "~{OE}_13") (pintype "input"))
      (node (ref "U2") (pin "8") (pinfunction "GND_8") (pintype "power_in"))
      (node (ref "U20") (pin "13") (pinfunction "~{OE}_13") (pintype "input"))
      (node (ref "U20") (pin "8") (pinfunction "GND_8") (pintype "power_in"))
      (node (ref "U21") (pin "13") (pinfunction "~{OE}_13") (pintype "input"))
      (node (ref "U21") (pin "8") (pinfunction "GND_8") (pintype "power_in"))
      (node (ref "U22") (pin "13") (pinfunction "~{OE}_13") (pintype "input"))
      (node (ref "U22") (pin "8") (pinfunction "GND_8") (pintype "power_in"))
      (node (ref "U23") (pin "13") (pinfunction "~{OE}_13") (pintype "input"))
      (node (ref "U23") (pin "8") (pinfunction "GND_8") (pintype "power_in"))
      (node (ref "U24") (pin "13") (pinfunction "~{OE}_13") (pintype "input"))
      (node (ref "U24") (pin "8") (pinfunction "GND_8") (pintype "power_in"))
      (node (ref "U25") (pin "10") (pinfunction "DEMP_10") (pintype "input"))
      (node (ref "U25") (pin "12") (pinfunction "SCK_12") (pintype "input"))
      (node (ref "U25") (pin "16") (pinfunction "FMT_16") (pintype "input"))
      (node (ref "U25") (pin "19") (pinfunction "DGND_19") (pintype "power_in"))
      (node (ref "U25") (pin "3") (pinfunction "CPGND_3") (pintype "power_in"))
      (node (ref "U25") (pin "9") (pinfunction "AGND_9") (pintype "power_in"))
      (node (ref "U26") (pin "13") (pinfunction "~{OE}_13") (pintype "input"))
      (node (ref "U26") (pin "8") (pinfunction "GND_8") (pintype "power_in"))
      (node (ref "U27") (pin "13") (pinfunction "~{OE}_13") (pintype "input"))
      (node (ref "U27") (pin "8") (pinfunction "GND_8") (pintype "power_in"))
      (node (ref "U28") (pin "13") (pinfunction "~{OE}_13") (pintype "input"))
      (node (ref "U28") (pin "8") (pinfunction "GND_8") (pintype "power_in"))
      (node (ref "U29") (pin "13") (pinfunction "~{OE}_13") (pintype "input"))
      (node (ref "U29") (pin "8") (pinfunction "GND_8") (pintype "power_in"))
      (node (ref "U3") (pin "1") (pinfunction "GND_1") (pintype "power_in"))
      (node (ref "U3") (pin "40") (pinfunction "GND_40") (pintype "power_in"))
      (node (ref "U3") (pin "41_1") (pinfunction "GND_41_1") (pintype "power_in"))
      (node (ref "U3") (pin "41_2") (pinfunction "GND_41_2") (pintype "power_in"))
      (node (ref "U3") (pin "41_3") (pinfunction "GND_41_3") (pintype "power_in"))
      (node (ref "U3") (pin "41_4") (pinfunction "GND_41_4") (pintype "power_in"))
      (node (ref "U3") (pin "41_5") (pinfunction "GND_41_5") (pintype "power_in"))
      (node (ref "U3") (pin "41_6") (pinfunction "GND_41_6") (pintype "power_in"))
      (node (ref "U3") (pin "41_7") (pinfunction "GND_41_7") (pintype "power_in"))
      (node (ref "U3") (pin "41_8") (pinfunction "GND_41_8") (pintype "power_in"))
      (node (ref "U3") (pin "41_9") (pinfunction "GND_41_9") (pintype "power_in"))
      (node (ref "U30") (pin "13") (pinfunction "~{OE}_13") (pintype "input"))
      (node (ref "U30") (pin "8") (pinfunction "GND_8") (pintype "power_in"))
      (node (ref "U31") (pin "13") (pinfunction "~{OE}_13") (pintype "input"))
      (node (ref "U31") (pin "8") (pinfunction "GND_8") (pintype "power_in"))
      (node (ref "U32") (pin "1") (pinfunction "1~{OE}_1") (pintype "input"))
      (node (ref "U32") (pin "10") (pinfunction "3~{OE}_10") (pintype "input"))
      (node (ref "U32") (pin "13") (pinfunction "4~{OE}_13") (pintype "input"))
      (node (ref "U32") (pin "4") (pinfunction "2~{OE}_4") (pintype "input"))
      (node (ref "U32") (pin "7") (pinfunction "GND_7") (pintype "power_in"))
      (node (ref "U33") (pin "11") (pinfunction "GND_11") (pintype "power_in"))
      (node (ref "U33") (pin "15") (pinfunction "PGND@2_15") (pintype "power_in"))
      (node (ref "U33") (pin "2") (pinfunction "PGND@1_2") (pintype "power_in"))
      (node (ref "U33") (pin "9") (pinfunction "NC_9") (pintype "passive"))
      (node (ref "U34") (pin "1") (pinfunction "GND_1") (pintype "power_in"))
      (node (ref "U4") (pin "13") (pinfunction "~{OE}_13") (pintype "input"))
      (node (ref "U4") (pin "8") (pinfunction "GND_8") (pintype "power_in"))
      (node (ref "U5") (pin "13") (pinfunction "~{OE}_13") (pintype "input"))
      (node (ref "U5") (pin "8") (pinfunction "GND_8") (pintype "power_in"))
      (node (ref "U6") (pin "13") (pinfunction "~{OE}_13") (pintype "input"))
      (node (ref "U6") (pin "8") (pinfunction "GND_8") (pintype "power_in"))
      (node (ref "U7") (pin "13") (pinfunction "~{OE}_13") (pintype "input"))
      (node (ref "U7") (pin "8") (pinfunction "GND_8") (pintype "power_in"))
      (node (ref "U8") (pin "13") (pinfunction "~{OE}_13") (pintype "input"))
      (node (ref "U8") (pin "8") (pinfunction "GND_8") (pintype "power_in"))
      (node (ref "U9") (pin "1") (pinfunction "GND_1") (pintype "power_in"))
    )
    (net (code "258") (name "Net-(BAT1-NEG)") (class "Default")
      (node (ref "BAT1") (pin "N") (pinfunction "NEG_N") (pintype "passive"))
      (node (ref "D10") (pin "K") (pinfunction "K_K") (pintype "passive"))
    )
    (net (code "259") (name "Net-(BAT2-NEG)") (class "Default")
      (node (ref "BAT2") (pin "N") (pinfunction "NEG_N") (pintype "passive"))
      (node (ref "D9") (pin "K") (pinfunction "K_K") (pintype "passive"))
    )
    (net (code "260") (name "Net-(C28-Pad1)") (class "Default")
      (node (ref "C28") (pin "1") (pinfunction "1_1") (pintype "passive"))
      (node (ref "R165") (pin "1") (pinfunction "1_1") (pintype "passive"))
    )
    (net (code "261") (name "Net-(C29-Pad1)") (class "Default")
      (node (ref "C29") (pin "1") (pinfunction "1_1") (pintype "passive"))
      (node (ref "R167") (pin "1") (pinfunction "1_1") (pintype "passive"))
    )
    (net (code "262") (name "Net-(D1-PadA)") (class "Default")
      (node (ref "D1") (pin "A") (pinfunction "A_A") (pintype "passive"))
      (node (ref "R13") (pin "1") (pinfunction "1_1") (pintype "passive"))
    )
    (net (code "263") (name "Net-(D2-PadA)") (class "Default")
      (node (ref "D2") (pin "A") (pinfunction "A_A") (pintype "passive"))
      (node (ref "R23") (pin "1") (pinfunction "1_1") (pintype "passive"))
    )
    (net (code "264") (name "Net-(D3-PadC)") (class "Default")
      (node (ref "D3") (pin "C") (pinfunction "C_C") (pintype "passive"))
      (node (ref "R14") (pin "1") (pinfunction "1_1") (pintype "passive"))
    )
    (net (code "265") (name "Net-(D4-PadC)") (class "Default")
      (node (ref "D4") (pin "C") (pinfunction "C_C") (pintype "passive"))
      (node (ref "R15") (pin "1") (pinfunction "1_1") (pintype "passive"))
    )
    (net (code "266") (name "Net-(D5-PadC)") (class "Default")
      (node (ref "D5") (pin "C") (pinfunction "C_C") (pintype "passive"))
      (node (ref "R159") (pin "1") (pinfunction "1_1") (pintype "passive"))
    )
    (net (code "267") (name "Net-(D6-PadA)") (class "Default")
      (node (ref "D6") (pin "A") (pinfunction "A_A") (pintype "passive"))
      (node (ref "L1") (pin "2") (pinfunction "2_2") (pintype "passive"))
      (node (ref "U9") (pin "3") (pinfunction "SW_3") (pintype "output"))
    )
    (net (code "268") (name "Net-(D7-PadA)") (class "Default")
      (node (ref "D7") (pin "A") (pinfunction "A_A") (pintype "passive"))
      (node (ref "D8") (pin "K") (pinfunction "K_K") (pintype "passive"))
    )
    (net (code "269") (name "Net-(F2-Pad2)") (class "Default")
      (node (ref "F2") (pin "2") (pinfunction "2_2") (pintype "passive"))
      (node (ref "SW1") (pin "2") (pinfunction "2_2") (pintype "passive"))
    )
    (net (code "270") (name "Net-(J3-Left_out)") (class "Default")
      (node (ref "C15") (pin "2") (pinfunction "2_2") (pintype "passive"))
      (node (ref "J3") (pin "3") (pinfunction "Left_out_3") (pintype "passive"))
      (node (ref "R121") (pin "1") (pinfunction "1_1") (pintype "passive"))
    )
    (net (code "271") (name "Net-(J3-Right_out)") (class "Default")
      (node (ref "C7") (pin "2") (pinfunction "2_2") (pintype "passive"))
      (node (ref "J3") (pin "4") (pinfunction "Right_out_4") (pintype "passive"))
      (node (ref "R160") (pin "1") (pinfunction "1_1") (pintype "passive"))
    )
    (net (code "272") (name "Net-(Matrix1-17)") (class "Default")
      (node (ref "Matrix1") (pin "13") (pinfunction "17_13") (pintype "passive"))
      (node (ref "R32") (pin "1") (pinfunction "1_1") (pintype "passive"))
    )
    (net (code "273") (name "Net-(Matrix1-18)") (class "Default")
      (node (ref "Matrix1") (pin "14") (pinfunction "18_14") (pintype "passive"))
      (node (ref "R31") (pin "1") (pinfunction "1_1") (pintype "passive"))
    )
    (net (code "274") (name "Net-(Matrix1-19)") (class "Default")
      (node (ref "Matrix1") (pin "15") (pinfunction "19_15") (pintype "passive"))
      (node (ref "R30") (pin "1") (pinfunction "1_1") (pintype "passive"))
    )
    (net (code "275") (name "Net-(Matrix1-20)") (class "Default")
      (node (ref "Matrix1") (pin "16") (pinfunction "20_16") (pintype "passive"))
      (node (ref "R29") (pin "1") (pinfunction "1_1") (pintype "passive"))
    )
    (net (code "276") (name "Net-(Matrix1-21)") (class "Default")
      (node (ref "Matrix1") (pin "17") (pinfunction "21_17") (pintype "passive"))
      (node (ref "R28") (pin "1") (pinfunction "1_1") (pintype "passive"))
    )
    (net (code "277") (name "Net-(Matrix1-22)") (class "Default")
      (node (ref "Matrix1") (pin "18") (pinfunction "22_18") (pintype "passive"))
      (node (ref "R27") (pin "1") (pinfunction "1_1") (pintype "passive"))
    )
    (net (code "278") (name "Net-(Matrix1-23)") (class "Default")
      (node (ref "Matrix1") (pin "19") (pinfunction "23_19") (pintype "passive"))
      (node (ref "R26") (pin "1") (pinfunction "1_1") (pintype "passive"))
    )
    (net (code "279") (name "Net-(Matrix1-24)") (class "Default")
      (node (ref "Matrix1") (pin "20") (pinfunction "24_20") (pintype "passive"))
      (node (ref "R25") (pin "1") (pinfunction "1_1") (pintype "passive"))
    )
    (net (code "280") (name "Net-(Matrix1-Pad5)") (class "Default")
      (node (ref "Matrix1") (pin "5") (pinfunction "5_5") (pintype "passive"))
      (node (ref "R57") (pin "2") (pinfunction "2_2") (pintype "passive"))
    )
    (net (code "281") (name "Net-(Matrix1-Pad6)") (class "Default")
      (node (ref "Matrix1") (pin "6") (pinfunction "6_6") (pintype "passive"))
      (node (ref "R58") (pin "2") (pinfunction "2_2") (pintype "passive"))
    )
    (net (code "282") (name "Net-(Matrix1-Pad7)") (class "Default")
      (node (ref "Matrix1") (pin "7") (pinfunction "7_7") (pintype "passive"))
      (node (ref "R59") (pin "2") (pinfunction "2_2") (pintype "passive"))
    )
    (net (code "283") (name "Net-(Matrix1-Pad8)") (class "Default")
      (node (ref "Matrix1") (pin "8") (pinfunction "8_8") (pintype "passive"))
      (node (ref "R60") (pin "2") (pinfunction "2_2") (pintype "passive"))
    )
    (net (code "284") (name "Net-(Matrix1-Pad9)") (class "Default")
      (node (ref "Matrix1") (pin "9") (pinfunction "9_9") (pintype "passive"))
      (node (ref "R61") (pin "2") (pinfunction "2_2") (pintype "passive"))
    )
    (net (code "285") (name "Net-(Matrix1-Pad10)") (class "Default")
      (node (ref "Matrix1") (pin "10") (pinfunction "10_10") (pintype "passive"))
      (node (ref "R62") (pin "2") (pinfunction "2_2") (pintype "passive"))
    )
    (net (code "286") (name "Net-(Matrix1-Pad11)") (class "Default")
      (node (ref "Matrix1") (pin "11") (pinfunction "11_11") (pintype "passive"))
      (node (ref "R63") (pin "2") (pinfunction "2_2") (pintype "passive"))
    )
    (net (code "287") (name "Net-(Matrix1-Pad12)") (class "Default")
      (node (ref "Matrix1") (pin "12") (pinfunction "12_12") (pintype "passive"))
      (node (ref "R64") (pin "2") (pinfunction "2_2") (pintype "passive"))
    )
    (net (code "288") (name "Net-(Matrix2-17)") (class "Default")
      (node (ref "Matrix2") (pin "13") (pinfunction "17_13") (pintype "passive"))
      (node (ref "R40") (pin "1") (pinfunction "1_1") (pintype "passive"))
    )
    (net (code "289") (name "Net-(Matrix2-18)") (class "Default")
      (node (ref "Matrix2") (pin "14") (pinfunction "18_14") (pintype "passive"))
      (node (ref "R39") (pin "1") (pinfunction "1_1") (pintype "passive"))
    )
    (net (code "290") (name "Net-(Matrix2-19)") (class "Default")
      (node (ref "Matrix2") (pin "15") (pinfunction "19_15") (pintype "passive"))
      (node (ref "R38") (pin "1") (pinfunction "1_1") (pintype "passive"))
    )
    (net (code "291") (name "Net-(Matrix2-20)") (class "Default")
      (node (ref "Matrix2") (pin "16") (pinfunction "20_16") (pintype "passive"))
      (node (ref "R37") (pin "1") (pinfunction "1_1") (pintype "passive"))
    )
    (net (code "292") (name "Net-(Matrix2-21)") (class "Default")
      (node (ref "Matrix2") (pin "17") (pinfunction "21_17") (pintype "passive"))
      (node (ref "R36") (pin "1") (pinfunction "1_1") (pintype "passive"))
    )
    (net (code "293") (name "Net-(Matrix2-22)") (class "Default")
      (node (ref "Matrix2") (pin "18") (pinfunction "22_18") (pintype "passive"))
      (node (ref "R35") (pin "1") (pinfunction "1_1") (pintype "passive"))
    )
    (net (code "294") (name "Net-(Matrix2-23)") (class "Default")
      (node (ref "Matrix2") (pin "19") (pinfunction "23_19") (pintype "passive"))
      (node (ref "R34") (pin "1") (pinfunction "1_1") (pintype "passive"))
    )
    (net (code "295") (name "Net-(Matrix2-24)") (class "Default")
      (node (ref "Matrix2") (pin "20") (pinfunction "24_20") (pintype "passive"))
      (node (ref "R33") (pin "1") (pinfunction "1_1") (pintype "passive"))
    )
    (net (code "296") (name "Net-(Matrix2-Pad5)") (class "Default")
      (node (ref "Matrix2") (pin "5") (pinfunction "5_5") (pintype "passive"))
      (node (ref "R65") (pin "2") (pinfunction "2_2") (pintype "passive"))
    )
    (net (code "297") (name "Net-(Matrix2-Pad6)") (class "Default")
      (node (ref "Matrix2") (pin "6") (pinfunction "6_6") (pintype "passive"))
      (node (ref "R66") (pin "2") (pinfunction "2_2") (pintype "passive"))
    )
    (net (code "298") (name "Net-(Matrix2-Pad7)") (class "Default")
      (node (ref "Matrix2") (pin "7") (pinfunction "7_7") (pintype "passive"))
      (node (ref "R67") (pin "2") (pinfunction "2_2") (pintype "passive"))
    )
    (net (code "299") (name "Net-(Matrix2-Pad8)") (class "Default")
      (node (ref "Matrix2") (pin "8") (pinfunction "8_8") (pintype "passive"))
      (node (ref "R68") (pin "2") (pinfunction "2_2") (pintype "passive"))
    )
    (net (code "300") (name "Net-(Matrix2-Pad9)") (class "Default")
      (node (ref "Matrix2") (pin "9") (pinfunction "9_9") (pintype "passive"))
      (node (ref "R69") (pin "2") (pinfunction "2_2") (pintype "passive"))
    )
    (net (code "301") (name "Net-(Matrix2-Pad10)") (class "Default")
      (node (ref "Matrix2") (pin "10") (pinfunction "10_10") (pintype "passive"))
      (node (ref "R70") (pin "2") (pinfunction "2_2") (pintype "passive"))
    )
    (net (code "302") (name "Net-(Matrix2-Pad11)") (class "Default")
      (node (ref "Matrix2") (pin "11") (pinfunction "11_11") (pintype "passive"))
      (node (ref "R71") (pin "2") (pinfunction "2_2") (pintype "passive"))
    )
    (net (code "303") (name "Net-(Matrix2-Pad12)") (class "Default")
      (node (ref "Matrix2") (pin "12") (pinfunction "12_12") (pintype "passive"))
      (node (ref "R72") (pin "2") (pinfunction "2_2") (pintype "passive"))
    )
    (net (code "304") (name "Net-(Matrix3-17)") (class "Default")
      (node (ref "Matrix3") (pin "13") (pinfunction "17_13") (pintype "passive"))
      (node (ref "R56") (pin "1") (pinfunction "1_1") (pintype "passive"))
    )
    (net (code "305") (name "Net-(Matrix3-18)") (class "Default")
      (node (ref "Matrix3") (pin "14") (pinfunction "18_14") (pintype "passive"))
      (node (ref "R55") (pin "1") (pinfunction "1_1") (pintype "passive"))
    )
    (net (code "306") (name "Net-(Matrix3-19)") (class "Default")
      (node (ref "Matrix3") (pin "15") (pinfunction "19_15") (pintype "passive"))
      (node (ref "R54") (pin "1") (pinfunction "1_1") (pintype "passive"))
    )
    (net (code "307") (name "Net-(Matrix3-20)") (class "Default")
      (node (ref "Matrix3") (pin "16") (pinfunction "20_16") (pintype "passive"))
      (node (ref "R53") (pin "1") (pinfunction "1_1") (pintype "passive"))
    )
    (net (code "308") (name "Net-(Matrix3-21)") (class "Default")
      (node (ref "Matrix3") (pin "17") (pinfunction "21_17") (pintype "passive"))
      (node (ref "R52") (pin "1") (pinfunction "1_1") (pintype "passive"))
    )
    (net (code "309") (name "Net-(Matrix3-22)") (class "Default")
      (node (ref "Matrix3") (pin "18") (pinfunction "22_18") (pintype "passive"))
      (node (ref "R51") (pin "1") (pinfunction "1_1") (pintype "passive"))
    )
    (net (code "310") (name "Net-(Matrix3-23)") (class "Default")
      (node (ref "Matrix3") (pin "19") (pinfunction "23_19") (pintype "passive"))
      (node (ref "R50") (pin "1") (pinfunction "1_1") (pintype "passive"))
    )
    (net (code "311") (name "Net-(Matrix3-24)") (class "Default")
      (node (ref "Matrix3") (pin "20") (pinfunction "24_20") (pintype "passive"))
      (node (ref "R49") (pin "1") (pinfunction "1_1") (pintype "passive"))
    )
    (net (code "312") (name "Net-(Matrix3-Pad5)") (class "Default")
      (node (ref "Matrix3") (pin "5") (pinfunction "5_5") (pintype "passive"))
      (node (ref "R81") (pin "2") (pinfunction "2_2") (pintype "passive"))
    )
    (net (code "313") (name "Net-(Matrix3-Pad6)") (class "Default")
      (node (ref "Matrix3") (pin "6") (pinfunction "6_6") (pintype "passive"))
      (node (ref "R82") (pin "2") (pinfunction "2_2") (pintype "passive"))
    )
    (net (code "314") (name "Net-(Matrix3-Pad7)") (class "Default")
      (node (ref "Matrix3") (pin "7") (pinfunction "7_7") (pintype "passive"))
      (node (ref "R83") (pin "2") (pinfunction "2_2") (pintype "passive"))
    )
    (net (code "315") (name "Net-(Matrix3-Pad8)") (class "Default")
      (node (ref "Matrix3") (pin "8") (pinfunction "8_8") (pintype "passive"))
      (node (ref "R84") (pin "2") (pinfunction "2_2") (pintype "passive"))
    )
    (net (code "316") (name "Net-(Matrix3-Pad9)") (class "Default")
      (node (ref "Matrix3") (pin "9") (pinfunction "9_9") (pintype "passive"))
      (node (ref "R85") (pin "2") (pinfunction "2_2") (pintype "passive"))
    )
    (net (code "317") (name "Net-(Matrix3-Pad10)") (class "Default")
      (node (ref "Matrix3") (pin "10") (pinfunction "10_10") (pintype "passive"))
      (node (ref "R86") (pin "2") (pinfunction "2_2") (pintype "passive"))
    )
    (net (code "318") (name "Net-(Matrix3-Pad11)") (class "Default")
      (node (ref "Matrix3") (pin "11") (pinfunction "11_11") (pintype "passive"))
      (node (ref "R87") (pin "2") (pinfunction "2_2") (pintype "passive"))
    )
    (net (code "319") (name "Net-(Matrix3-Pad12)") (class "Default")
      (node (ref "Matrix3") (pin "12") (pinfunction "12_12") (pintype "passive"))
      (node (ref "R88") (pin "2") (pinfunction "2_2") (pintype "passive"))
    )
    (net (code "320") (name "Net-(Matrix4-17)") (class "Default")
      (node (ref "Matrix4") (pin "13") (pinfunction "17_13") (pintype "passive"))
      (node (ref "R48") (pin "1") (pinfunction "1_1") (pintype "passive"))
    )
    (net (code "321") (name "Net-(Matrix4-18)") (class "Default")
      (node (ref "Matrix4") (pin "14") (pinfunction "18_14") (pintype "passive"))
      (node (ref "R47") (pin "1") (pinfunction "1_1") (pintype "passive"))
    )
    (net (code "322") (name "Net-(Matrix4-19)") (class "Default")
      (node (ref "Matrix4") (pin "15") (pinfunction "19_15") (pintype "passive"))
      (node (ref "R46") (pin "1") (pinfunction "1_1") (pintype "passive"))
    )
    (net (code "323") (name "Net-(Matrix4-20)") (class "Default")
      (node (ref "Matrix4") (pin "16") (pinfunction "20_16") (pintype "passive"))
      (node (ref "R45") (pin "1") (pinfunction "1_1") (pintype "passive"))
    )
    (net (code "324") (name "Net-(Matrix4-21)") (class "Default")
      (node (ref "Matrix4") (pin "17") (pinfunction "21_17") (pintype "passive"))
      (node (ref "R44") (pin "1") (pinfunction "1_1") (pintype "passive"))
    )
    (net (code "325") (name "Net-(Matrix4-22)") (class "Default")
      (node (ref "Matrix4") (pin "18") (pinfunction "22_18") (pintype "passive"))
      (node (ref "R43") (pin "1") (pinfunction "1_1") (pintype "passive"))
    )
    (net (code "326") (name "Net-(Matrix4-23)") (class "Default")
      (node (ref "Matrix4") (pin "19") (pinfunction "23_19") (pintype "passive"))
      (node (ref "R42") (pin "1") (pinfunction "1_1") (pintype "passive"))
    )
    (net (code "327") (name "Net-(Matrix4-24)") (class "Default")
      (node (ref "Matrix4") (pin "20") (pinfunction "24_20") (pintype "passive"))
      (node (ref "R41") (pin "1") (pinfunction "1_1") (pintype "passive"))
    )
    (net (code "328") (name "Net-(Matrix4-Pad5)") (class "Default")
      (node (ref "Matrix4") (pin "5") (pinfunction "5_5") (pintype "passive"))
      (node (ref "R73") (pin "2") (pinfunction "2_2") (pintype "passive"))
    )
    (net (code "329") (name "Net-(Matrix4-Pad6)") (class "Default")
      (node (ref "Matrix4") (pin "6") (pinfunction "6_6") (pintype "passive"))
      (node (ref "R74") (pin "2") (pinfunction "2_2") (pintype "passive"))
    )
    (net (code "330") (name "Net-(Matrix4-Pad7)") (class "Default")
      (node (ref "Matrix4") (pin "7") (pinfunction "7_7") (pintype "passive"))
      (node (ref "R75") (pin "2") (pinfunction "2_2") (pintype "passive"))
    )
    (net (code "331") (name "Net-(Matrix4-Pad8)") (class "Default")
      (node (ref "Matrix4") (pin "8") (pinfunction "8_8") (pintype "passive"))
      (node (ref "R76") (pin "2") (pinfunction "2_2") (pintype "passive"))
    )
    (net (code "332") (name "Net-(Matrix4-Pad9)") (class "Default")
      (node (ref "Matrix4") (pin "9") (pinfunction "9_9") (pintype "passive"))
      (node (ref "R77") (pin "2") (pinfunction "2_2") (pintype "passive"))
    )
    (net (code "333") (name "Net-(Matrix4-Pad10)") (class "Default")
      (node (ref "Matrix4") (pin "10") (pinfunction "10_10") (pintype "passive"))
      (node (ref "R78") (pin "2") (pinfunction "2_2") (pintype "passive"))
    )
    (net (code "334") (name "Net-(Matrix4-Pad11)") (class "Default")
      (node (ref "Matrix4") (pin "11") (pinfunction "11_11") (pintype "passive"))
      (node (ref "R79") (pin "2") (pinfunction "2_2") (pintype "passive"))
    )
    (net (code "335") (name "Net-(Matrix4-Pad12)") (class "Default")
      (node (ref "Matrix4") (pin "12") (pinfunction "12_12") (pintype "passive"))
      (node (ref "R80") (pin "2") (pinfunction "2_2") (pintype "passive"))
    )
    (net (code "336") (name "Net-(Matrix5-17)") (class "Default")
      (node (ref "Matrix5") (pin "13") (pinfunction "17_13") (pintype "passive"))
      (node (ref "R112") (pin "1") (pinfunction "1_1") (pintype "passive"))
    )
    (net (code "337") (name "Net-(Matrix5-18)") (class "Default")
      (node (ref "Matrix5") (pin "14") (pinfunction "18_14") (pintype "passive"))
      (node (ref "R111") (pin "1") (pinfunction "1_1") (pintype "passive"))
    )
    (net (code "338") (name "Net-(Matrix5-19)") (class "Default")
      (node (ref "Matrix5") (pin "15") (pinfunction "19_15") (pintype "passive"))
      (node (ref "R110") (pin "1") (pinfunction "1_1") (pintype "passive"))
    )
    (net (code "339") (name "Net-(Matrix5-20)") (class "Default")
      (node (ref "Matrix5") (pin "16") (pinfunction "20_16") (pintype "passive"))
      (node (ref "R109") (pin "1") (pinfunction "1_1") (pintype "passive"))
    )
    (net (code "340") (name "Net-(Matrix5-21)") (class "Default")
      (node (ref "Matrix5") (pin "17") (pinfunction "21_17") (pintype "passive"))
      (node (ref "R108") (pin "1") (pinfunction "1_1") (pintype "passive"))
    )
    (net (code "341") (name "Net-(Matrix5-22)") (class "Default")
      (node (ref "Matrix5") (pin "18") (pinfunction "22_18") (pintype "passive"))
      (node (ref "R107") (pin "1") (pinfunction "1_1") (pintype "passive"))
    )
    (net (code "342") (name "Net-(Matrix5-23)") (class "Default")
      (node (ref "Matrix5") (pin "19") (pinfunction "23_19") (pintype "passive"))
      (node (ref "R106") (pin "1") (pinfunction "1_1") (pintype "passive"))
    )
    (net (code "343") (name "Net-(Matrix5-24)") (class "Default")
      (node (ref "Matrix5") (pin "20") (pinfunction "24_20") (pintype "passive"))
      (node (ref "R105") (pin "1") (pinfunction "1_1") (pintype "passive"))
    )
    (net (code "344") (name "Net-(Matrix5-Pad5)") (class "Default")
      (node (ref "Matrix5") (pin "5") (pinfunction "5_5") (pintype "passive"))
      (node (ref "R138") (pin "2") (pinfunction "2_2") (pintype "passive"))
    )
    (net (code "345") (name "Net-(Matrix5-Pad6)") (class "Default")
      (node (ref "Matrix5") (pin "6") (pinfunction "6_6") (pintype "passive"))
      (node (ref "R139") (pin "2") (pinfunction "2_2") (pintype "passive"))
    )
    (net (code "346") (name "Net-(Matrix5-Pad7)") (class "Default")
      (node (ref "Matrix5") (pin "7") (pinfunction "7_7") (pintype "passive"))
      (node (ref "R140") (pin "2") (pinfunction "2_2") (pintype "passive"))
    )
    (net (code "347") (name "Net-(Matrix5-Pad8)") (class "Default")
      (node (ref "Matrix5") (pin "8") (pinfunction "8_8") (pintype "passive"))
      (node (ref "R141") (pin "2") (pinfunction "2_2") (pintype "passive"))
    )
    (net (code "348") (name "Net-(Matrix5-Pad9)") (class "Default")
      (node (ref "Matrix5") (pin "9") (pinfunction "9_9") (pintype "passive"))
      (node (ref "R142") (pin "2") (pinfunction "2_2") (pintype "passive"))
    )
    (net (code "349") (name "Net-(Matrix5-Pad10)") (class "Default")
      (node (ref "Matrix5") (pin "10") (pinfunction "10_10") (pintype "passive"))
      (node (ref "R143") (pin "2") (pinfunction "2_2") (pintype "passive"))
    )
    (net (code "350") (name "Net-(Matrix5-Pad11)") (class "Default")
      (node (ref "Matrix5") (pin "11") (pinfunction "11_11") (pintype "passive"))
      (node (ref "R144") (pin "2") (pinfunction "2_2") (pintype "passive"))
    )
    (net (code "351") (name "Net-(Matrix5-Pad12)") (class "Default")
      (node (ref "Matrix5") (pin "12") (pinfunction "12_12") (pintype "passive"))
      (node (ref "R145") (pin "2") (pinfunction "2_2") (pintype "passive"))
    )
    (net (code "352") (name "Net-(Matrix6-17)") (class "Default")
      (node (ref "Matrix6") (pin "13") (pinfunction "17_13") (pintype "passive"))
      (node (ref "R120") (pin "1") (pinfunction "1_1") (pintype "passive"))
    )
    (net (code "353") (name "Net-(Matrix6-18)") (class "Default")
      (node (ref "Matrix6") (pin "14") (pinfunction "18_14") (pintype "passive"))
      (node (ref "R119") (pin "1") (pinfunction "1_1") (pintype "passive"))
    )
    (net (code "354") (name "Net-(Matrix6-19)") (class "Default")
      (node (ref "Matrix6") (pin "15") (pinfunction "19_15") (pintype "passive"))
      (node (ref "R118") (pin "1") (pinfunction "1_1") (pintype "passive"))
    )
    (net (code "355") (name "Net-(Matrix6-20)") (class "Default")
      (node (ref "Matrix6") (pin "16") (pinfunction "20_16") (pintype "passive"))
      (node (ref "R117") (pin "1") (pinfunction "1_1") (pintype "passive"))
    )
    (net (code "356") (name "Net-(Matrix6-21)") (class "Default")
      (node (ref "Matrix6") (pin "17") (pinfunction "21_17") (pintype "passive"))
      (node (ref "R116") (pin "1") (pinfunction "1_1") (pintype "passive"))
    )
    (net (code "357") (name "Net-(Matrix6-22)") (class "Default")
      (node (ref "Matrix6") (pin "18") (pinfunction "22_18") (pintype "passive"))
      (node (ref "R115") (pin "1") (pinfunction "1_1") (pintype "passive"))
    )
    (net (code "358") (name "Net-(Matrix6-23)") (class "Default")
      (node (ref "Matrix6") (pin "19") (pinfunction "23_19") (pintype "passive"))
      (node (ref "R114") (pin "1") (pinfunction "1_1") (pintype "passive"))
    )
    (net (code "359") (name "Net-(Matrix6-24)") (class "Default")
      (node (ref "Matrix6") (pin "20") (pinfunction "24_20") (pintype "passive"))
      (node (ref "R113") (pin "1") (pinfunction "1_1") (pintype "passive"))
    )
    (net (code "360") (name "Net-(Matrix6-Pad5)") (class "Default")
      (node (ref "Matrix6") (pin "5") (pinfunction "5_5") (pintype "passive"))
      (node (ref "R146") (pin "2") (pinfunction "2_2") (pintype "passive"))
    )
    (net (code "361") (name "Net-(Matrix6-Pad6)") (class "Default")
      (node (ref "Matrix6") (pin "6") (pinfunction "6_6") (pintype "passive"))
      (node (ref "R147") (pin "2") (pinfunction "2_2") (pintype "passive"))
    )
    (net (code "362") (name "Net-(Matrix6-Pad7)") (class "Default")
      (node (ref "Matrix6") (pin "7") (pinfunction "7_7") (pintype "passive"))
      (node (ref "R148") (pin "2") (pinfunction "2_2") (pintype "passive"))
    )
    (net (code "363") (name "Net-(Matrix6-Pad8)") (class "Default")
      (node (ref "Matrix6") (pin "8") (pinfunction "8_8") (pintype "passive"))
      (node (ref "R149") (pin "2") (pinfunction "2_2") (pintype "passive"))
    )
    (net (code "364") (name "Net-(Matrix6-Pad9)") (class "Default")
      (node (ref "Matrix6") (pin "9") (pinfunction "9_9") (pintype "passive"))
      (node (ref "R150") (pin "2") (pinfunction "2_2") (pintype "passive"))
    )
    (net (code "365") (name "Net-(Matrix6-Pad10)") (class "Default")
      (node (ref "Matrix6") (pin "10") (pinfunction "10_10") (pintype "passive"))
      (node (ref "R151") (pin "2") (pinfunction "2_2") (pintype "passive"))
    )
    (net (code "366") (name "Net-(Matrix6-Pad11)") (class "Default")
      (node (ref "Matrix6") (pin "11") (pinfunction "11_11") (pintype "passive"))
      (node (ref "R152") (pin "2") (pinfunction "2_2") (pintype "passive"))
    )
    (net (code "367") (name "Net-(Matrix6-Pad12)") (class "Default")
      (node (ref "Matrix6") (pin "12") (pinfunction "12_12") (pintype "passive"))
      (node (ref "R153") (pin "2") (pinfunction "2_2") (pintype "passive"))
    )
    (net (code "368") (name "Net-(Matrix7-17)") (class "Default")
      (node (ref "Matrix7") (pin "13") (pinfunction "17_13") (pintype "passive"))
      (node (ref "R96") (pin "1") (pinfunction "1_1") (pintype "passive"))
    )
    (net (code "369") (name "Net-(Matrix7-18)") (class "Default")
      (node (ref "Matrix7") (pin "14") (pinfunction "18_14") (pintype "passive"))
      (node (ref "R95") (pin "1") (pinfunction "1_1") (pintype "passive"))
    )
    (net (code "370") (name "Net-(Matrix7-19)") (class "Default")
      (node (ref "Matrix7") (pin "15") (pinfunction "19_15") (pintype "passive"))
      (node (ref "R94") (pin "1") (pinfunction "1_1") (pintype "passive"))
    )
    (net (code "371") (name "Net-(Matrix7-20)") (class "Default")
      (node (ref "Matrix7") (pin "16") (pinfunction "20_16") (pintype "passive"))
      (node (ref "R93") (pin "1") (pinfunction "1_1") (pintype "passive"))
    )
    (net (code "372") (name "Net-(Matrix7-21)") (class "Default")
      (node (ref "Matrix7") (pin "17") (pinfunction "21_17") (pintype "passive"))
      (node (ref "R92") (pin "1") (pinfunction "1_1") (pintype "passive"))
    )
    (net (code "373") (name "Net-(Matrix7-22)") (class "Default")
      (node (ref "Matrix7") (pin "18") (pinfunction "22_18") (pintype "passive"))
      (node (ref "R91") (pin "1") (pinfunction "1_1") (pintype "passive"))
    )
    (net (code "374") (name "Net-(Matrix7-23)") (class "Default")
      (node (ref "Matrix7") (pin "19") (pinfunction "23_19") (pintype "passive"))
      (node (ref "R90") (pin "1") (pinfunction "1_1") (pintype "passive"))
    )
    (net (code "375") (name "Net-(Matrix7-24)") (class "Default")
      (node (ref "Matrix7") (pin "20") (pinfunction "24_20") (pintype "passive"))
      (node (ref "R89") (pin "1") (pinfunction "1_1") (pintype "passive"))
    )
    (net (code "376") (name "Net-(Matrix7-Pad5)") (class "Default")
      (node (ref "Matrix7") (pin "5") (pinfunction "5_5") (pintype "passive"))
      (node (ref "R122") (pin "2") (pinfunction "2_2") (pintype "passive"))
    )
    (net (code "377") (name "Net-(Matrix7-Pad6)") (class "Default")
      (node (ref "Matrix7") (pin "6") (pinfunction "6_6") (pintype "passive"))
      (node (ref "R123") (pin "2") (pinfunction "2_2") (pintype "passive"))
    )
    (net (code "378") (name "Net-(Matrix7-Pad7)") (class "Default")
      (node (ref "Matrix7") (pin "7") (pinfunction "7_7") (pintype "passive"))
      (node (ref "R124") (pin "2") (pinfunction "2_2") (pintype "passive"))
    )
    (net (code "379") (name "Net-(Matrix7-Pad8)") (class "Default")
      (node (ref "Matrix7") (pin "8") (pinfunction "8_8") (pintype "passive"))
      (node (ref "R125") (pin "2") (pinfunction "2_2") (pintype "passive"))
    )
    (net (code "380") (name "Net-(Matrix7-Pad9)") (class "Default")
      (node (ref "Matrix7") (pin "9") (pinfunction "9_9") (pintype "passive"))
      (node (ref "R126") (pin "2") (pinfunction "2_2") (pintype "passive"))
    )
    (net (code "381") (name "Net-(Matrix7-Pad10)") (class "Default")
      (node (ref "Matrix7") (pin "10") (pinfunction "10_10") (pintype "passive"))
      (node (ref "R127") (pin "2") (pinfunction "2_2") (pintype "passive"))
    )
    (net (code "382") (name "Net-(Matrix7-Pad11)") (class "Default")
      (node (ref "Matrix7") (pin "11") (pinfunction "11_11") (pintype "passive"))
      (node (ref "R128") (pin "2") (pinfunction "2_2") (pintype "passive"))
    )
    (net (code "383") (name "Net-(Matrix7-Pad12)") (class "Default")
      (node (ref "Matrix7") (pin "12") (pinfunction "12_12") (pintype "passive"))
      (node (ref "R129") (pin "2") (pinfunction "2_2") (pintype "passive"))
    )
    (net (code "384") (name "Net-(Matrix8-17)") (class "Default")
      (node (ref "Matrix8") (pin "13") (pinfunction "17_13") (pintype "passive"))
      (node (ref "R104") (pin "1") (pinfunction "1_1") (pintype "passive"))
    )
    (net (code "385") (name "Net-(Matrix8-18)") (class "Default")
      (node (ref "Matrix8") (pin "14") (pinfunction "18_14") (pintype "passive"))
      (node (ref "R103") (pin "1") (pinfunction "1_1") (pintype "passive"))
    )
    (net (code "386") (name "Net-(Matrix8-19)") (class "Default")
      (node (ref "Matrix8") (pin "15") (pinfunction "19_15") (pintype "passive"))
      (node (ref "R102") (pin "1") (pinfunction "1_1") (pintype "passive"))
    )
    (net (code "387") (name "Net-(Matrix8-20)") (class "Default")
      (node (ref "Matrix8") (pin "16") (pinfunction "20_16") (pintype "passive"))
      (node (ref "R101") (pin "1") (pinfunction "1_1") (pintype "passive"))
    )
    (net (code "388") (name "Net-(Matrix8-21)") (class "Default")
      (node (ref "Matrix8") (pin "17") (pinfunction "21_17") (pintype "passive"))
      (node (ref "R100") (pin "1") (pinfunction "1_1") (pintype "passive"))
    )
    (net (code "389") (name "Net-(Matrix8-22)") (class "Default")
      (node (ref "Matrix8") (pin "18") (pinfunction "22_18") (pintype "passive"))
      (node (ref "R99") (pin "1") (pinfunction "1_1") (pintype "passive"))
    )
    (net (code "390") (name "Net-(Matrix8-23)") (class "Default")
      (node (ref "Matrix8") (pin "19") (pinfunction "23_19") (pintype "passive"))
      (node (ref "R98") (pin "1") (pinfunction "1_1") (pintype "passive"))
    )
    (net (code "391") (name "Net-(Matrix8-24)") (class "Default")
      (node (ref "Matrix8") (pin "20") (pinfunction "24_20") (pintype "passive"))
      (node (ref "R97") (pin "1") (pinfunction "1_1") (pintype "passive"))
    )
    (net (code "392") (name "Net-(Matrix8-Pad5)") (class "Default")
      (node (ref "Matrix8") (pin "5") (pinfunction "5_5") (pintype "passive"))
      (node (ref "R130") (pin "2") (pinfunction "2_2") (pintype "passive"))
    )
    (net (code "393") (name "Net-(Matrix8-Pad6)") (class "Default")
      (node (ref "Matrix8") (pin "6") (pinfunction "6_6") (pintype "passive"))
      (node (ref "R131") (pin "2") (pinfunction "2_2") (pintype "passive"))
    )
    (net (code "394") (name "Net-(Matrix8-Pad7)") (class "Default")
      (node (ref "Matrix8") (pin "7") (pinfunction "7_7") (pintype "passive"))
      (node (ref "R132") (pin "2") (pinfunction "2_2") (pintype "passive"))
    )
    (net (code "395") (name "Net-(Matrix8-Pad8)") (class "Default")
      (node (ref "Matrix8") (pin "8") (pinfunction "8_8") (pintype "passive"))
      (node (ref "R133") (pin "2") (pinfunction "2_2") (pintype "passive"))
    )
    (net (code "396") (name "Net-(Matrix8-Pad9)") (class "Default")
      (node (ref "Matrix8") (pin "9") (pinfunction "9_9") (pintype "passive"))
      (node (ref "R134") (pin "2") (pinfunction "2_2") (pintype "passive"))
    )
    (net (code "397") (name "Net-(Matrix8-Pad10)") (class "Default")
      (node (ref "Matrix8") (pin "10") (pinfunction "10_10") (pintype "passive"))
      (node (ref "R135") (pin "2") (pinfunction "2_2") (pintype "passive"))
    )
    (net (code "398") (name "Net-(Matrix8-Pad11)") (class "Default")
      (node (ref "Matrix8") (pin "11") (pinfunction "11_11") (pintype "passive"))
      (node (ref "R136") (pin "2") (pinfunction "2_2") (pintype "passive"))
    )
    (net (code "399") (name "Net-(Matrix8-Pad12)") (class "Default")
      (node (ref "Matrix8") (pin "12") (pinfunction "12_12") (pintype "passive"))
      (node (ref "R137") (pin "2") (pinfunction "2_2") (pintype "passive"))
    )
    (net (code "400") (name "Net-(SP1-+)") (class "Default")
      (node (ref "SP1") (pin "1") (pinfunction "+_1") (pintype "passive"))
      (node (ref "U33") (pin "1") (pinfunction "+OUT_L_1") (pintype "output"))
    )
    (net (code "401") (name "Net-(SP1--)") (class "Default")
      (node (ref "SP1") (pin "2") (pinfunction "-_2") (pintype "passive"))
      (node (ref "U33") (pin "3") (pinfunction "-OUT_L_3") (pintype "output"))
    )
    (net (code "402") (name "Net-(SP2-+)") (class "Default")
      (node (ref "SP2") (pin "1") (pinfunction "+_1") (pintype "passive"))
      (node (ref "U33") (pin "16") (pinfunction "+OUT_R_16") (pintype "output"))
    )
    (net (code "403") (name "Net-(SP2--)") (class "Default")
      (node (ref "SP2") (pin "2") (pinfunction "-_2") (pintype "passive"))
      (node (ref "U33") (pin "14") (pinfunction "-OUT_R_14") (pintype "output"))
    )
    (net (code "404") (name "Net-(U2-QH')") (class "Default")
      (node (ref "U2") (pin "9") (pinfunction "QH'_9") (pintype "output"))
      (node (ref "U4") (pin "14") (pinfunction "DATA_IN_14") (pintype "input"))
    )
    (net (code "405") (name "Net-(U3-IO0)") (class "Default")
      (node (ref "BT10") (pin "1") (pintype "passive"))
      (node (ref "R12") (pin "1") (pinfunction "1_1") (pintype "passive"))
      (node (ref "U3") (pin "27") (pinfunction "IO0_27") (pintype "bidirectional"))
    )
    (net (code "406") (name "Net-(U4-QH')") (class "Default")
      (node (ref "U4") (pin "9") (pinfunction "QH'_9") (pintype "output"))
      (node (ref "U5") (pin "14") (pinfunction "DATA_IN_14") (pintype "input"))
    )
    (net (code "407") (name "Net-(U5-QH')") (class "Default")
      (node (ref "U5") (pin "9") (pinfunction "QH'_9") (pintype "output"))
      (node (ref "U6") (pin "14") (pinfunction "DATA_IN_14") (pintype "input"))
    )
    (net (code "408") (name "Net-(U6-QH')") (class "Default")
      (node (ref "U6") (pin "9") (pinfunction "QH'_9") (pintype "output"))
      (node (ref "U7") (pin "14") (pinfunction "DATA_IN_14") (pintype "input"))
    )
    (net (code "409") (name "Net-(U7-QH')") (class "Default")
      (node (ref "U7") (pin "9") (pinfunction "QH'_9") (pintype "output"))
      (node (ref "U8") (pin "14") (pinfunction "DATA_IN_14") (pintype "input"))
    )
    (net (code "410") (name "Net-(U9-FB)") (class "Default")
      (node (ref "R158") (pin "2") (pinfunction "2_2") (pintype "passive"))
      (node (ref "R24") (pin "1") (pinfunction "1_1") (pintype "passive"))
      (node (ref "U9") (pin "5") (pinfunction "FB_5") (pintype "input"))
    )
    (net (code "411") (name "Net-(U10-CE)") (class "Default")
      (node (ref "C8") (pin "2") (pinfunction "2_2") (pintype "passive"))
      (node (ref "D3") (pin "A") (pinfunction "A_A") (pintype "passive"))
      (node (ref "D4") (pin "A") (pinfunction "A_A") (pintype "passive"))
      (node (ref "F1") (pin "1") (pinfunction "1_1") (pintype "passive"))
      (node (ref "R163") (pin "1") (pinfunction "1_1") (pintype "passive"))
      (node (ref "U10") (pin "4") (pinfunction "VCC_4") (pintype "power_in"))
      (node (ref "U10") (pin "8") (pinfunction "CE_8") (pintype "input"))
    )
    (net (code "412") (name "Net-(U10-PROG)") (class "Default")
      (node (ref "R17") (pin "1") (pinfunction "1_1") (pintype "passive"))
      (node (ref "U10") (pin "2") (pinfunction "PROG_2") (pintype "bidirectional"))
    )
    (net (code "413") (name "Net-(U10-TEMP)") (class "Default")
      (node (ref "R163") (pin "2") (pinfunction "2_2") (pintype "passive"))
      (node (ref "R164") (pin "1") (pinfunction "1_1") (pintype "passive"))
      (node (ref "U10") (pin "1") (pinfunction "TEMP_1") (pintype "input"))
    )
    (net (code "414") (name "Net-(U10-~{CHRG})") (class "Default")
      (node (ref "R15") (pin "2") (pinfunction "2_2") (pintype "passive"))
      (node (ref "U10") (pin "7") (pinfunction "~{CHRG}_7") (pintype "output"))
    )
    (net (code "415") (name "Net-(U10-~{STDBY})") (class "Default")
      (node (ref "R14") (pin "2") (pinfunction "2_2") (pintype "passive"))
      (node (ref "U10") (pin "6") (pinfunction "~{STDBY}_6") (pintype "output"))
    )
    (net (code "416") (name "Net-(U11-AD0)") (class "Default")
      (node (ref "R166") (pin "1") (pinfunction "1_1") (pintype "passive"))
      (node (ref "U11") (pin "9") (pinfunction "AD0_9") (pintype "input"))
    )
    (net (code "417") (name "Net-(U11-AUX_CL)") (class "Default")
      (node (ref "R20") (pin "2") (pinfunction "2_2") (pintype "passive"))
      (node (ref "U11") (pin "7") (pinfunction "AUX_CL_7") (pintype "output"))
    )
    (net (code "418") (name "Net-(U11-AUX_DA)") (class "Default")
      (node (ref "R21") (pin "2") (pinfunction "2_2") (pintype "passive"))
      (node (ref "U11") (pin "6") (pinfunction "AUX_DA_6") (pintype "bidirectional"))
    )
    (net (code "419") (name "Net-(U11-CPOUT)") (class "Default")
      (node (ref "C10") (pin "2") (pinfunction "2_2") (pintype "passive"))
      (node (ref "U11") (pin "20") (pinfunction "CPOUT_20") (pintype "passive"))
    )
    (net (code "420") (name "Net-(U11-REGOUT)") (class "Default")
      (node (ref "C12") (pin "2") (pinfunction "2_2") (pintype "passive"))
      (node (ref "U11") (pin "10") (pinfunction "REGOUT_10") (pintype "passive"))
    )
    (net (code "421") (name "Net-(U11-VLOGIC)") (class "Default")
      (node (ref "C27") (pin "2") (pinfunction "2_2") (pintype "passive"))
      (node (ref "U11") (pin "8") (pinfunction "VLOGIC_8") (pintype "power_in"))
    )
    (net (code "422") (name "Net-(U12-DATA_IN)") (class "Default")
      (node (ref "U12") (pin "14") (pinfunction "DATA_IN_14") (pintype "input"))
      (node (ref "U8") (pin "9") (pinfunction "QH'_9") (pintype "output"))
    )
    (net (code "423") (name "Net-(U12-QH')") (class "Default")
      (node (ref "U12") (pin "9") (pinfunction "QH'_9") (pintype "output"))
      (node (ref "U13") (pin "14") (pinfunction "DATA_IN_14") (pintype "input"))
    )
    (net (code "424") (name "Net-(U13-QH')") (class "Default")
      (node (ref "U13") (pin "9") (pinfunction "QH'_9") (pintype "output"))
      (node (ref "U14") (pin "14") (pinfunction "DATA_IN_14") (pintype "input"))
    )
    (net (code "425") (name "Net-(U14-QH')") (class "Default")
      (node (ref "U14") (pin "9") (pinfunction "QH'_9") (pintype "output"))
      (node (ref "U16") (pin "14") (pinfunction "DATA_IN_14") (pintype "input"))
    )
    (net (code "426") (name "Net-(U16-QH')") (class "Default")
      (node (ref "U16") (pin "9") (pinfunction "QH'_9") (pintype "output"))
      (node (ref "U17") (pin "14") (pinfunction "DATA_IN_14") (pintype "input"))
    )
    (net (code "427") (name "Net-(U17-QH')") (class "Default")
      (node (ref "U17") (pin "9") (pinfunction "QH'_9") (pintype "output"))
      (node (ref "U18") (pin "14") (pinfunction "DATA_IN_14") (pintype "input"))
    )
    (net (code "428") (name "Net-(U18-QH')") (class "Default")
      (node (ref "U18") (pin "9") (pinfunction "QH'_9") (pintype "output"))
      (node (ref "U19") (pin "14") (pinfunction "DATA_IN_14") (pintype "input"))
    )
    (net (code "429") (name "Net-(U19-QH')") (class "Default")
      (node (ref "U19") (pin "9") (pinfunction "QH'_9") (pintype "output"))
      (node (ref "U20") (pin "14") (pinfunction "DATA_IN_14") (pintype "input"))
    )
    (net (code "430") (name "Net-(U20-QH')") (class "Default")
      (node (ref "U20") (pin "9") (pinfunction "QH'_9") (pintype "output"))
      (node (ref "U21") (pin "14") (pinfunction "DATA_IN_14") (pintype "input"))
    )
    (net (code "431") (name "Net-(U21-QH')") (class "Default")
      (node (ref "U21") (pin "9") (pinfunction "QH'_9") (pintype "output"))
      (node (ref "U22") (pin "14") (pinfunction "DATA_IN_14") (pintype "input"))
    )
    (net (code "432") (name "Net-(U22-QH')") (class "Default")
      (node (ref "U22") (pin "9") (pinfunction "QH'_9") (pintype "output"))
      (node (ref "U23") (pin "14") (pinfunction "DATA_IN_14") (pintype "input"))
    )
    (net (code "433") (name "Net-(U23-QH')") (class "Default")
      (node (ref "U23") (pin "9") (pinfunction "QH'_9") (pintype "output"))
      (node (ref "U24") (pin "14") (pinfunction "DATA_IN_14") (pintype "input"))
    )
    (net (code "434") (name "Net-(U24-QH')") (class "Default")
      (node (ref "U24") (pin "9") (pinfunction "QH'_9") (pintype "output"))
      (node (ref "U26") (pin "14") (pinfunction "DATA_IN_14") (pintype "input"))
    )
    (net (code "435") (name "Net-(U25-CAPM)") (class "Default")
      (node (ref "C20") (pin "1") (pinfunction "1_1") (pintype "passive"))
      (node (ref "U25") (pin "4") (pinfunction "CAPM_4") (pintype "passive"))
    )
    (net (code "436") (name "Net-(U25-CAPP)") (class "Default")
      (node (ref "C20") (pin "2") (pinfunction "2_2") (pintype "passive"))
      (node (ref "U25") (pin "2") (pinfunction "CAPP_2") (pintype "passive"))
    )
    (net (code "437") (name "Net-(U25-LDOO)") (class "Default")
      (node (ref "C16") (pin "1") (pinfunction "1_1") (pintype "passive"))
      (node (ref "C17") (pin "1") (pinfunction "1_1") (pintype "passive"))
      (node (ref "U25") (pin "18") (pinfunction "LDOO_18") (pintype "power_in"))
    )
    (net (code "438") (name "Net-(U25-VNEG)") (class "Default")
      (node (ref "C18") (pin "2") (pinfunction "2_2") (pintype "passive"))
      (node (ref "C19") (pin "2") (pinfunction "2_2") (pintype "passive"))
      (node (ref "U25") (pin "5") (pinfunction "VNEG_5") (pintype "output"))
    )
    (net (code "439") (name "Net-(U26-QH')") (class "Default")
      (node (ref "U26") (pin "9") (pinfunction "QH'_9") (pintype "output"))
      (node (ref "U27") (pin "14") (pinfunction "DATA_IN_14") (pintype "input"))
    )
    (net (code "440") (name "Net-(U27-QH')") (class "Default")
      (node (ref "U27") (pin "9") (pinfunction "QH'_9") (pintype "output"))
      (node (ref "U28") (pin "14") (pinfunction "DATA_IN_14") (pintype "input"))
    )
    (net (code "441") (name "Net-(U28-QH')") (class "Default")
      (node (ref "U28") (pin "9") (pinfunction "QH'_9") (pintype "output"))
      (node (ref "U29") (pin "14") (pinfunction "DATA_IN_14") (pintype "input"))
    )
    (net (code "442") (name "Net-(U29-QH')") (class "Default")
      (node (ref "U29") (pin "9") (pinfunction "QH'_9") (pintype "output"))
      (node (ref "U30") (pin "14") (pinfunction "DATA_IN_14") (pintype "input"))
    )
    (net (code "443") (name "Net-(U30-QH')") (class "Default")
      (node (ref "U30") (pin "9") (pinfunction "QH'_9") (pintype "output"))
      (node (ref "U31") (pin "14") (pinfunction "DATA_IN_14") (pintype "input"))
    )
    (net (code "444") (name "Net-(U32-1A)") (class "Default")
      (node (ref "R154") (pin "2") (pinfunction "2_2") (pintype "passive"))
      (node (ref "U32") (pin "2") (pinfunction "1A_2") (pintype "input"))
    )
    (net (code "445") (name "Net-(U32-2A)") (class "Default")
      (node (ref "R156") (pin "2") (pinfunction "2_2") (pintype "passive"))
      (node (ref "U32") (pin "5") (pinfunction "2A_5") (pintype "input"))
    )
    (net (code "446") (name "Net-(U32-3A)") (class "Default")
      (node (ref "R157") (pin "1") (pinfunction "1_1") (pintype "passive"))
      (node (ref "U32") (pin "9") (pinfunction "3A_9") (pintype "input"))
    )
    (net (code "447") (name "Net-(U32-4A)") (class "Default")
      (node (ref "R155") (pin "1") (pinfunction "1_1") (pintype "passive"))
      (node (ref "U32") (pin "12") (pinfunction "4A_12") (pintype "input"))
    )
    (net (code "448") (name "Net-(U33-INL)") (class "Default")
      (node (ref "R165") (pin "2") (pinfunction "2_2") (pintype "passive"))
      (node (ref "U33") (pin "7") (pinfunction "INL_7") (pintype "input"))
    )
    (net (code "449") (name "Net-(U33-INR)") (class "Default")
      (node (ref "R167") (pin "2") (pinfunction "2_2") (pintype "passive"))
      (node (ref "U33") (pin "10") (pinfunction "INR_10") (pintype "input"))
    )
    (net (code "450") (name "Net-(U33-PVDD@1)") (class "Default")
      (node (ref "C21") (pin "2") (pinfunction "2_2") (pintype "passive"))
      (node (ref "U33") (pin "13") (pinfunction "PVDD@2_13") (pintype "power_in"))
      (node (ref "U33") (pin "4") (pinfunction "PVDD@1_4") (pintype "power_in"))
    )
    (net (code "451") (name "Net-(U33-VREF)") (class "Default")
      (node (ref "C22") (pin "2") (pinfunction "2_2") (pintype "passive"))
      (node (ref "U33") (pin "8") (pinfunction "VREF_8") (pintype "input"))
    )
    (net (code "452") (name "Net-(U34-VCC)") (class "Default")
      (node (ref "D7") (pin "K") (pinfunction "K_K") (pintype "passive"))
      (node (ref "U34") (pin "16") (pinfunction "VCC_16") (pintype "power_in"))
    )
    (net (code "453") (name "Net-(U34-XI)") (class "Default")
      (node (ref "C24") (pin "2") (pinfunction "2_2") (pintype "passive"))
      (node (ref "U34") (pin "7") (pinfunction "XI_7") (pintype "input"))
      (node (ref "X1") (pin "1") (pintype "passive"))
    )
    (net (code "454") (name "Net-(U34-XO)") (class "Default")
      (node (ref "C25") (pin "2") (pinfunction "2_2") (pintype "passive"))
      (node (ref "U34") (pin "8") (pinfunction "XO_8") (pintype "output"))
      (node (ref "X1") (pin "2") (pintype "passive"))
    )
    (net (code "455") (name "unconnected-(CN1-CC1-PadA5)") (class "Default")
      (node (ref "CN1") (pin "A5") (pinfunction "CC1_A5") (pintype "passive+no_connect"))
    )
    (net (code "456") (name "unconnected-(CN1-CC2-PadB5)") (class "Default")
      (node (ref "CN1") (pin "B5") (pinfunction "CC2_B5") (pintype "passive+no_connect"))
    )
    (net (code "457") (name "unconnected-(CN1-SBU1-PadA8)") (class "Default")
      (node (ref "CN1") (pin "A8") (pinfunction "SBU1_A8") (pintype "passive+no_connect"))
    )
    (net (code "458") (name "unconnected-(CN1-SBU2-PadB8)") (class "Default")
      (node (ref "CN1") (pin "B8") (pinfunction "SBU2_B8") (pintype "passive+no_connect"))
    )
    (net (code "459") (name "unconnected-(J3-Left_in-Pad2)") (class "Default")
      (node (ref "J3") (pin "2") (pinfunction "Left_in_2") (pintype "passive+no_connect"))
    )
    (net (code "460") (name "unconnected-(J3-Right_in-Pad5)") (class "Default")
      (node (ref "J3") (pin "5") (pinfunction "Right_in_5") (pintype "passive+no_connect"))
    )
    (net (code "461") (name "unconnected-(SD1-CD-PadP9)") (class "Default")
      (node (ref "SD1") (pin "P9") (pinfunction "CD_P9") (pintype "passive+no_connect"))
    )
    (net (code "462") (name "unconnected-(SD1-DAT1-PadP8)") (class "Default")
      (node (ref "SD1") (pin "P8") (pinfunction "DAT1_P8") (pintype "passive+no_connect"))
    )
    (net (code "463") (name "unconnected-(SD1-DAT2-PadP1)") (class "Default")
      (node (ref "SD1") (pin "P1") (pinfunction "DAT2_P1") (pintype "passive+no_connect"))
    )
    (net (code "464") (name "unconnected-(SD1-P10-PadP10-1)") (class "Default")
      (node (ref "SD1") (pin "P10-1") (pinfunction "P10_P10-1") (pintype "passive+no_connect"))
    )
    (net (code "465") (name "unconnected-(SD1-P10-PadP10-2)") (class "Default")
      (node (ref "SD1") (pin "P10-2") (pinfunction "P10_P10-2") (pintype "passive+no_connect"))
    )
    (net (code "466") (name "unconnected-(SD1-P10-PadP10-3)") (class "Default")
      (node (ref "SD1") (pin "P10-3") (pinfunction "P10_P10-3") (pintype "passive+no_connect"))
    )
    (net (code "467") (name "unconnected-(SD1-P10-PadP10-4)") (class "Default")
      (node (ref "SD1") (pin "P10-4") (pinfunction "P10_P10-4") (pintype "passive+no_connect"))
    )
    (net (code "468") (name "unconnected-(SW1-Pad3)") (class "Default")
      (node (ref "SW1") (pin "3") (pinfunction "3_3") (pintype "passive+no_connect"))
    )
    (net (code "469") (name "unconnected-(U1-IO19-Pad13)") (class "Default")
      (node (ref "U1") (pin "13") (pinfunction "IO19_13") (pintype "bidirectional+no_connect"))
    )
    (net (code "470") (name "unconnected-(U1-IO20-Pad14)") (class "Default")
      (node (ref "U1") (pin "14") (pinfunction "IO20_14") (pintype "bidirectional+no_connect"))
    )
    (net (code "471") (name "unconnected-(U1-IO35-Pad28)") (class "Default")
      (node (ref "U1") (pin "28") (pinfunction "IO35_28") (pintype "bidirectional+no_connect"))
    )
    (net (code "472") (name "unconnected-(U1-IO36-Pad29)") (class "Default")
      (node (ref "U1") (pin "29") (pinfunction "IO36_29") (pintype "bidirectional+no_connect"))
    )
    (net (code "473") (name "unconnected-(U1-IO37-Pad30)") (class "Default")
      (node (ref "U1") (pin "30") (pinfunction "IO37_30") (pintype "bidirectional+no_connect"))
    )
    (net (code "474") (name "unconnected-(U1-IO38-Pad31)") (class "Default")
      (node (ref "U1") (pin "31") (pinfunction "IO38_31") (pintype "bidirectional+no_connect"))
    )
    (net (code "475") (name "unconnected-(U1-IO39-Pad32)") (class "Default")
      (node (ref "U1") (pin "32") (pinfunction "IO39_32") (pintype "bidirectional+no_connect"))
    )
    (net (code "476") (name "unconnected-(U1-IO40-Pad33)") (class "Default")
      (node (ref "U1") (pin "33") (pinfunction "IO40_33") (pintype "bidirectional+no_connect"))
    )
    (net (code "477") (name "unconnected-(U1-IO41-Pad34)") (class "Default")
      (node (ref "U1") (pin "34") (pinfunction "IO41_34") (pintype "bidirectional+no_connect"))
    )
    (net (code "478") (name "unconnected-(U1-IO42-Pad35)") (class "Default")
      (node (ref "U1") (pin "35") (pinfunction "IO42_35") (pintype "bidirectional+no_connect"))
    )
    (net (code "479") (name "unconnected-(U1-IO45-Pad26)") (class "Default")
      (node (ref "U1") (pin "26") (pinfunction "IO45_26") (pintype "bidirectional+no_connect"))
    )
    (net (code "480") (name "unconnected-(U1-IO46-Pad16)") (class "Default")
      (node (ref "U1") (pin "16") (pinfunction "IO46_16") (pintype "bidirectional+no_connect"))
    )
    (net (code "481") (name "unconnected-(U3-IO19-Pad13)") (class "Default")
      (node (ref "U3") (pin "13") (pinfunction "IO19_13") (pintype "bidirectional+no_connect"))
    )
    (net (code "482") (name "unconnected-(U3-IO20-Pad14)") (class "Default")
      (node (ref "U3") (pin "14") (pinfunction "IO20_14") (pintype "bidirectional+no_connect"))
    )
    (net (code "483") (name "unconnected-(U3-IO35-Pad28)") (class "Default")
      (node (ref "U3") (pin "28") (pinfunction "IO35_28") (pintype "bidirectional+no_connect"))
    )
    (net (code "484") (name "unconnected-(U3-IO36-Pad29)") (class "Default")
      (node (ref "U3") (pin "29") (pinfunction "IO36_29") (pintype "bidirectional+no_connect"))
    )
    (net (code "485") (name "unconnected-(U3-IO37-Pad30)") (class "Default")
      (node (ref "U3") (pin "30") (pinfunction "IO37_30") (pintype "bidirectional+no_connect"))
    )
    (net (code "486") (name "unconnected-(U3-IO38-Pad31)") (class "Default")
      (node (ref "U3") (pin "31") (pinfunction "IO38_31") (pintype "bidirectional+no_connect"))
    )
    (net (code "487") (name "unconnected-(U3-IO39-Pad32)") (class "Default")
      (node (ref "U3") (pin "32") (pinfunction "IO39_32") (pintype "bidirectional+no_connect"))
    )
    (net (code "488") (name "unconnected-(U3-IO40-Pad33)") (class "Default")
      (node (ref "U3") (pin "33") (pinfunction "IO40_33") (pintype "bidirectional+no_connect"))
    )
    (net (code "489") (name "unconnected-(U3-IO41-Pad34)") (class "Default")
      (node (ref "U3") (pin "34") (pinfunction "IO41_34") (pintype "bidirectional+no_connect"))
    )
    (net (code "490") (name "unconnected-(U3-IO42-Pad35)") (class "Default")
      (node (ref "U3") (pin "35") (pinfunction "IO42_35") (pintype "bidirectional+no_connect"))
    )
    (net (code "491") (name "unconnected-(U3-IO45-Pad26)") (class "Default")
      (node (ref "U3") (pin "26") (pinfunction "IO45_26") (pintype "bidirectional+no_connect"))
    )
    (net (code "492") (name "unconnected-(U3-IO46-Pad16)") (class "Default")
      (node (ref "U3") (pin "16") (pinfunction "IO46_16") (pintype "bidirectional+no_connect"))
    )
    (net (code "493") (name "unconnected-(U9-SW-Pad6)") (class "Default")
      (node (ref "U9") (pin "6") (pinfunction "SW_6") (pintype "output+no_connect"))
    )
    (net (code "494") (name "unconnected-(U10-EP-Pad9)") (class "Default")
      (node (ref "U10") (pin "9") (pinfunction "EP_9") (pintype "passive+no_connect"))
    )
    (net (code "495") (name "unconnected-(U11-INT-Pad12)") (class "Default")
      (node (ref "U11") (pin "12") (pinfunction "INT_12") (pintype "output+no_connect"))
    )
    (net (code "496") (name "unconnected-(U11-NC-Pad2)") (class "Default")
      (node (ref "U11") (pin "2") (pinfunction "NC_2") (pintype "passive+no_connect"))
    )
    (net (code "497") (name "unconnected-(U11-NC-Pad3)") (class "Default")
      (node (ref "U11") (pin "3") (pinfunction "NC_3") (pintype "passive+no_connect"))
    )
    (net (code "498") (name "unconnected-(U11-NC-Pad4)") (class "Default")
      (node (ref "U11") (pin "4") (pinfunction "NC_4") (pintype "passive+no_connect"))
    )
    (net (code "499") (name "unconnected-(U11-NC-Pad5)") (class "Default")
      (node (ref "U11") (pin "5") (pinfunction "NC_5") (pintype "passive+no_connect"))
    )
    (net (code "500") (name "unconnected-(U11-NC-Pad14)") (class "Default")
      (node (ref "U11") (pin "14") (pinfunction "NC_14") (pintype "passive+no_connect"))
    )
    (net (code "501") (name "unconnected-(U11-NC-Pad15)") (class "Default")
      (node (ref "U11") (pin "15") (pinfunction "NC_15") (pintype "passive+no_connect"))
    )
    (net (code "502") (name "unconnected-(U11-NC-Pad16)") (class "Default")
      (node (ref "U11") (pin "16") (pinfunction "NC_16") (pintype "passive+no_connect"))
    )
    (net (code "503") (name "unconnected-(U11-NC-Pad17)") (class "Default")
      (node (ref "U11") (pin "17") (pinfunction "NC_17") (pintype "passive+no_connect"))
    )
    (net (code "504") (name "unconnected-(U11-RESV-Pad19)") (class "Default")
      (node (ref "U11") (pin "19") (pinfunction "RESV_19") (pintype "passive+no_connect"))
    )
    (net (code "505") (name "unconnected-(U11-RESV-Pad21)") (class "Default")
      (node (ref "U11") (pin "21") (pinfunction "RESV_21") (pintype "passive+no_connect"))
    )
    (net (code "506") (name "unconnected-(U11-RESV-Pad22)") (class "Default")
      (node (ref "U11") (pin "22") (pinfunction "RESV_22") (pintype "passive+no_connect"))
    )
    (net (code "507") (name "unconnected-(U31-QH'-Pad9)") (class "Default")
      (node (ref "U31") (pin "9") (pinfunction "QH'_9") (pintype "output+no_connect"))
    )
    (net (code "508") (name "unconnected-(U34-RS232-Pad15)") (class "Default")
      (node (ref "U34") (pin "15") (pinfunction "RS232_15") (pintype "input+no_connect"))
    )
    (net (code "509") (name "unconnected-(U34-~{CTS}-Pad9)") (class "Default")
      (node (ref "U34") (pin "9") (pinfunction "~{CTS}_9") (pintype "input+no_connect"))
    )
    (net (code "510") (name "unconnected-(U34-~{DCD}-Pad12)") (class "Default")
      (node (ref "U34") (pin "12") (pinfunction "~{DCD}_12") (pintype "input+no_connect"))
    )
    (net (code "511") (name "unconnected-(U34-~{DSR}-Pad10)") (class "Default")
      (node (ref "U34") (pin "10") (pinfunction "~{DSR}_10") (pintype "input+no_connect"))
    )
    (net (code "512") (name "unconnected-(U34-~{DTR}-Pad13)") (class "Default")
      (node (ref "U34") (pin "13") (pinfunction "~{DTR}_13") (pintype "output+no_connect"))
    )
    (net (code "513") (name "unconnected-(U34-~{RI}-Pad11)") (class "Default")
      (node (ref "U34") (pin "11") (pinfunction "~{RI}_11") (pintype "input+no_connect"))
    )
    (net (code "514") (name "unconnected-(U34-~{RTS}-Pad14)") (class "Default")
      (node (ref "U34") (pin "14") (pinfunction "~{RTS}_14") (pintype "output+no_connect"))
    )
  )
)
